# Arduino.net
KiCad netlist of a schematic drawn in EasyEDA
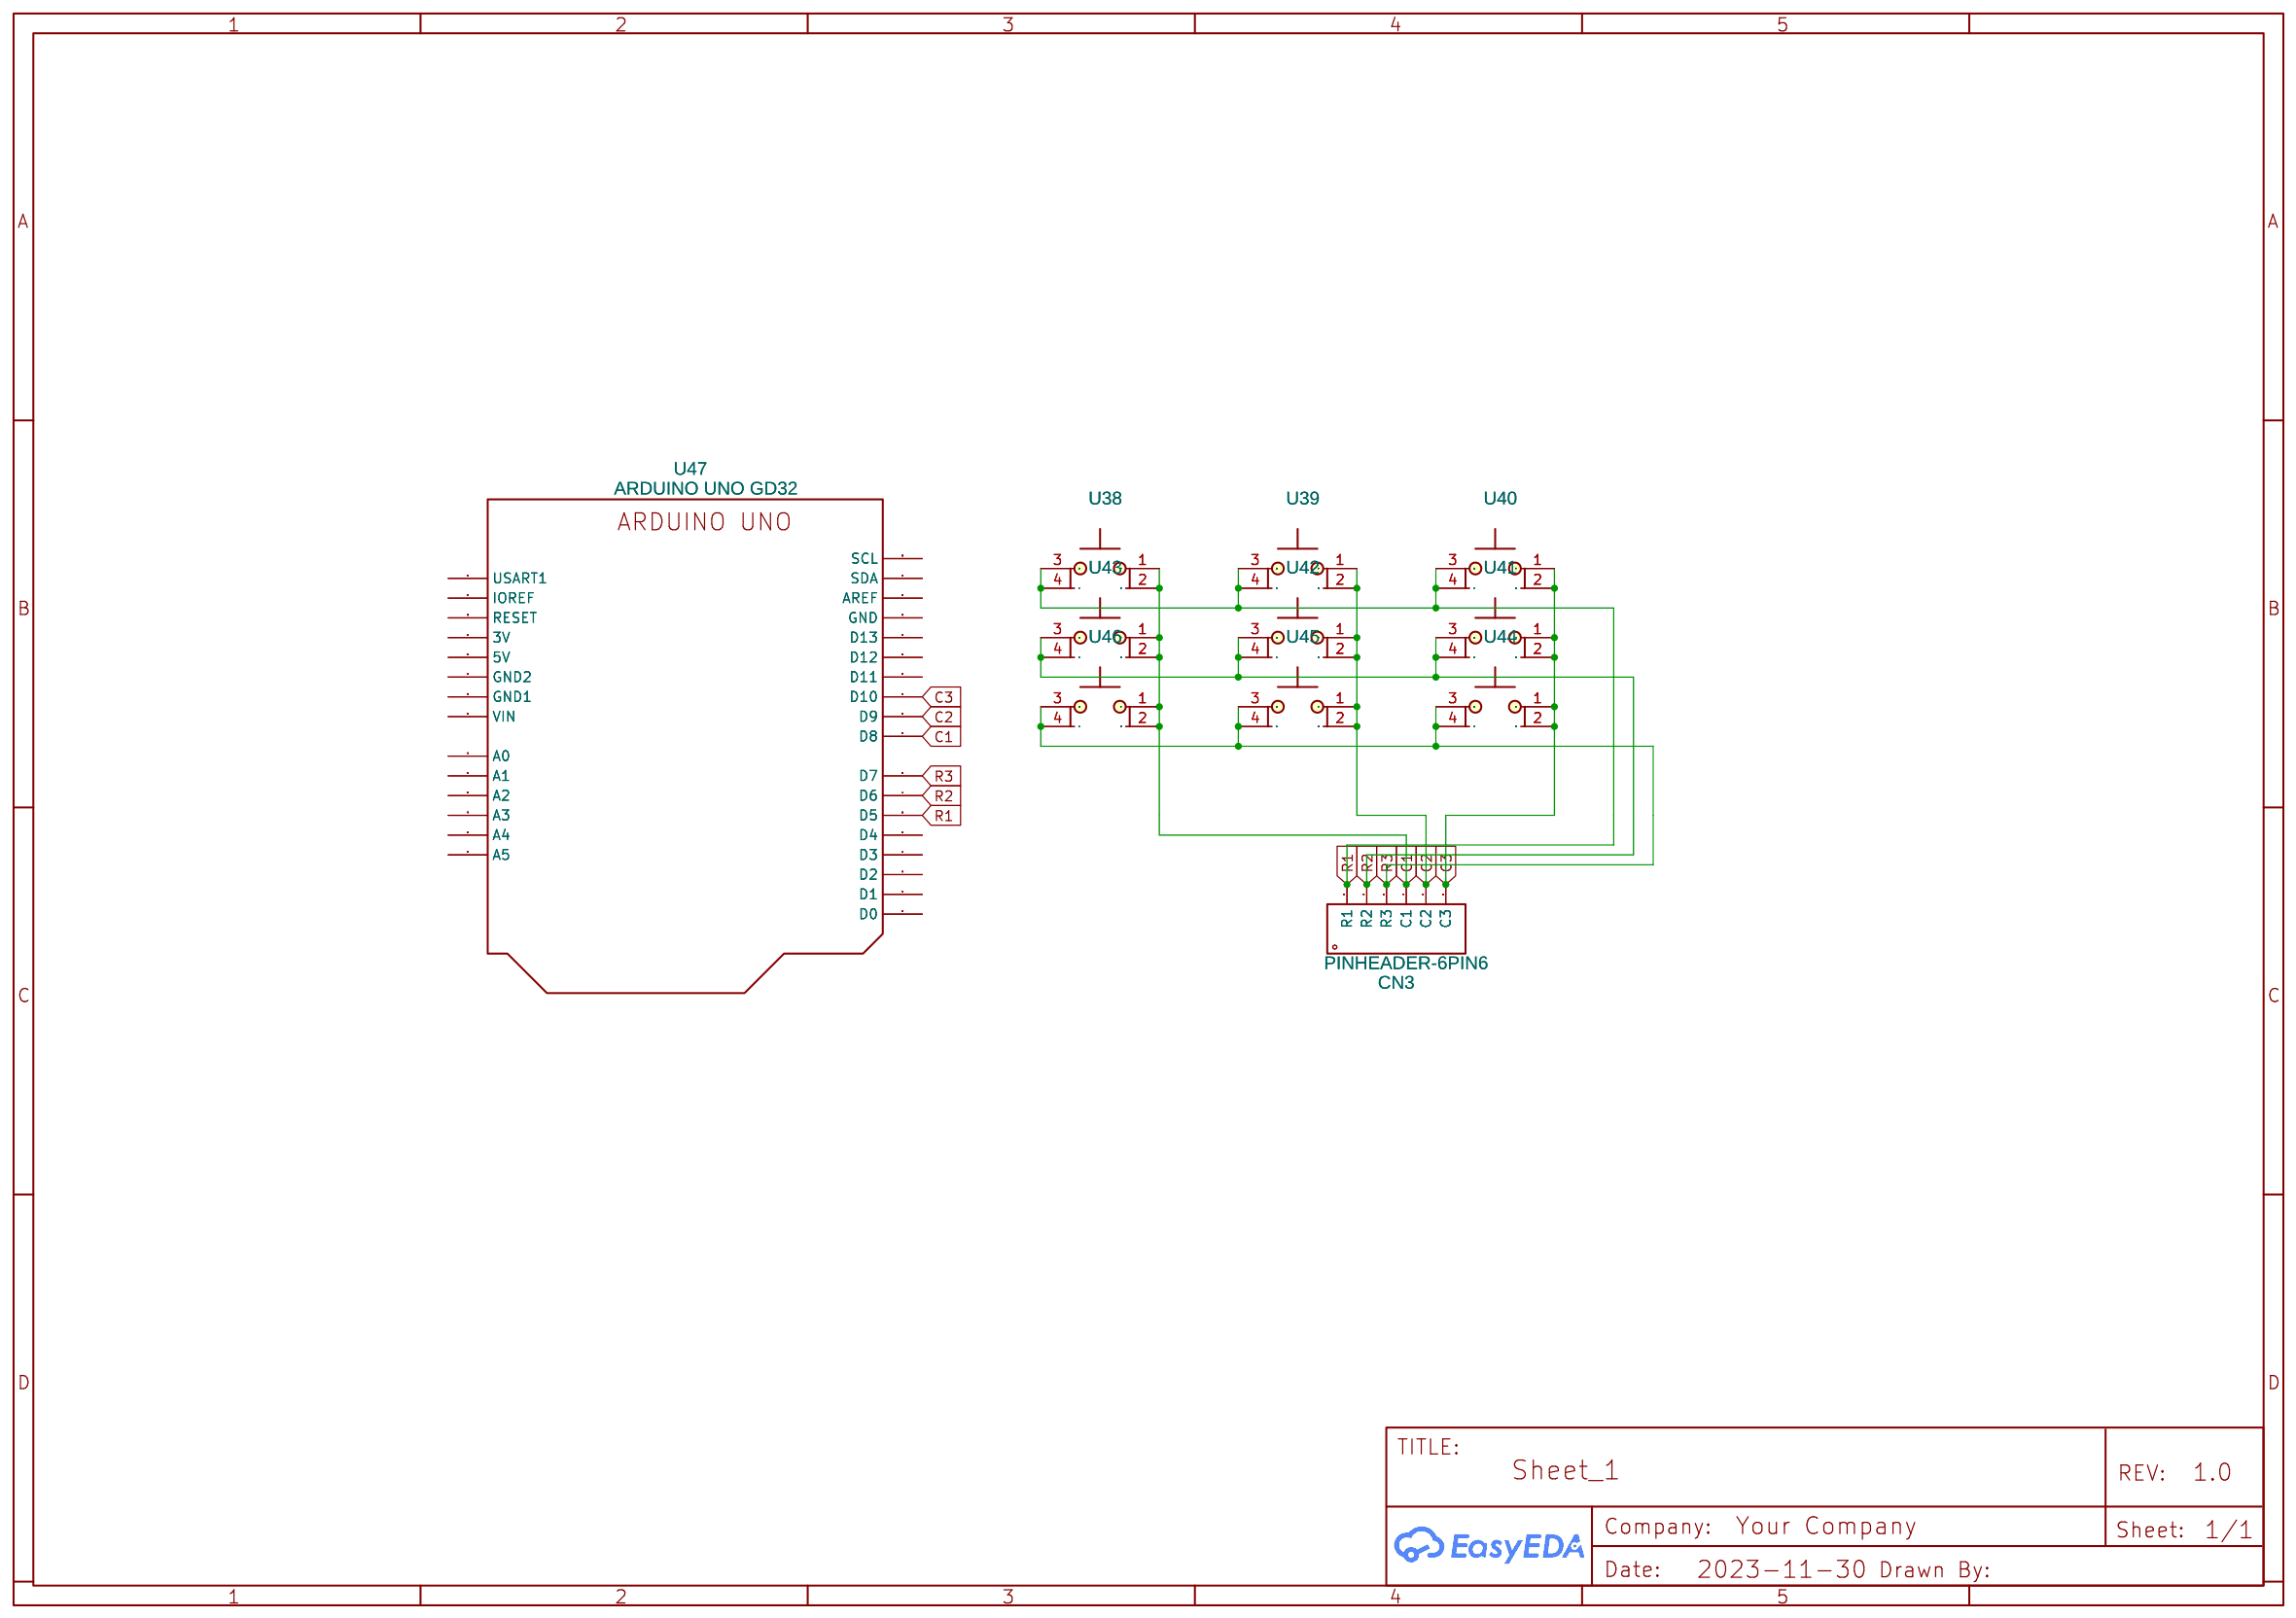
[diagram p0: Arduino_Keypad 3X3]
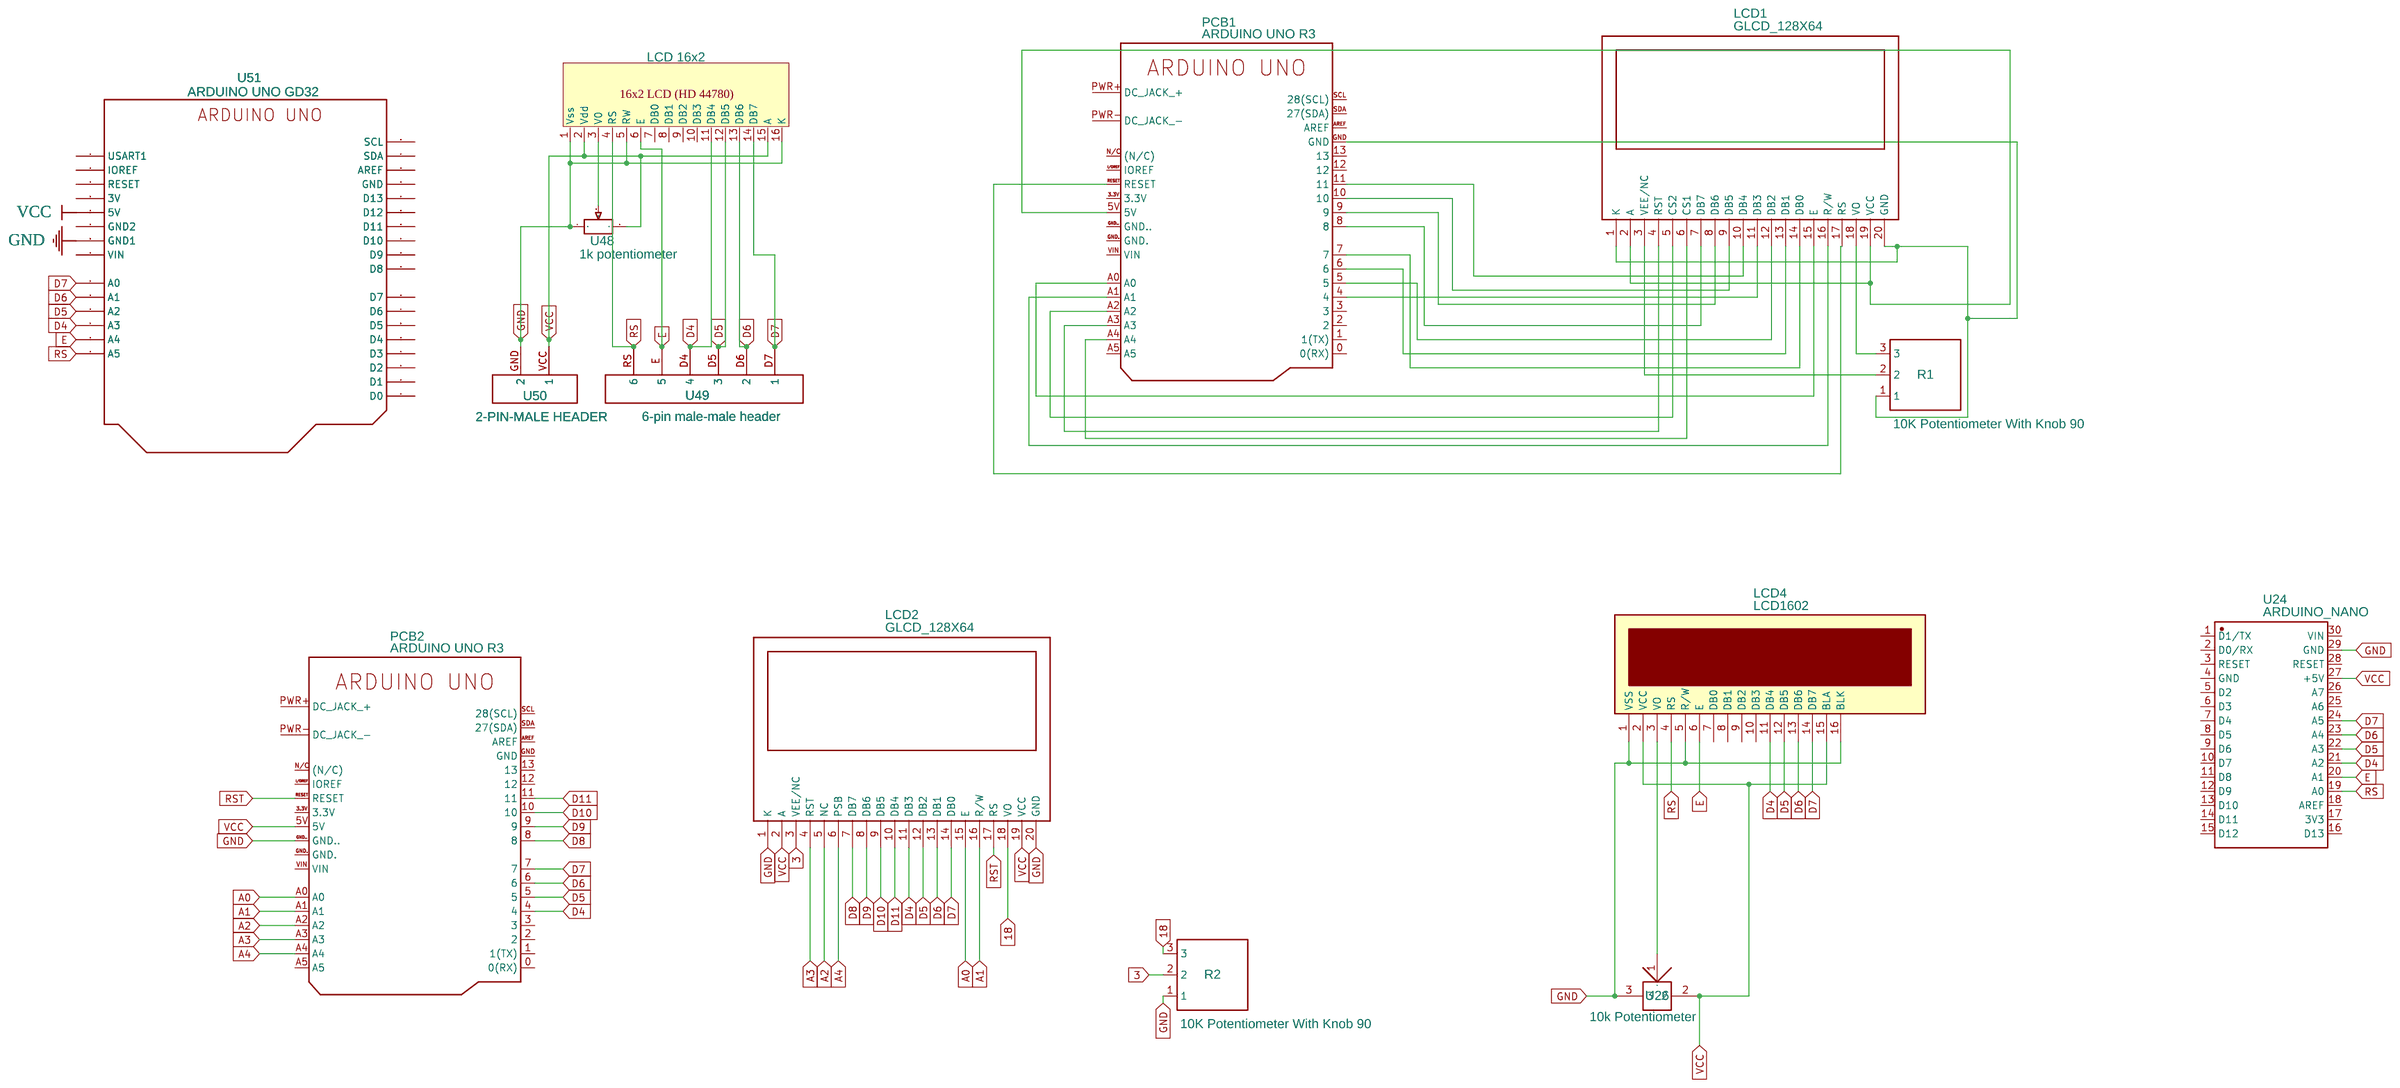
[diagram p1: Arduino_LCD 16x2]
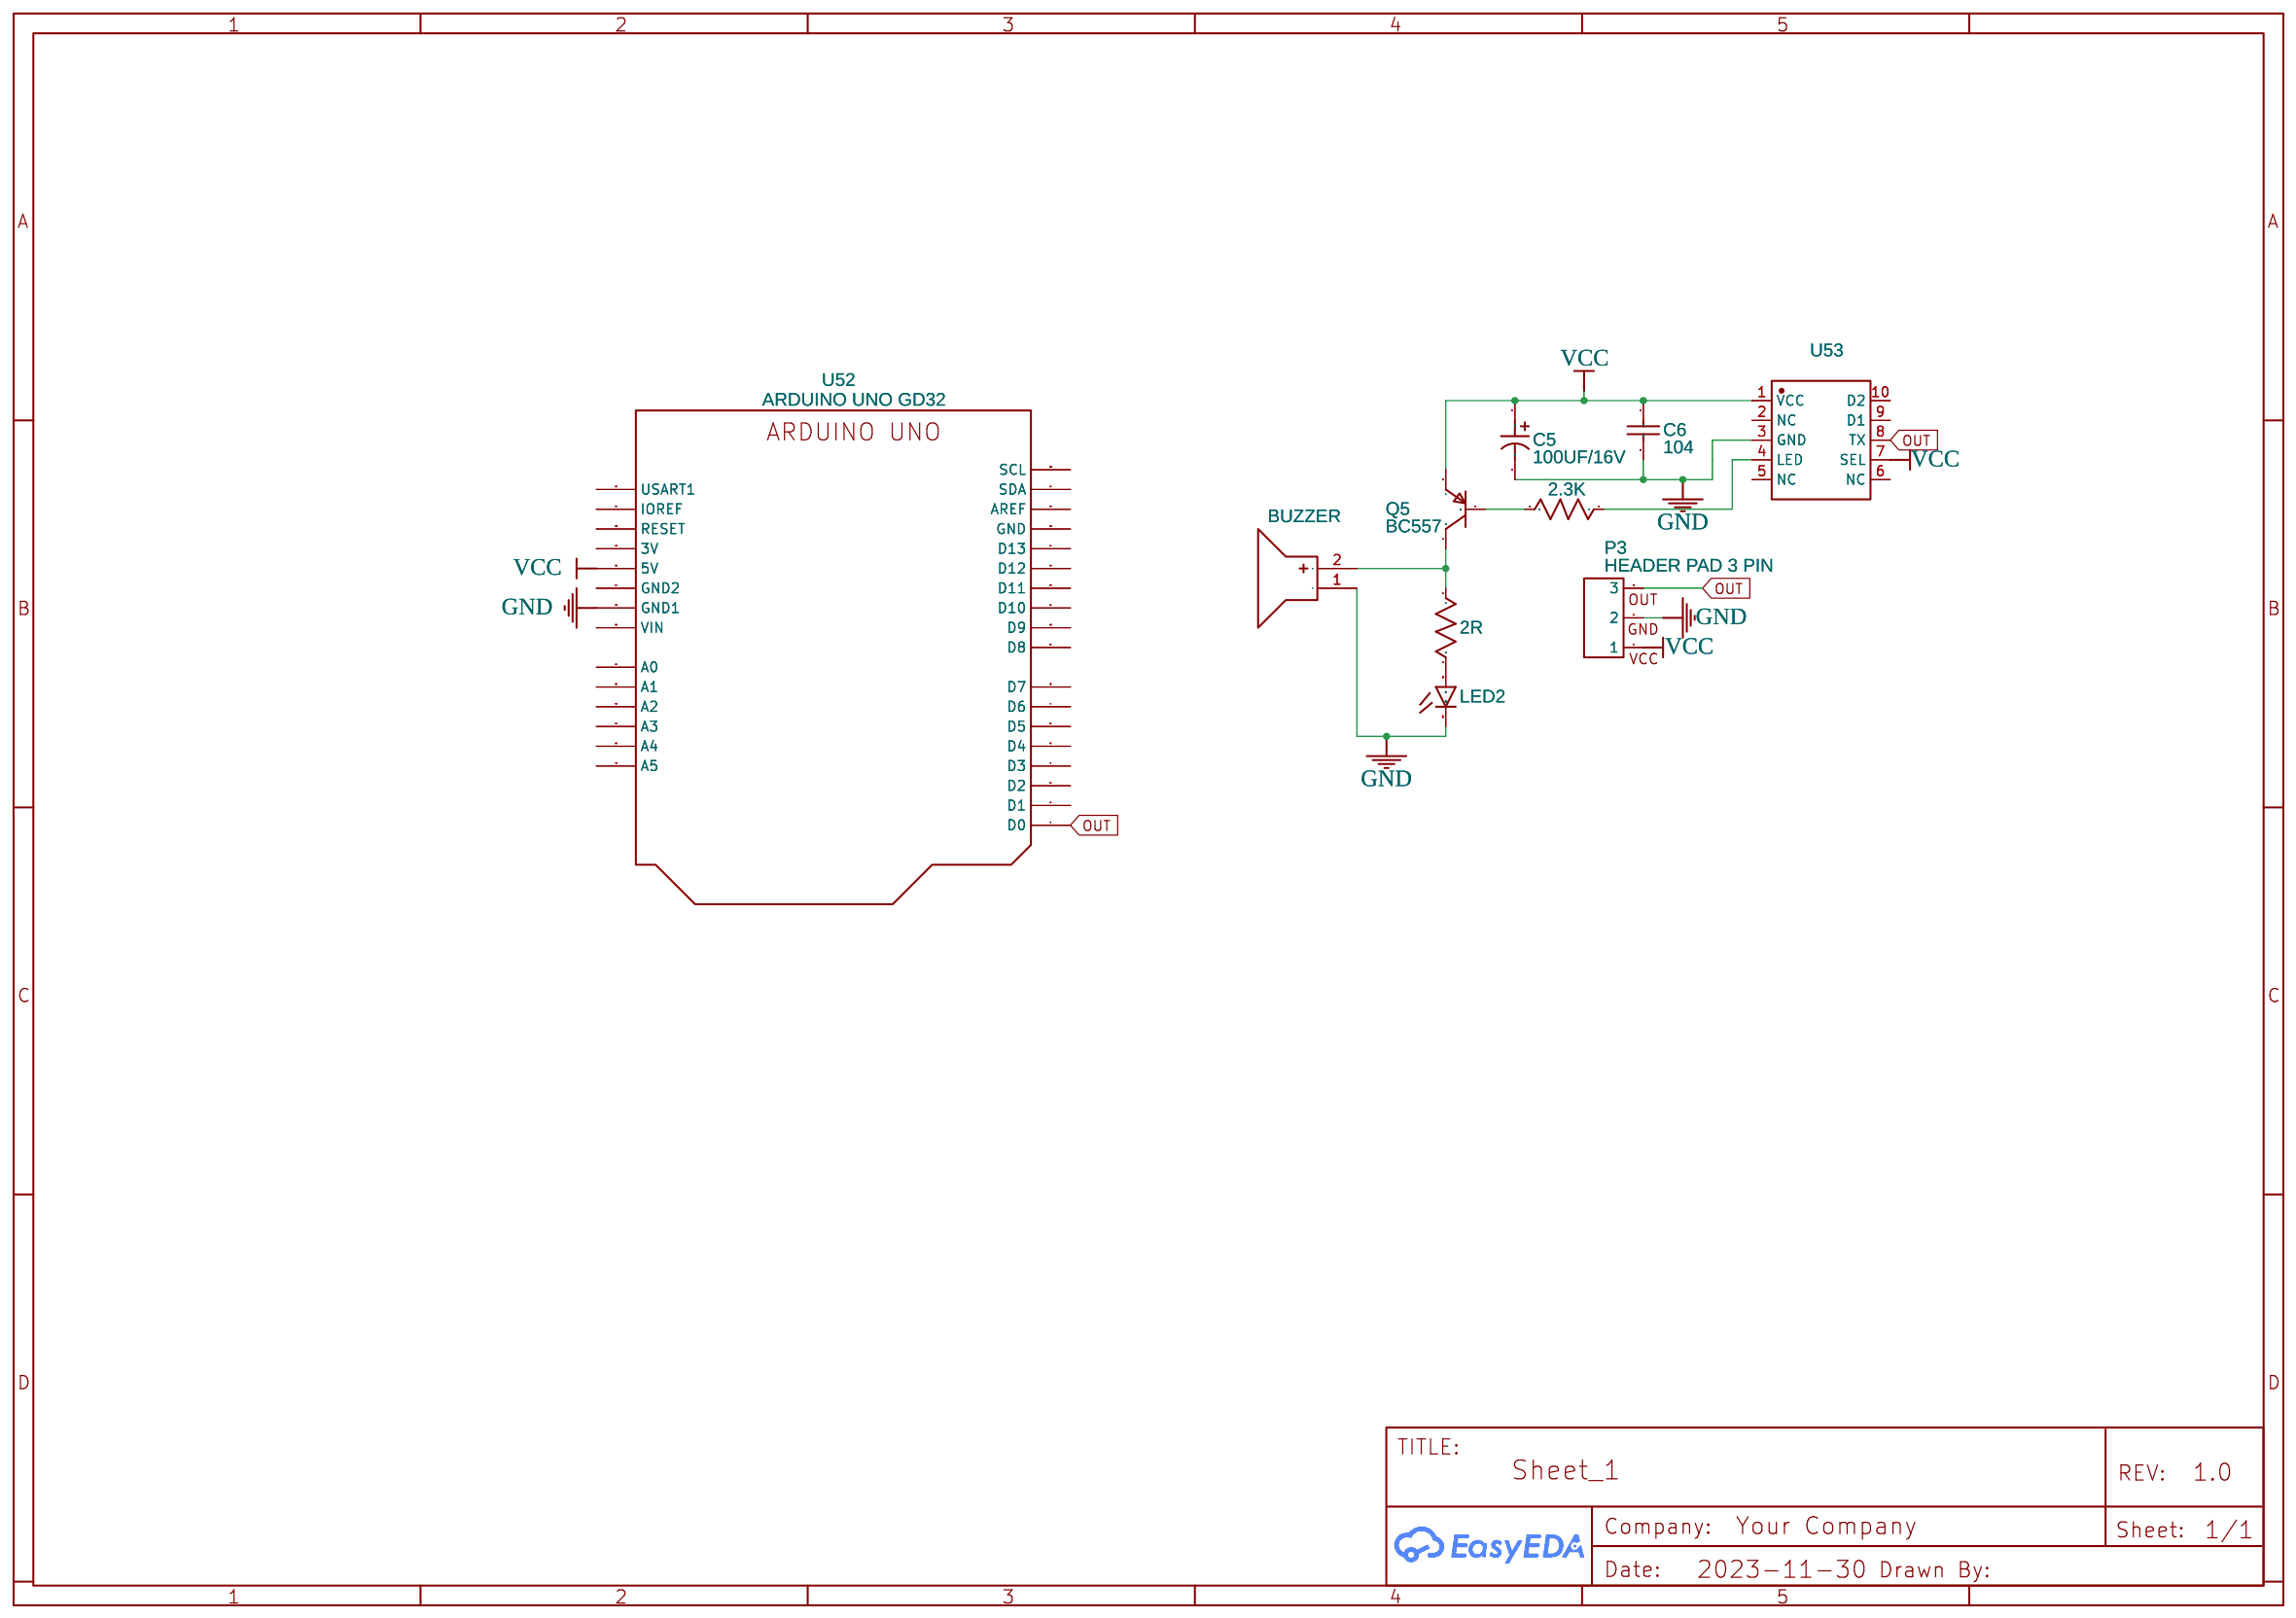
[diagram p2: Arduino_EM-18 Module]
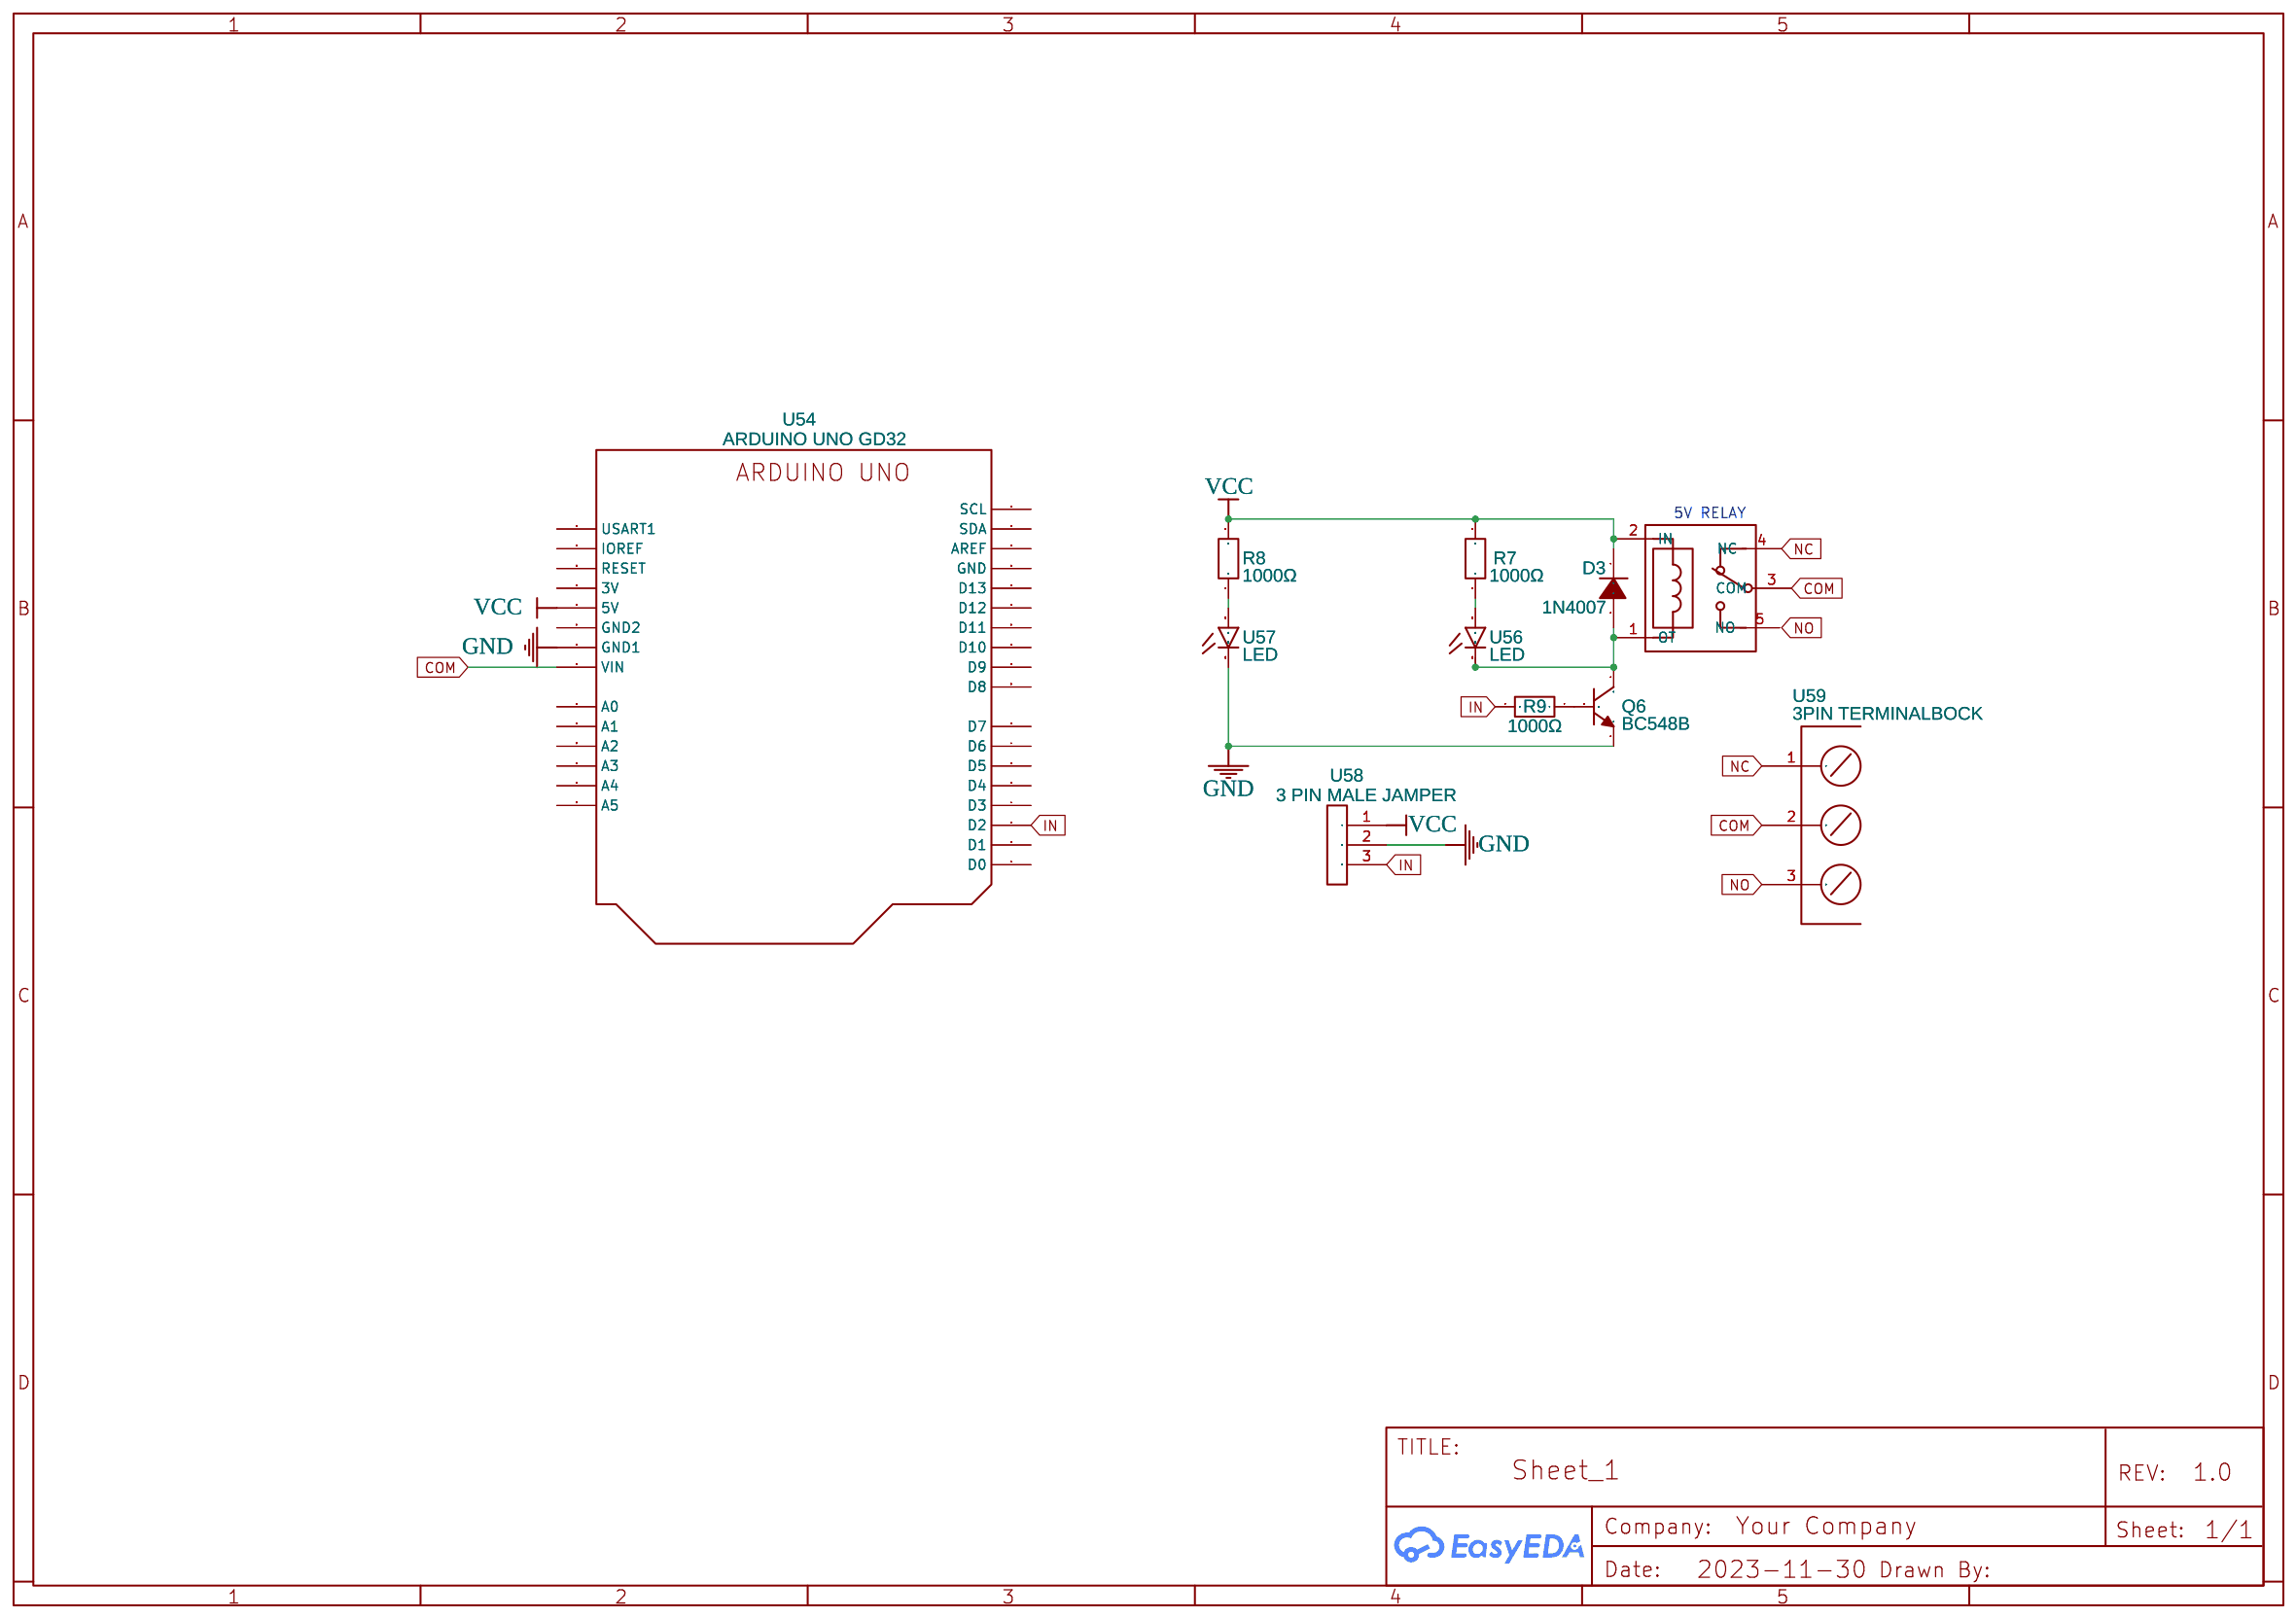
[diagram p3: Arduino_Relay Module]
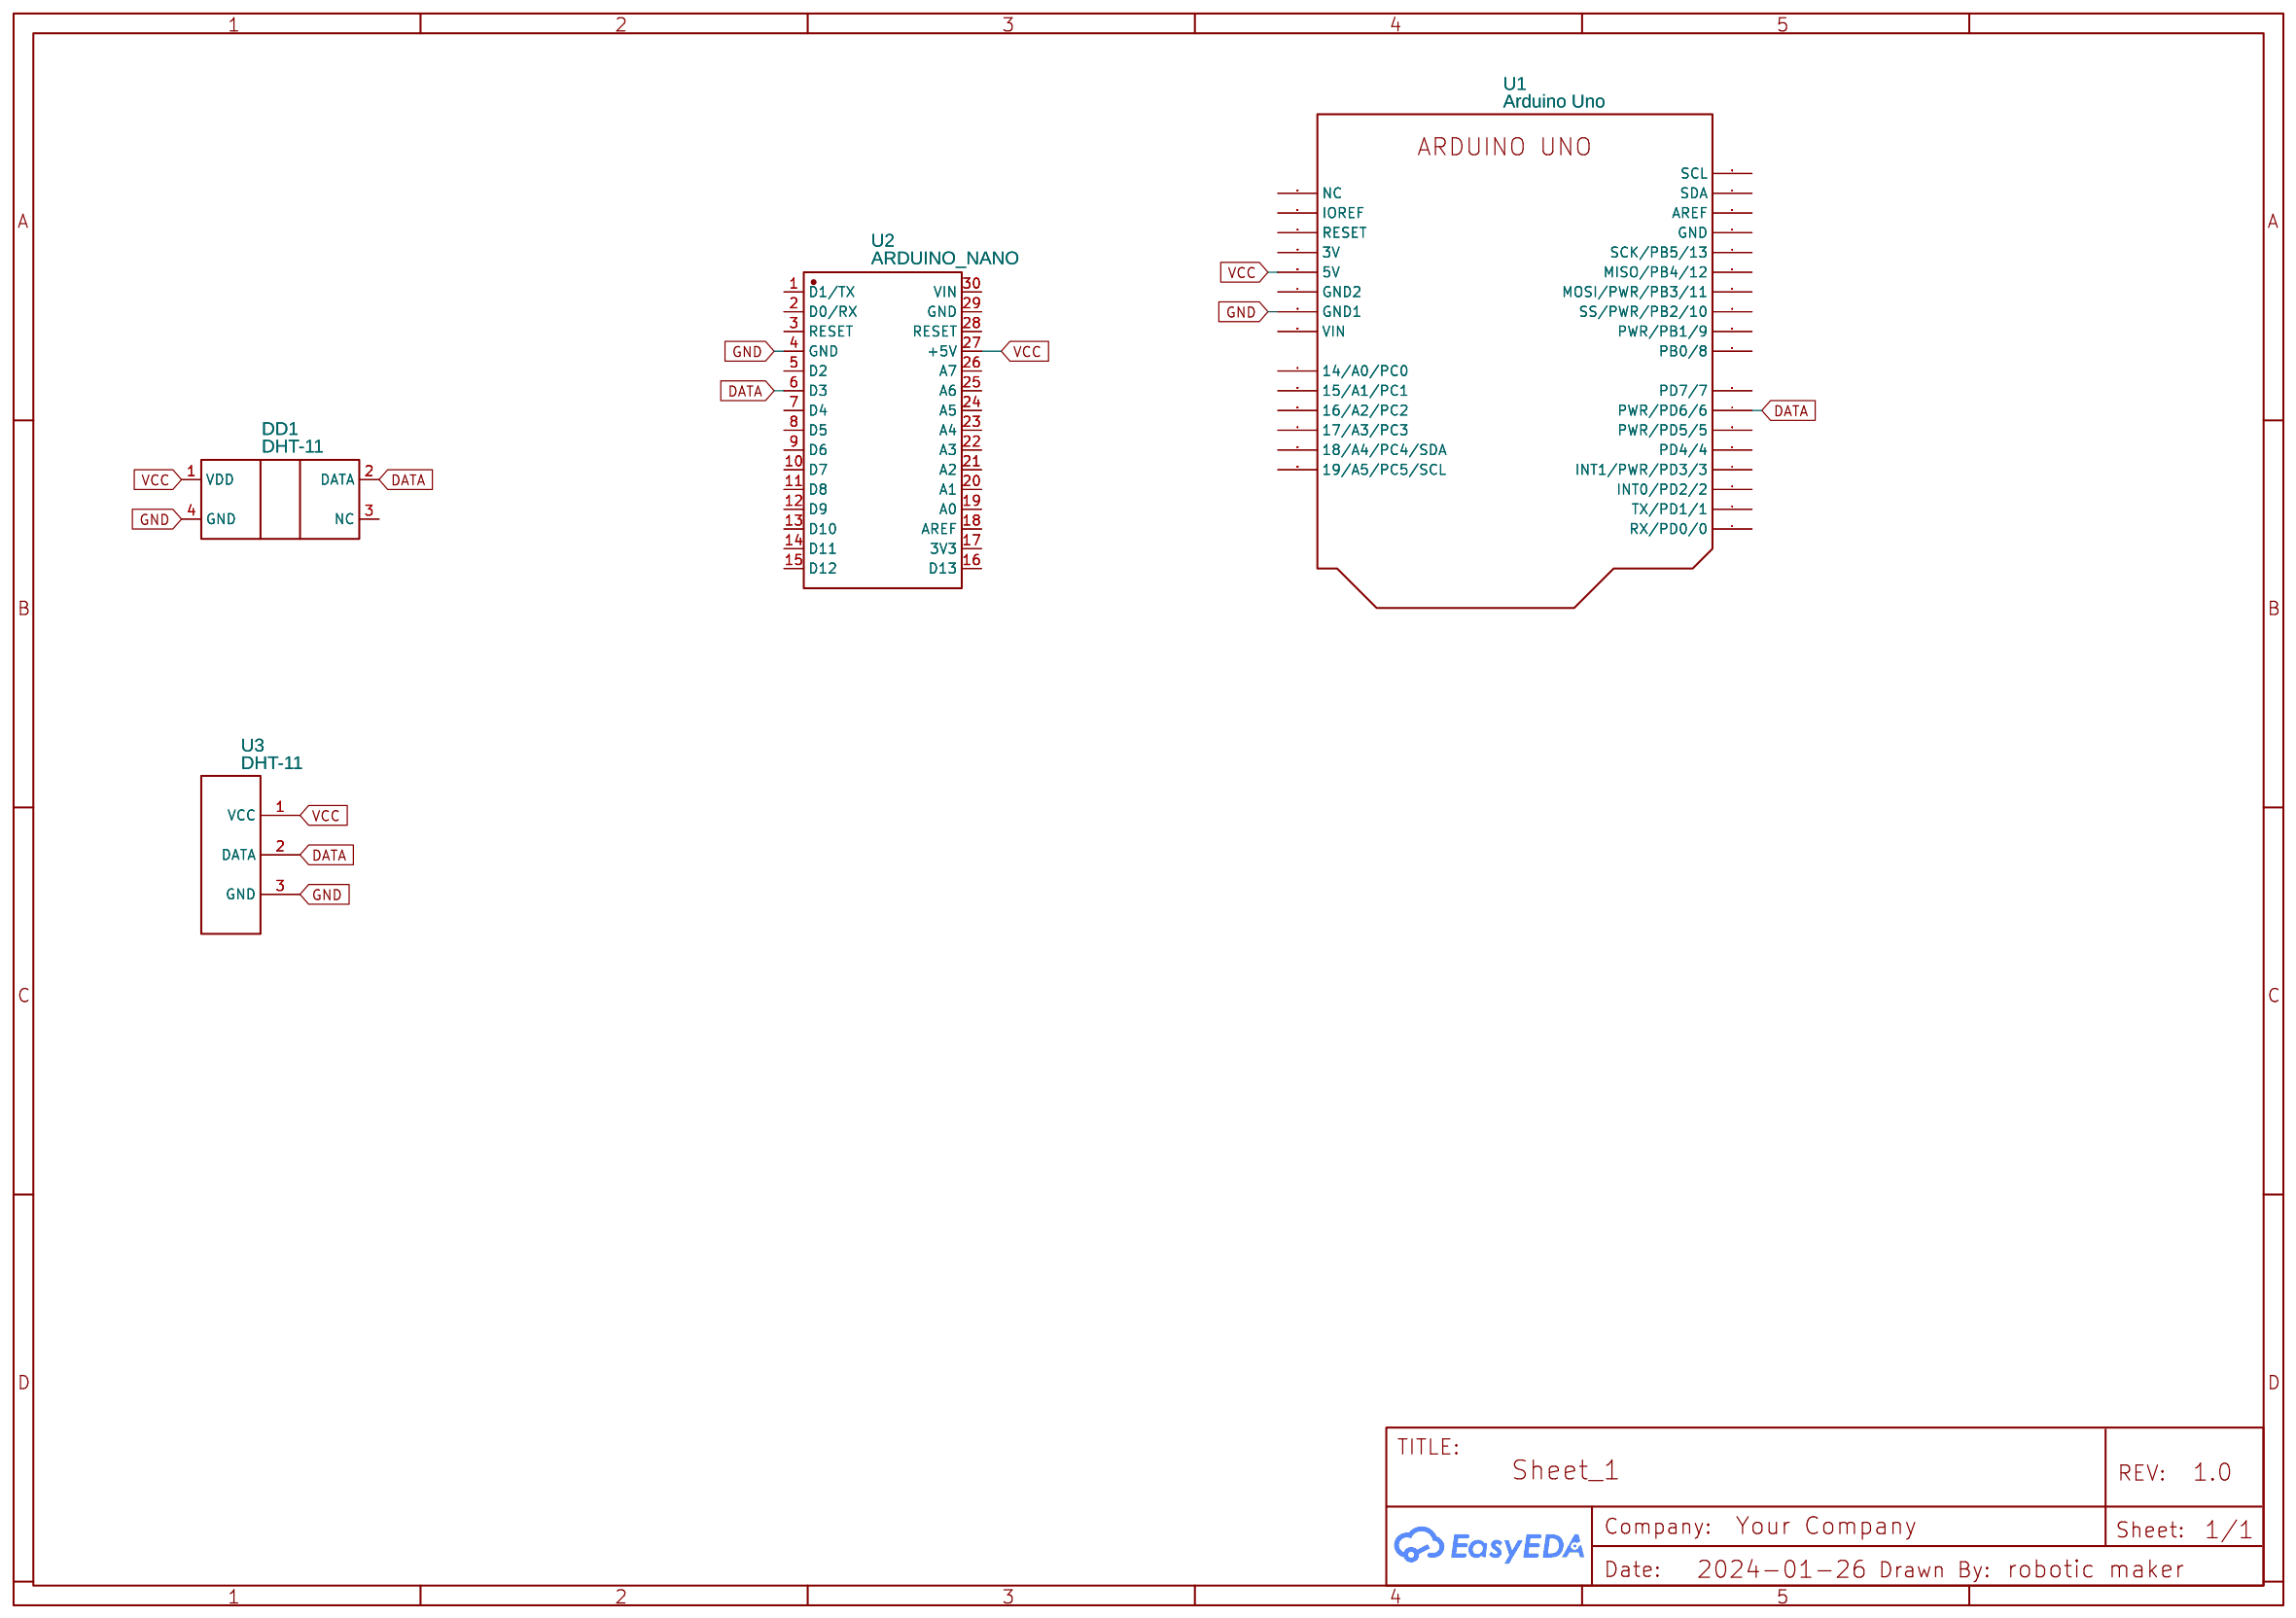
[diagram p4: DHT-11 & DHT-22]
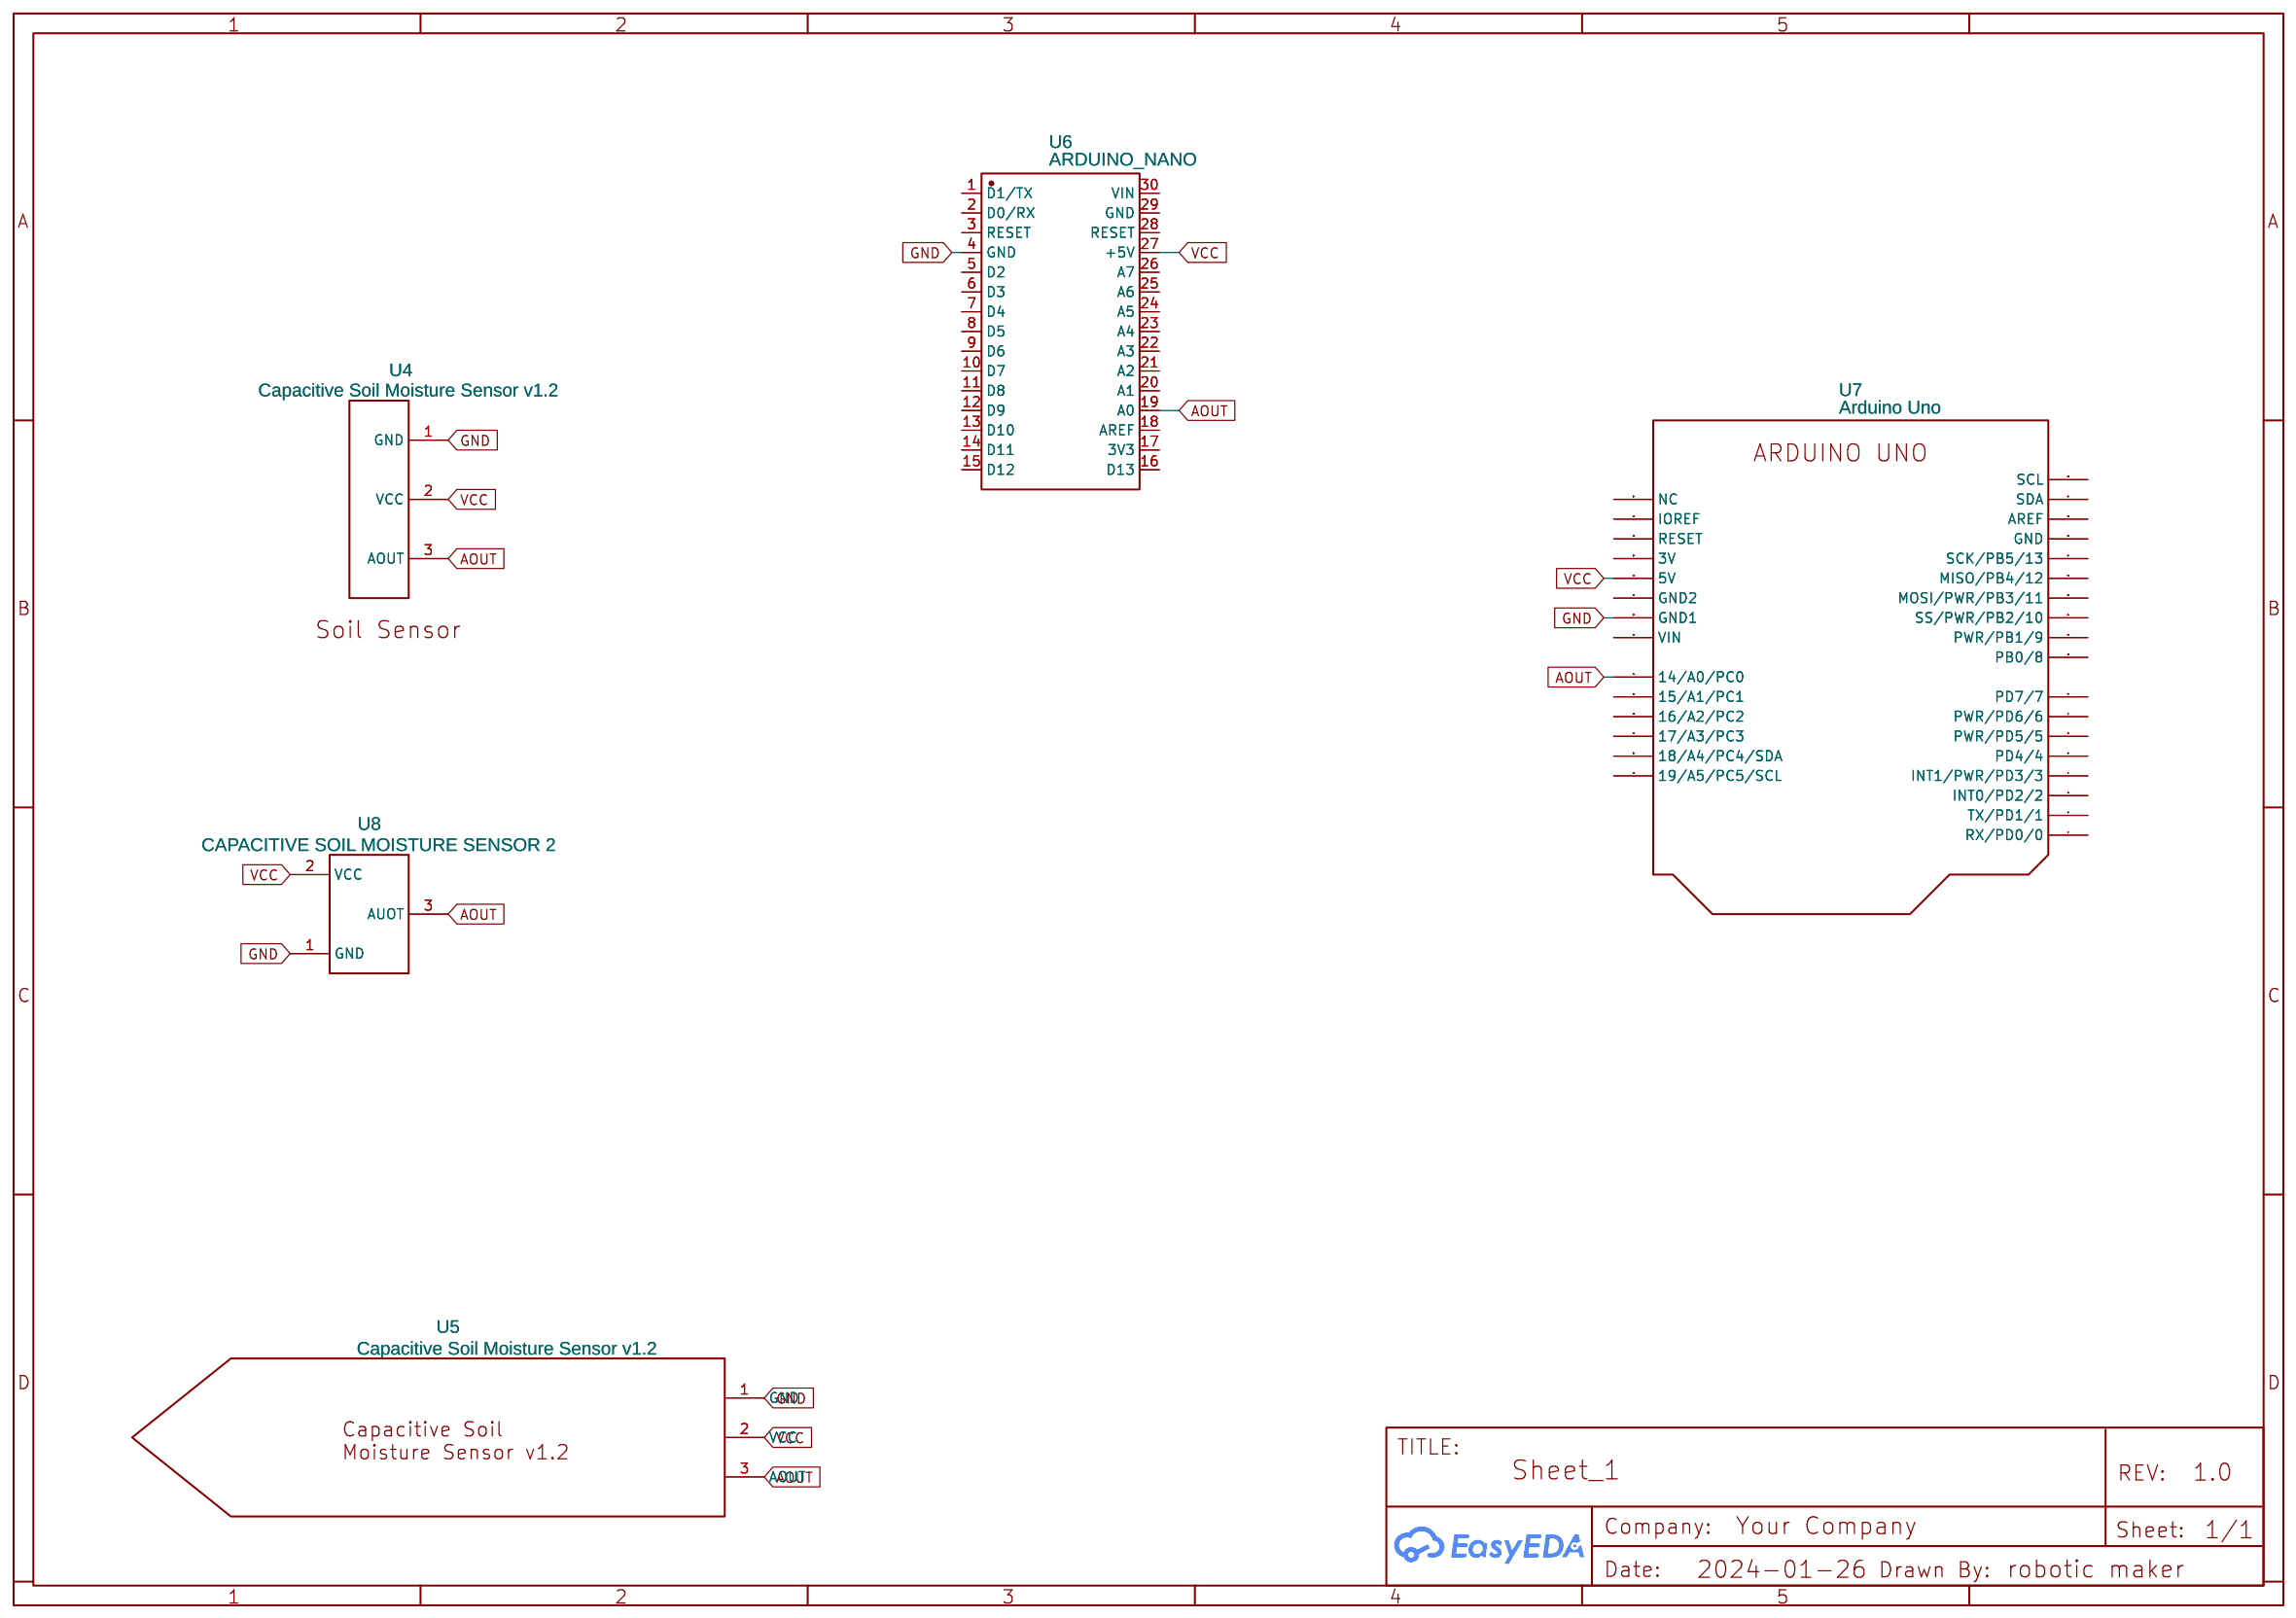
[diagram p5: Capacitive Soil Moisture Sensor]
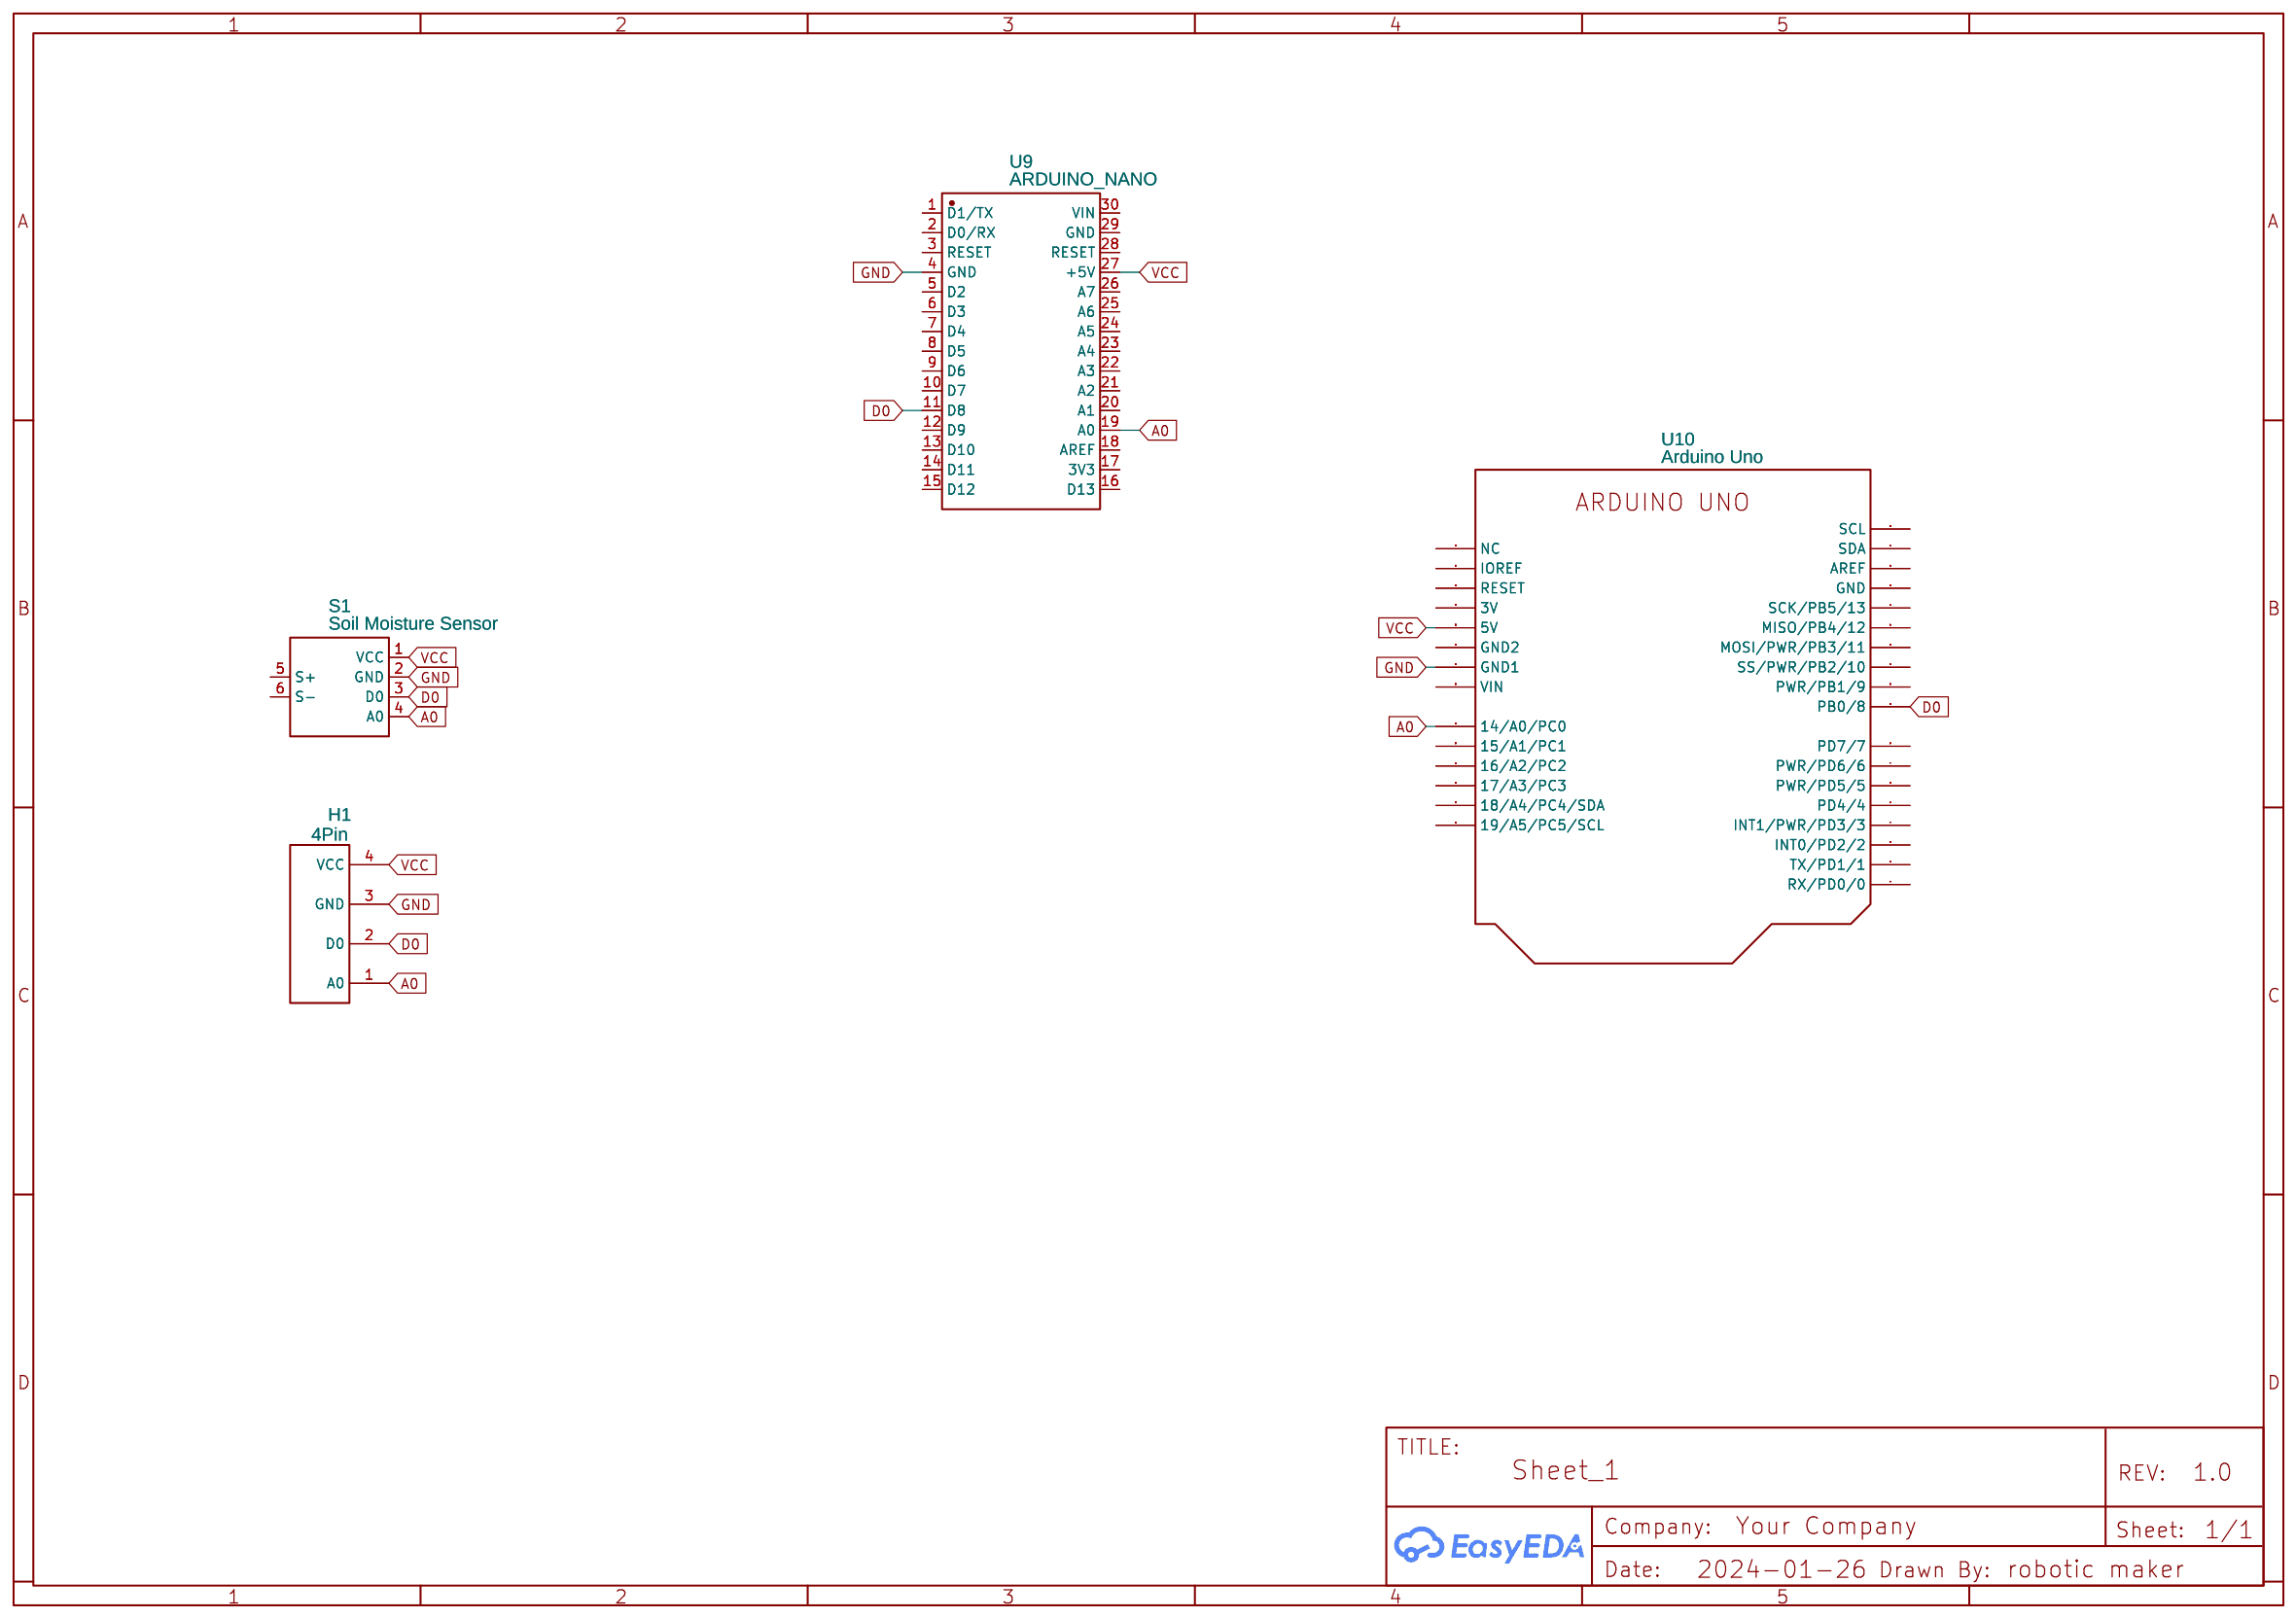
[diagram p6: Soil Moisture Sensor]
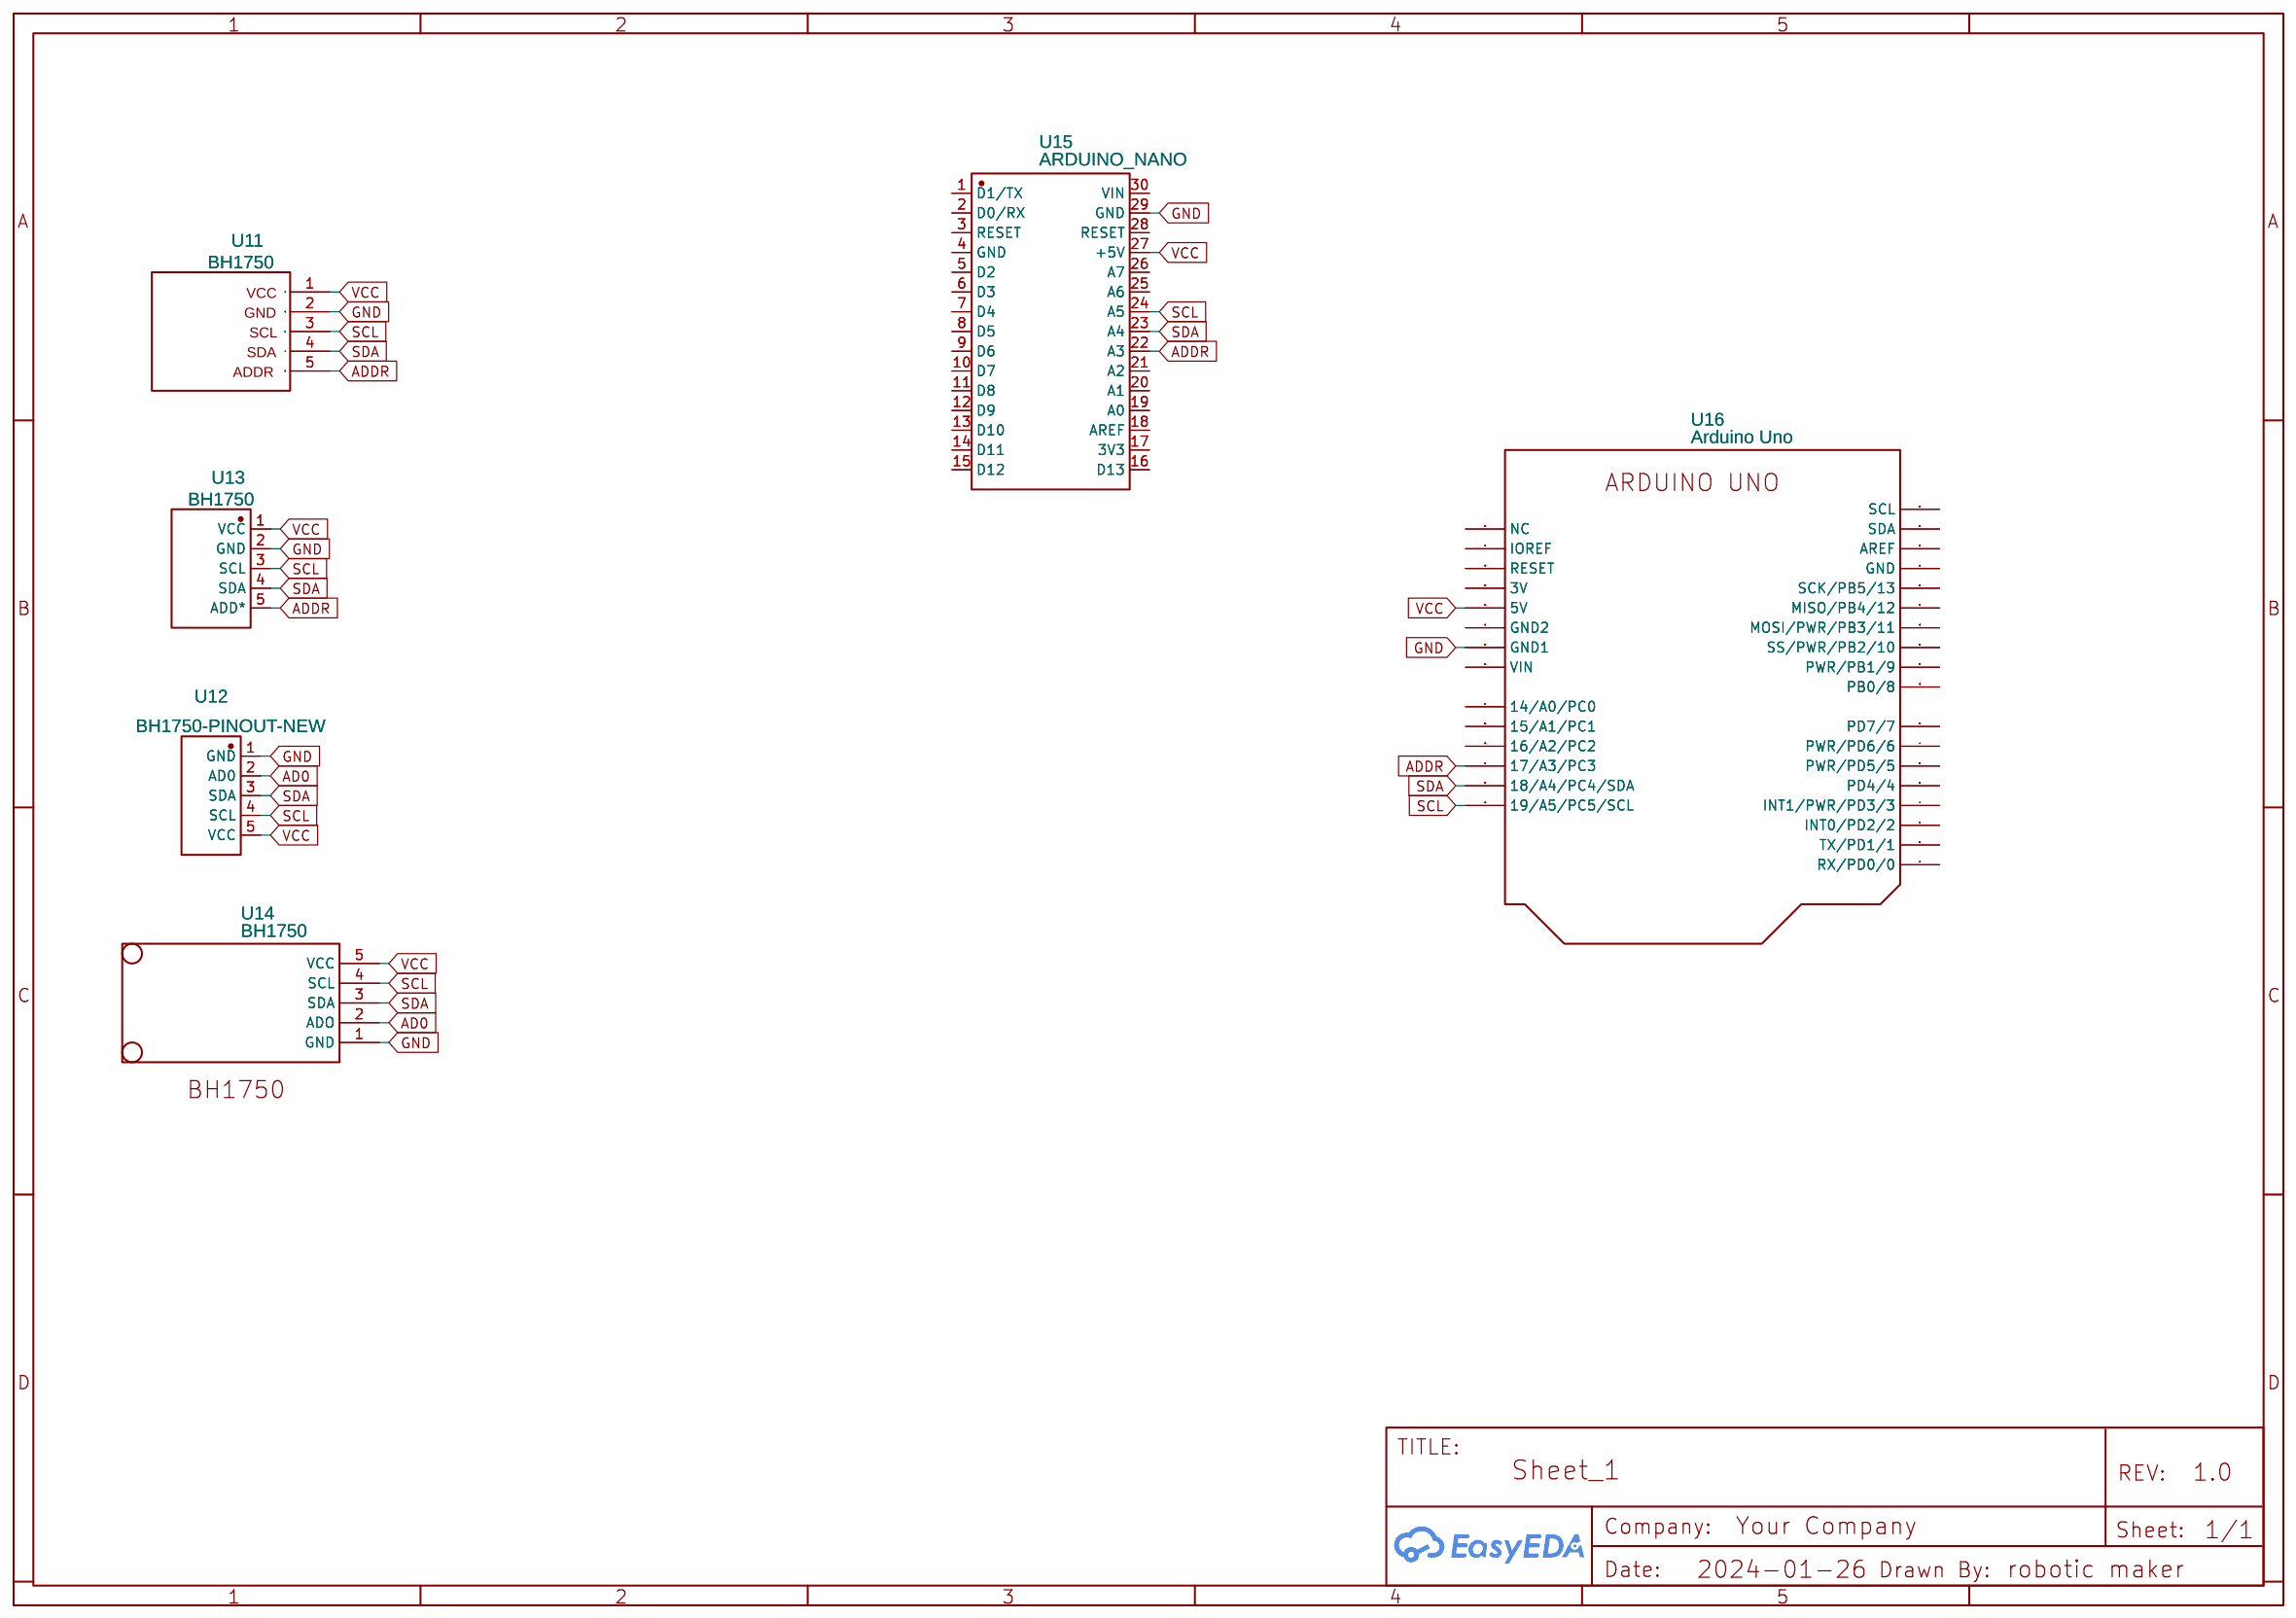
[diagram p7: BH1750]
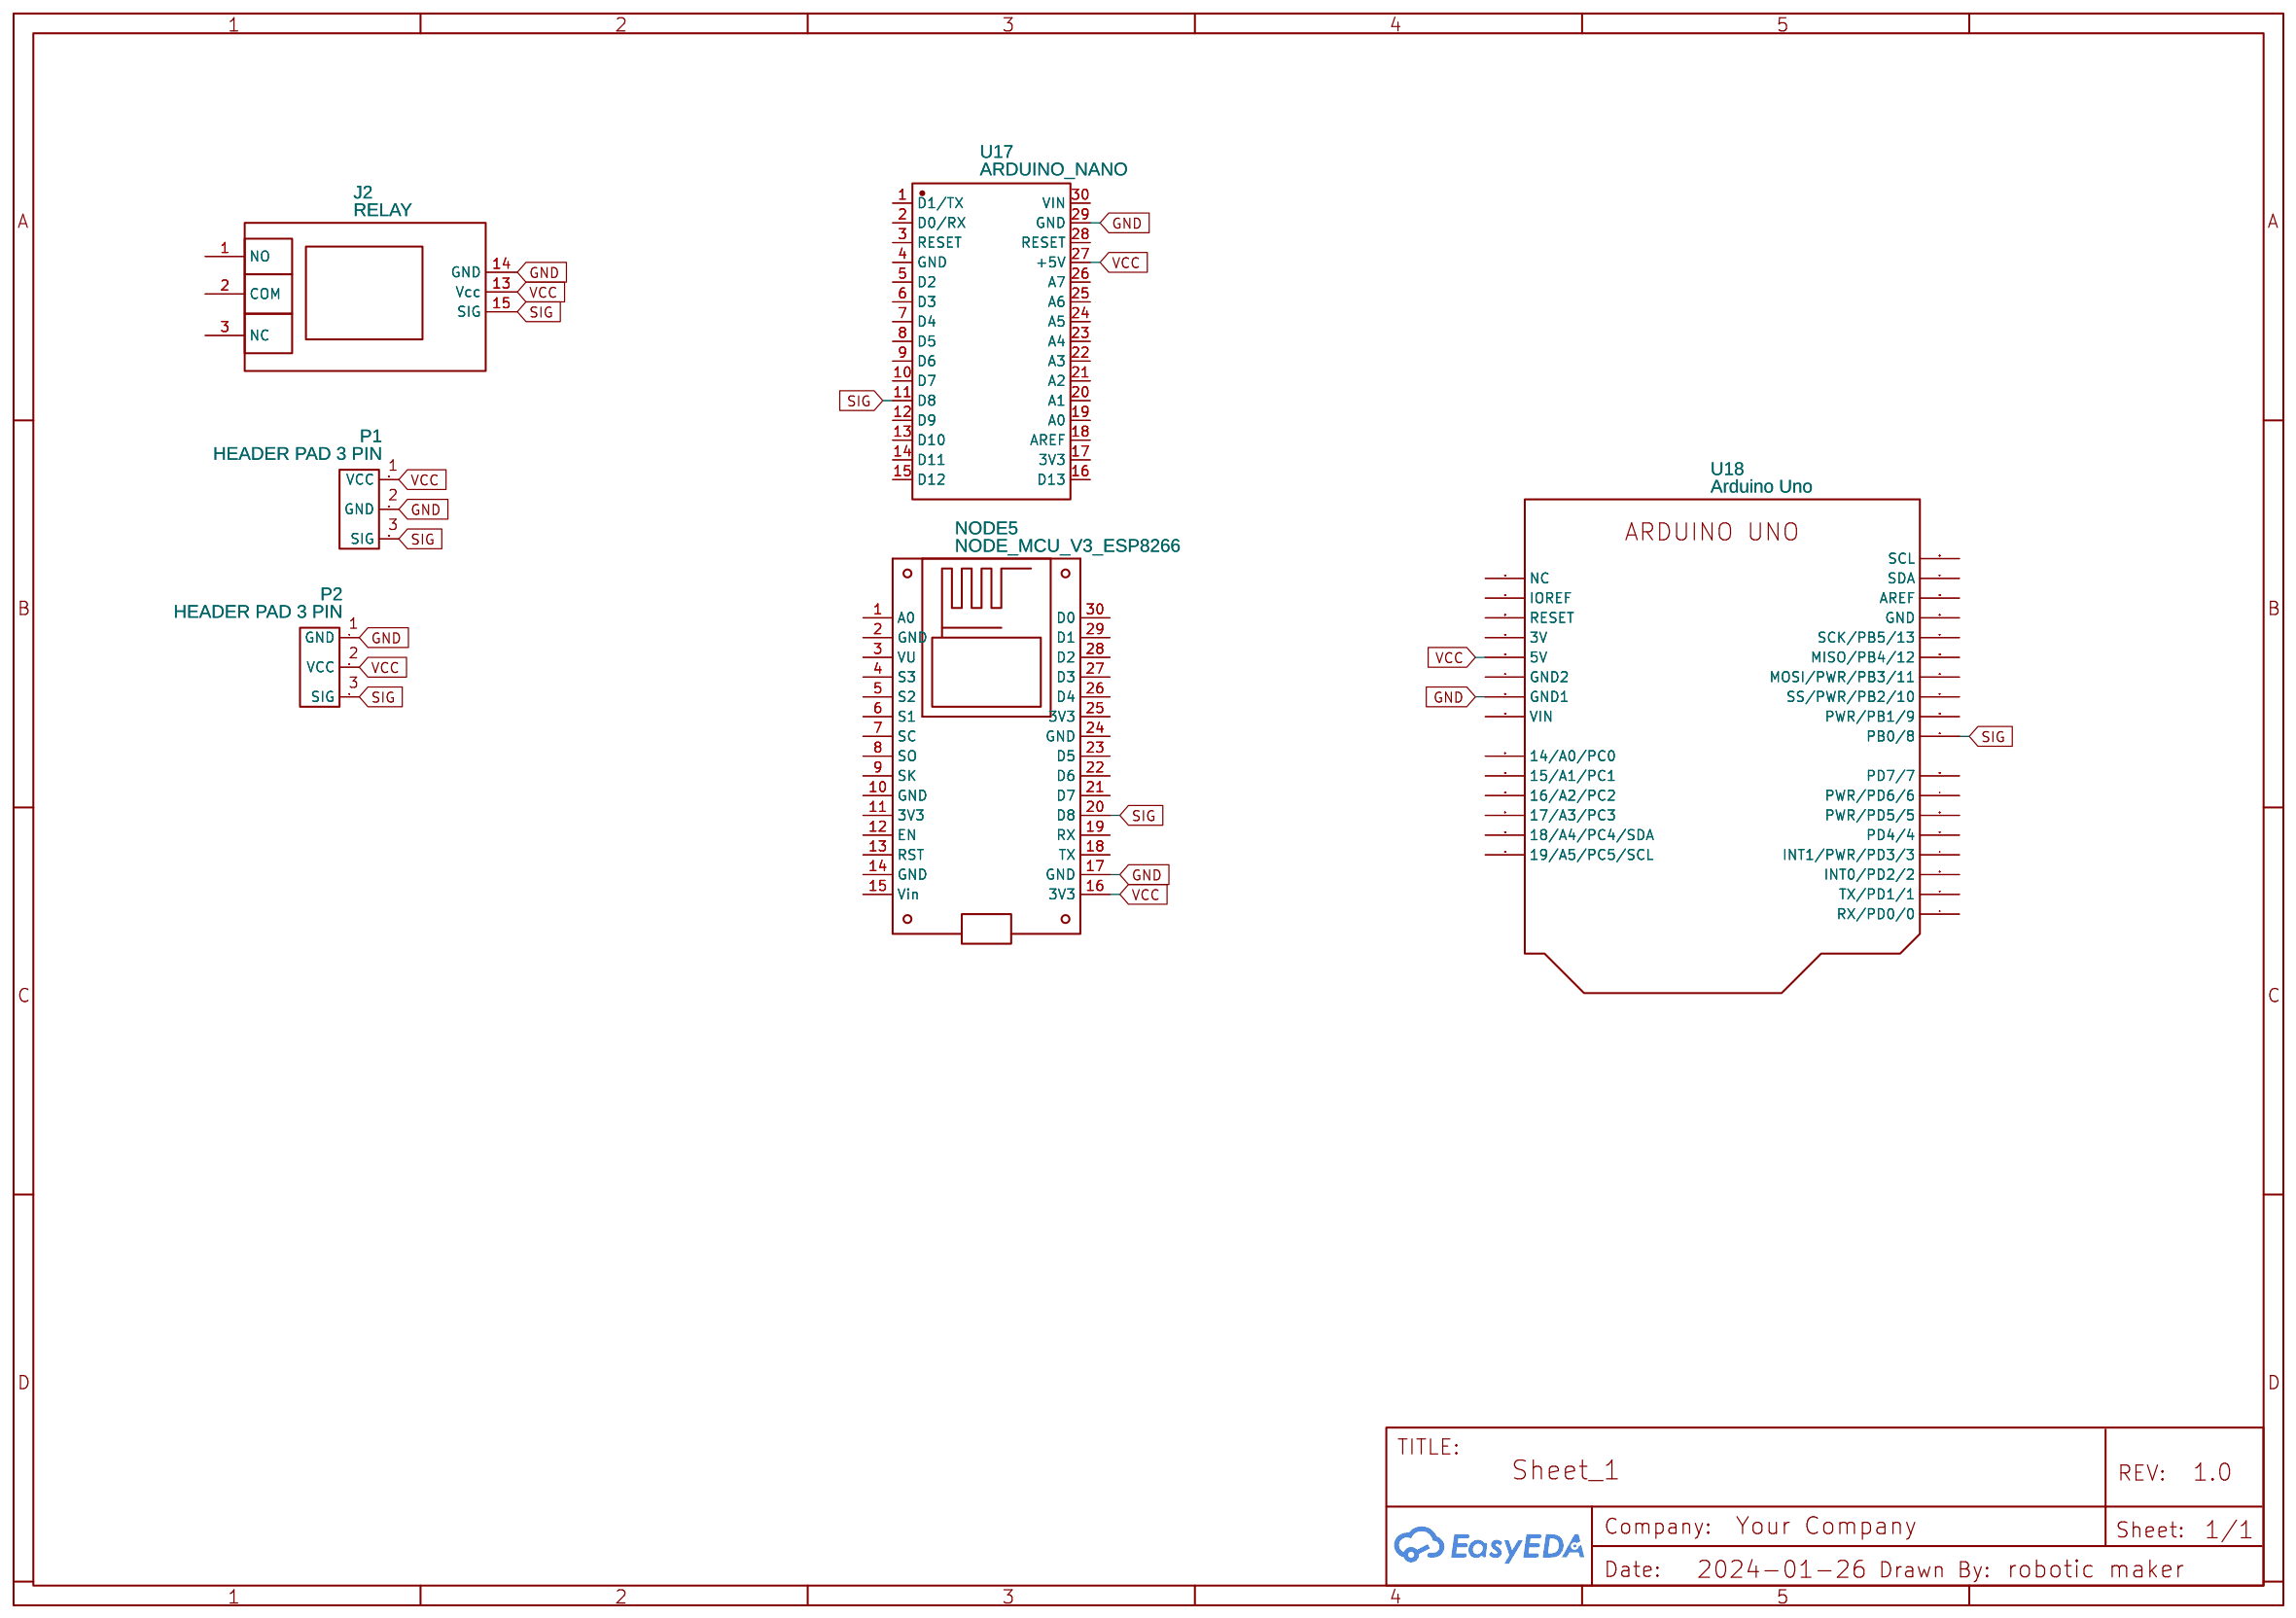
[diagram p8: Relay copy]
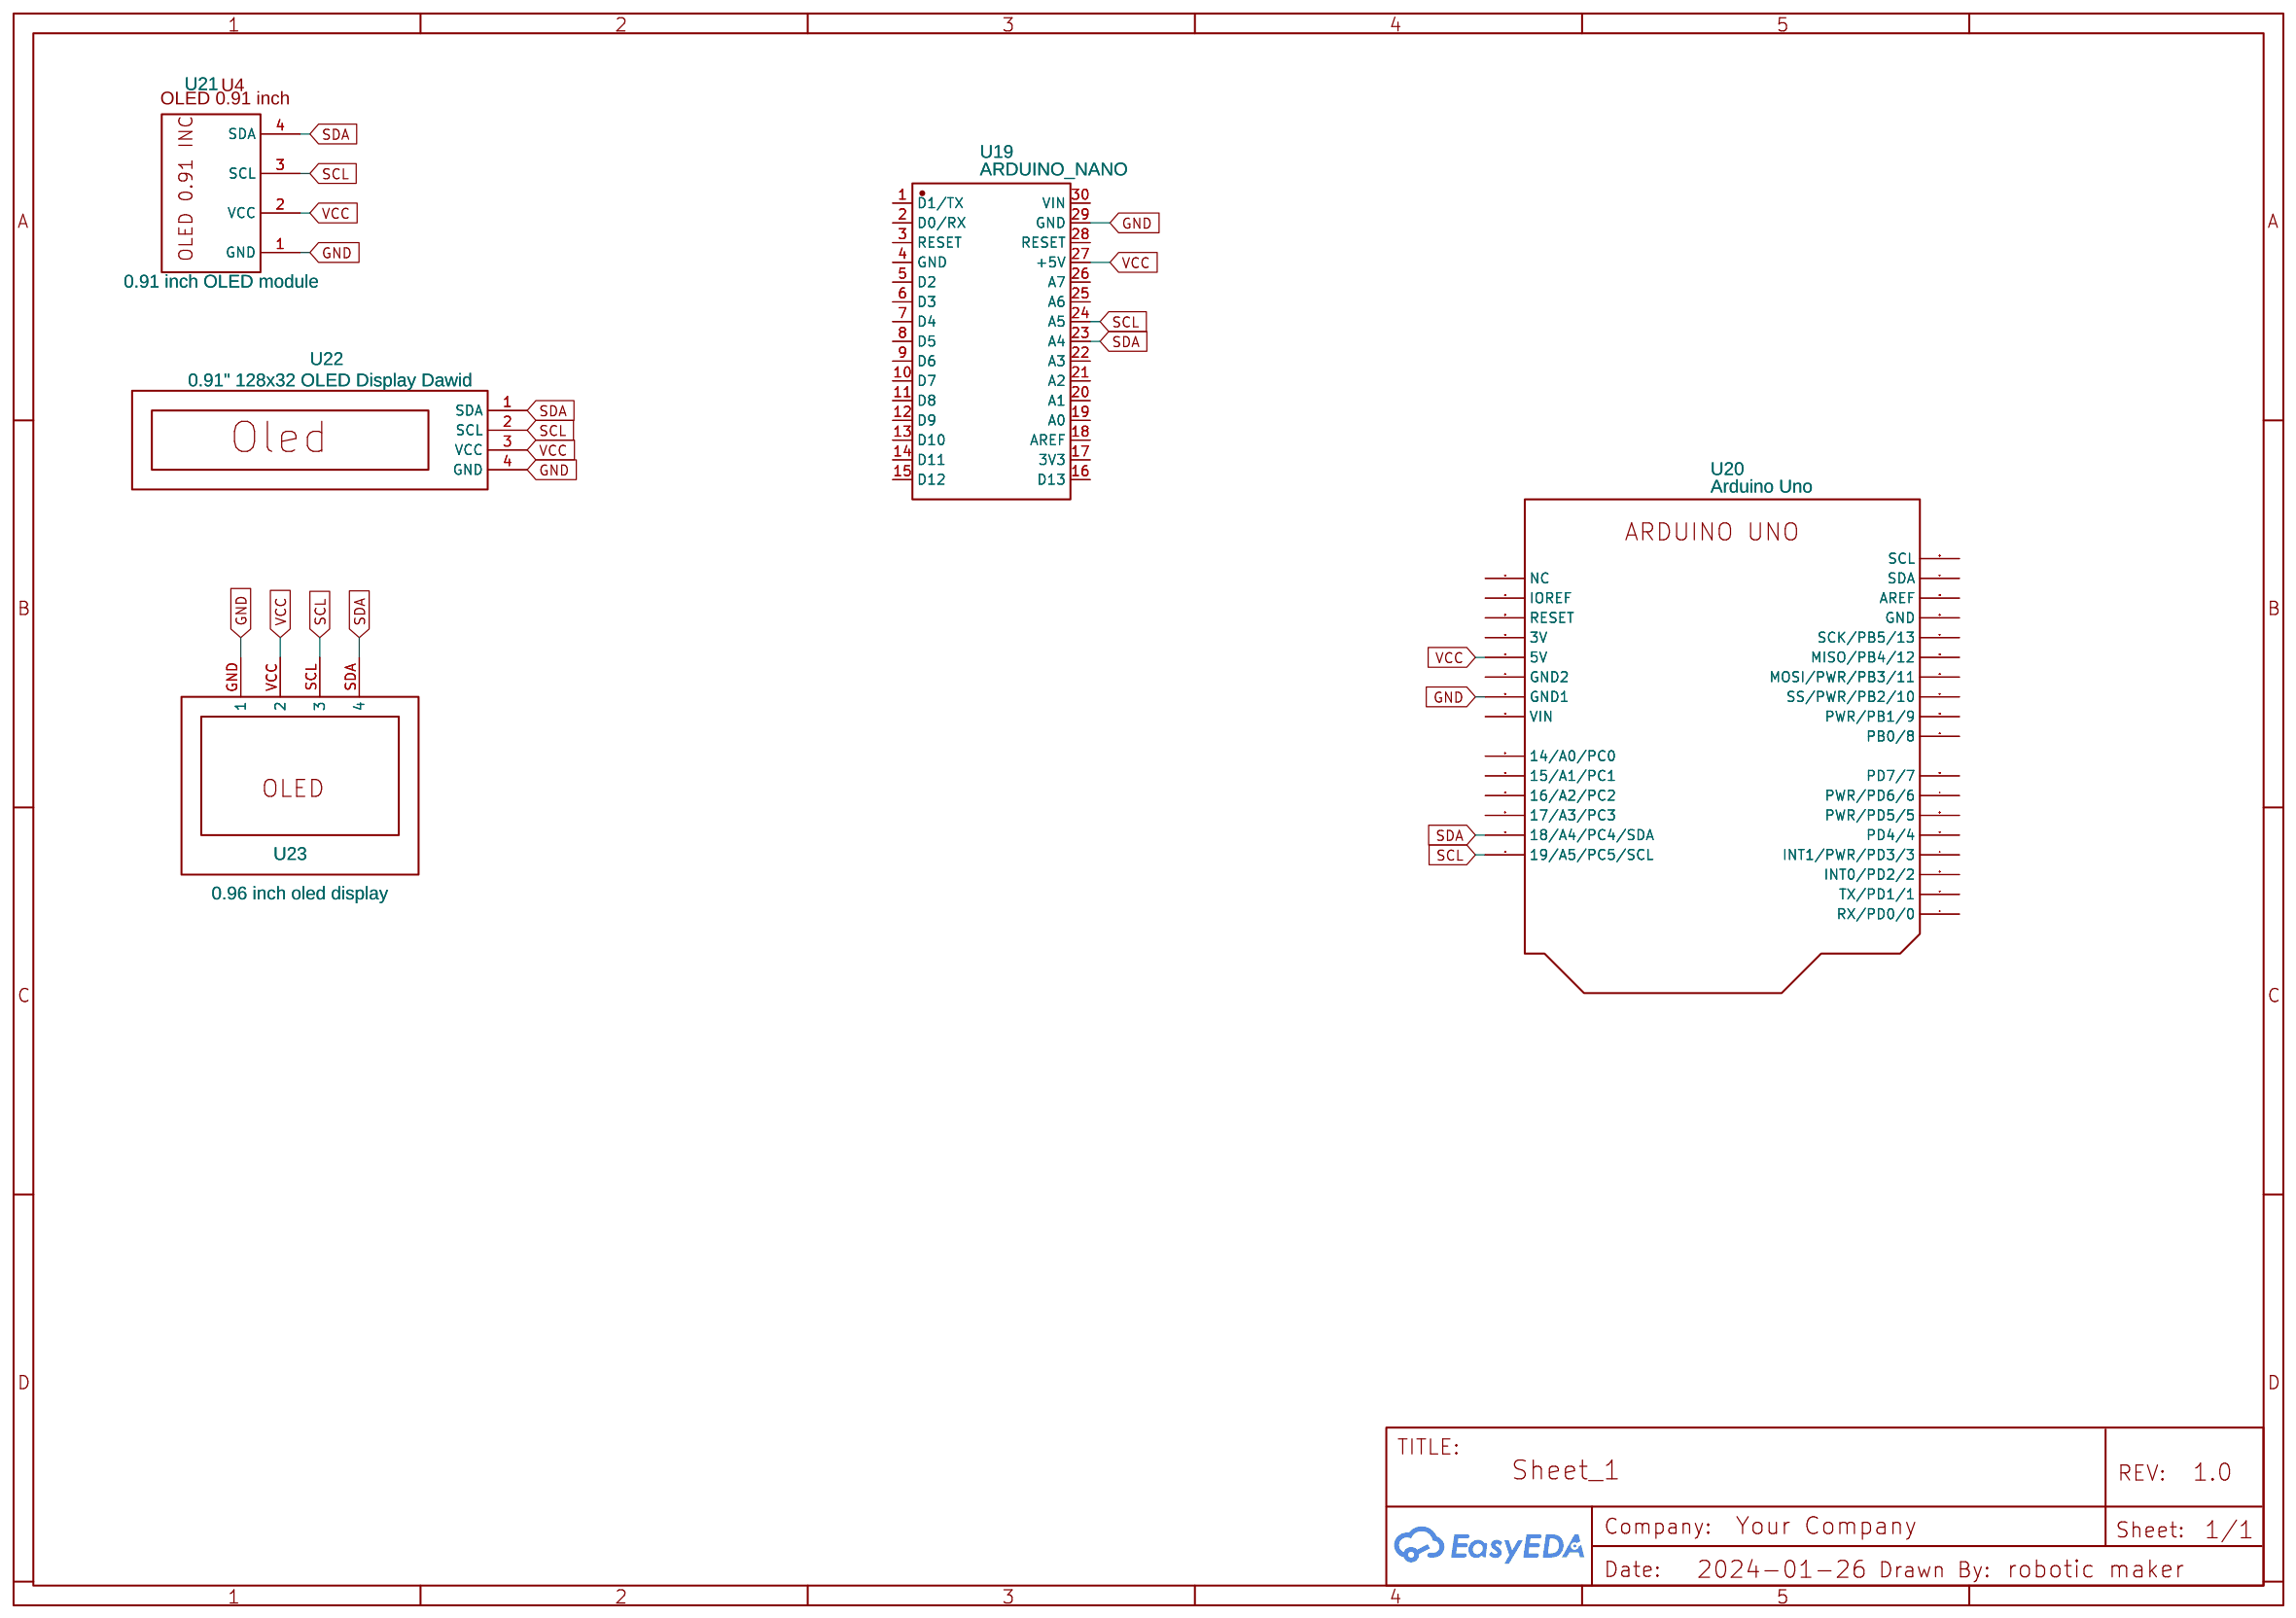
[diagram p9: 0.91 INCH OLED Display]
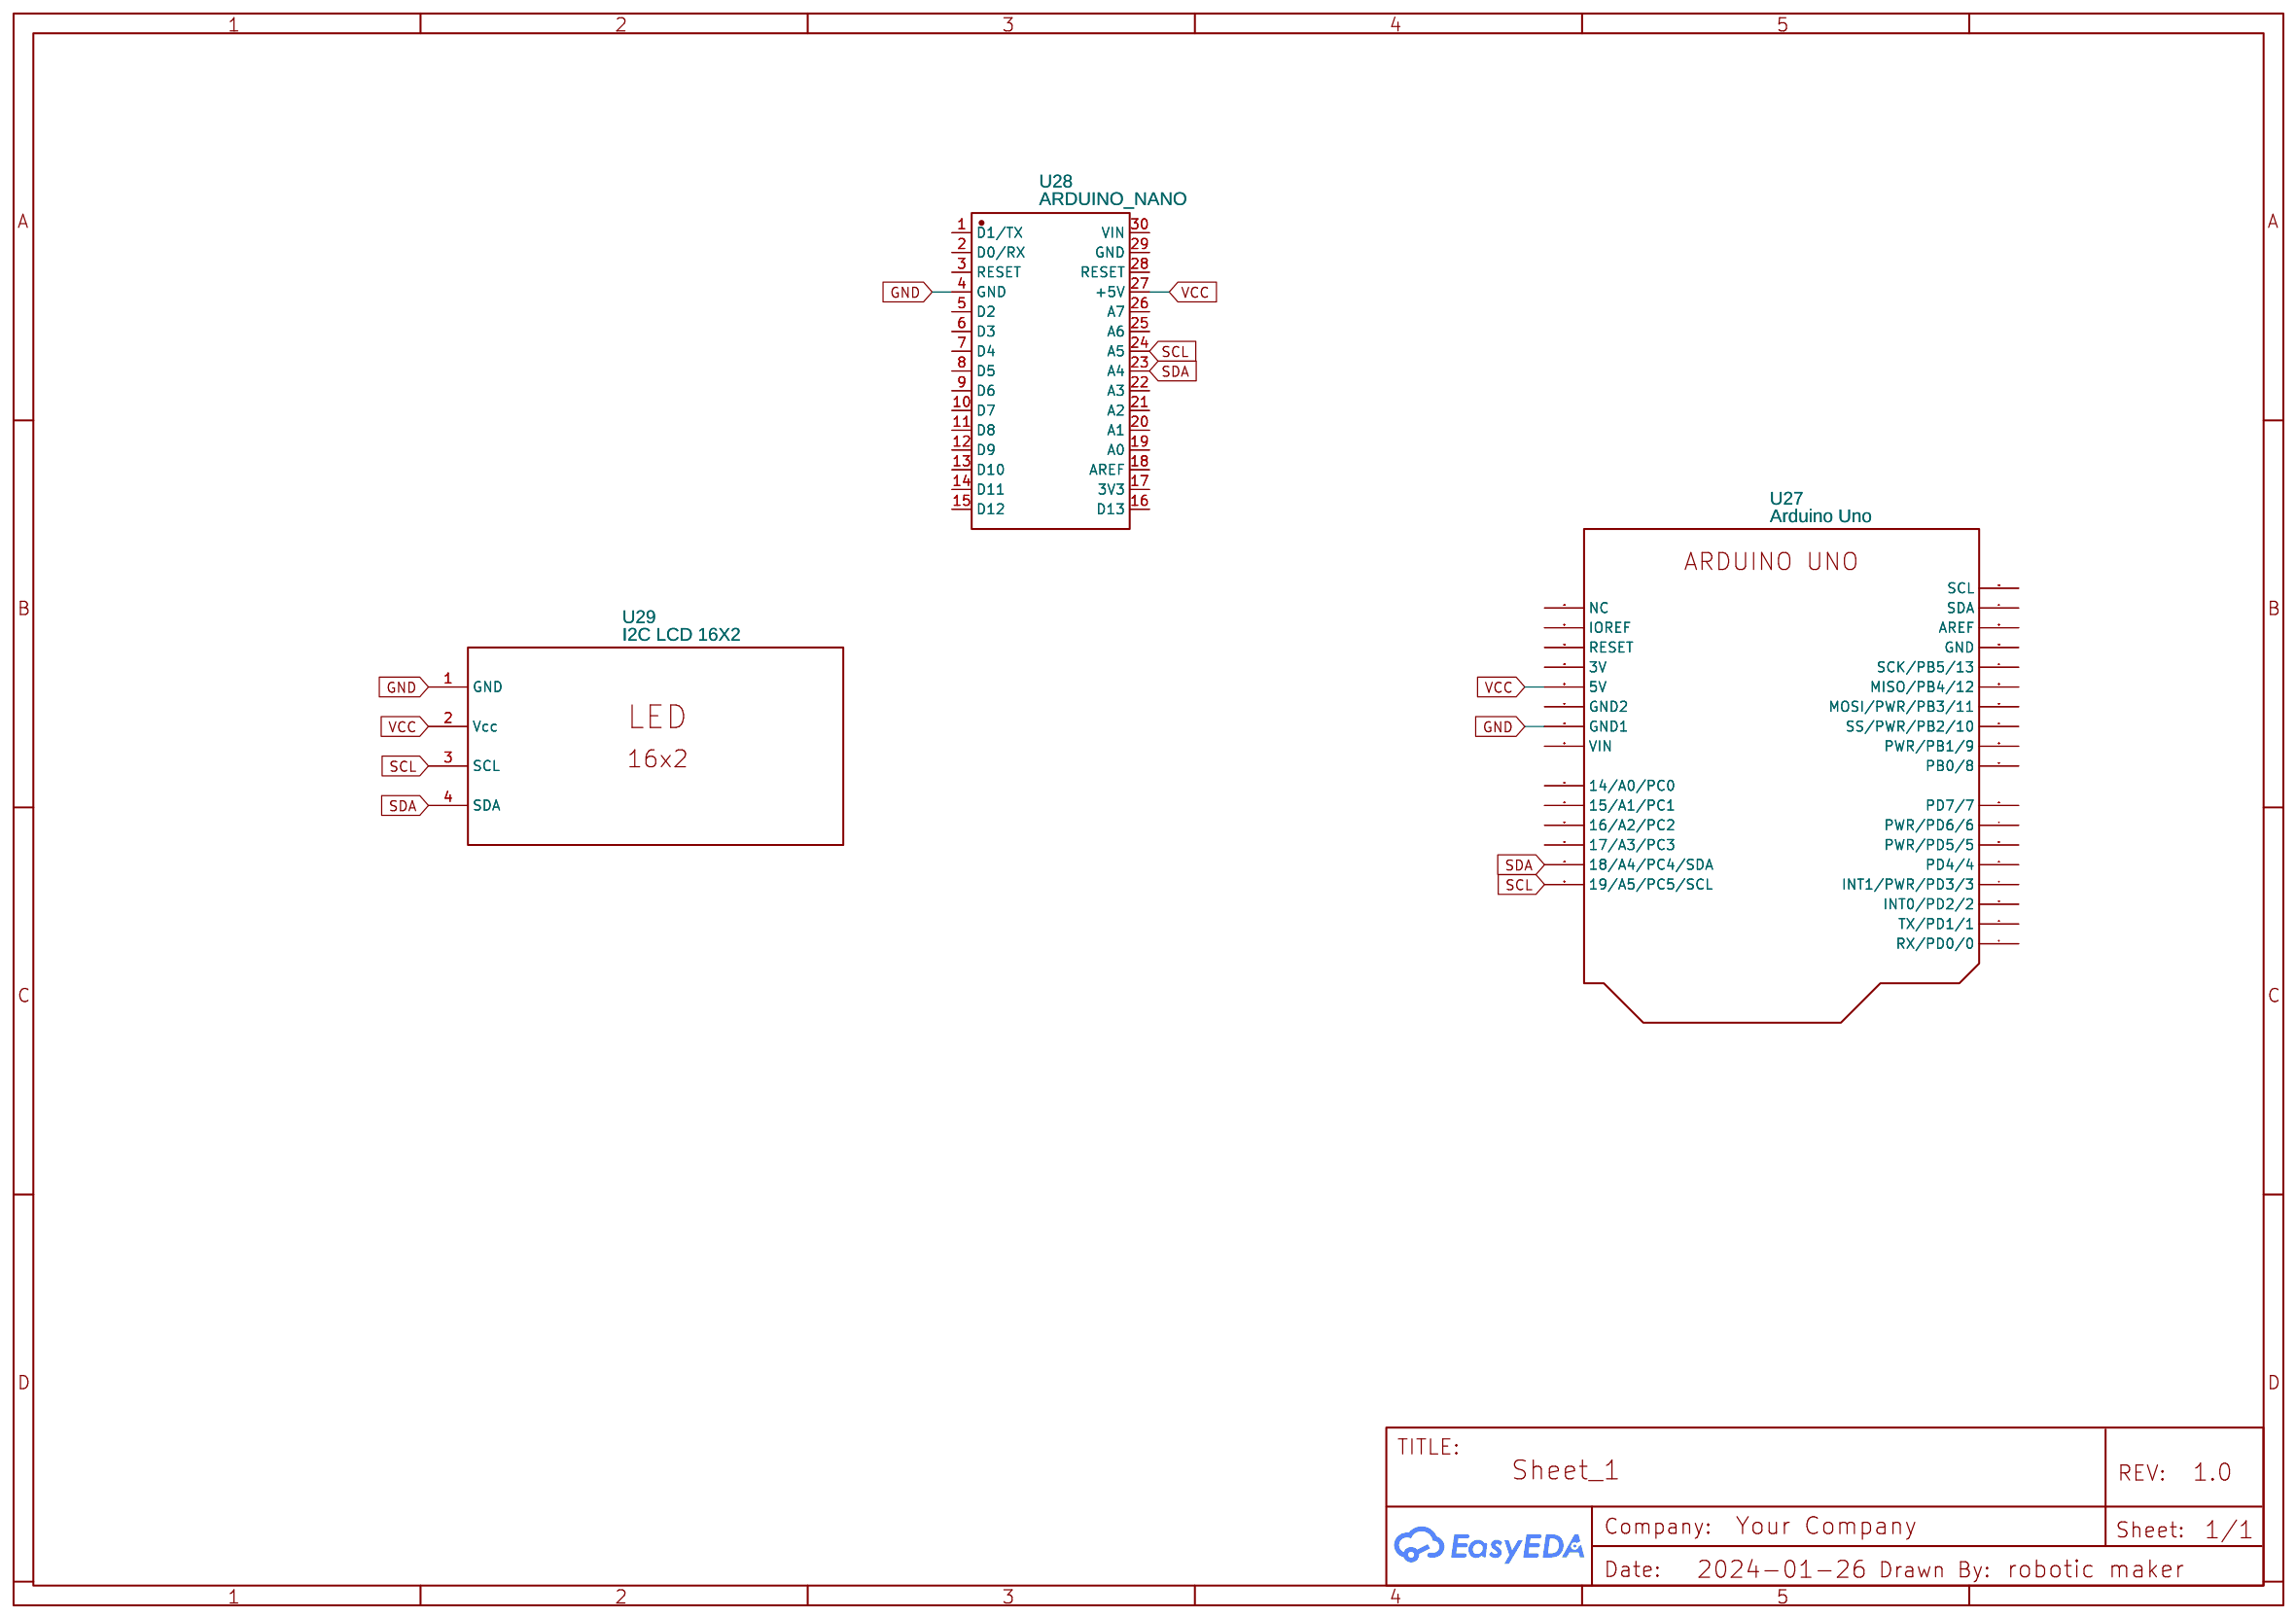
[diagram p10: 16X2 LCD Display I2C]

(export (version "E")
  (design (tool "Eeschema 10.0.6"))
  (components
    (comp (ref "CN3") (value "PINHEADER-6PIN6") (libsource (lib "") (part "PINHEADER-6PIN6")))
    (comp (ref "U38") (value "NO") (libsource (lib "") (part "ESO_SPST_Momentary")))
    (comp (ref "U39") (value "NO") (libsource (lib "") (part "ESO_SPST_Momentary")))
    (comp (ref "U40") (value "NO") (libsource (lib "") (part "ESO_SPST_Momentary")))
    (comp (ref "U41") (value "NO") (libsource (lib "") (part "ESO_SPST_Momentary")))
    (comp (ref "U42") (value "NO") (libsource (lib "") (part "ESO_SPST_Momentary")))
    (comp (ref "U43") (value "NO") (libsource (lib "") (part "ESO_SPST_Momentary")))
    (comp (ref "U44") (value "NO") (libsource (lib "") (part "ESO_SPST_Momentary")))
    (comp (ref "U45") (value "NO") (libsource (lib "") (part "ESO_SPST_Momentary")))
    (comp (ref "U46") (value "NO") (libsource (lib "") (part "ESO_SPST_Momentary")))
    (comp (ref "U47") (value "ARDUINO UNO GD32") (libsource (lib "") (part "ARDUINO UNO GD32")))
    (comp (ref "LCD1") (value "GLCD_128X64") (libsource (lib "") (part "GLCD_128X64")))
    (comp (ref "LCD2") (value "GLCD_128X64") (libsource (lib "") (part "GLCD_128X64_1")))
    (comp (ref "LCD3") (value "LCD 16x2") (libsource (lib "") (part "LCD 16x2")))
    (comp (ref "LCD4")
      (value "LCD1602")
      (fields
        (field (name "Manufacturer Part") "LCM1602K-NSW-BBW")
        (field (name "Manufacturer") "LONTECH(厦门龙特)")
      )
      (libsource (lib "") (part "LCD1602"))
    )
    (comp (ref "PCB1") (value "ARDUINO UNO R3") (libsource (lib "") (part "ARDUINO UNO R3")))
    (comp (ref "PCB2") (value "ARDUINO UNO R3") (libsource (lib "") (part "ARDUINO UNO R3")))
    (comp (ref "R1")
      (value "10K Potentiometer With Knob 90")
      (libsource (lib "") (part "10K-POTENTIOMETER COPY"))
    )
    (comp (ref "R2")
      (value "10K Potentiometer With Knob 90")
      (libsource (lib "") (part "10K-POTENTIOMETER COPY"))
    )
    (comp (ref "U24") (value "ARDUINO_NANO") (libsource (lib "") (part "ARDUINO_NANO")))
    (comp (ref "U26") (value "10k Potentiometer") (libsource (lib "") (part "10k Potentiometer")))
    (comp (ref "U48") (value "1k potentiometer") (libsource (lib "") (part "Pot_blue")))
    (comp (ref "U49")
      (value "6-pin male-male header")
      (fields (field (name "Manufacturer Part") "87224-5") (field (name "Manufacturer") "TE Connectivity"))
      (libsource (lib "") (part "6-pin male-male header"))
    )
    (comp (ref "U50")
      (value "2-PIN-MALE HEADER")
      (fields (field (name "Manufacturer Part") "87224-5") (field (name "Manufacturer") "TE Connectivity"))
      (libsource (lib "") (part "2-PIN-MALE HEADER"))
    )
    (comp (ref "U51") (value "ARDUINO UNO GD32") (libsource (lib "") (part "ARDUINO UNO GD32")))
    (comp (ref "2.3K")
      (value "NO")
      (fields (field (name "Manufacturer") "Huaxing Mechanical-Elec."))
      (libsource (lib "") (part "1/4W-2.2KΩ±1%_1"))
    )
    (comp (ref "2R")
      (value "NO")
      (fields (field (name "Manufacturer") "Huaxing Mechanical-Elec."))
      (libsource (lib "") (part "1/4W-2.2KΩ±1%"))
    )
    (comp (ref "BUZZER3")
      (value "BUZZER")
      (fields (field (name "Manufacturer Part") "buzzer"))
      (libsource (lib "") (part "BUZZER"))
    )
    (comp (ref "C5")
      (value "100UF/16V")
      (fields (field (name "Manufacturer Part") "100uF/16V"))
      (libsource (lib "") (part "100UF/16V"))
    )
    (comp (ref "C6")
      (value "104")
      (fields
        (field (name "Manufacturer Part") "Suppression Capacitor222M/250V")
        (field (name "Manufacturer") "ReliaPro")
      )
      (libsource (lib "") (part "104nf"))
    )
    (comp (ref "LED2") (value "NO") (libsource (lib "") (part "-LED")))
    (comp (ref "P3")
      (value "HEADER PAD 3 PIN")
      (fields
        (field (name "Manufacturer Part") "Female headerHDR1X8-2.54")
        (field (name "Manufacturer") "BOOMELE")
      )
      (libsource (lib "") (part "HEADER PAD 3 PIN"))
    )
    (comp (ref "Q5")
      (value "BC557")
      (fields (field (name "Manufacturer") "CJ(江苏长电/长晶)"))
      (libsource (lib "") (part "BC557"))
    )
    (comp (ref "U52") (value "ARDUINO UNO GD32") (libsource (lib "") (part "ARDUINO UNO GD32")))
    (comp (ref "U53") (value "NO") (libsource (lib "") (part "EM-18")))
    (comp (ref "D3")
      (value "1N4007")
      (fields (field (name "Manufacturer") "ST(先科)"))
      (libsource (lib "") (part "1N4007"))
    )
    (comp (ref "Q6")
      (value "BC548B")
      (fields (field (name "Manufacturer Part") "BC548") (field (name "Manufacturer") "CJ(江苏长电/长晶)"))
      (libsource (lib "") (part "BC548B"))
    )
    (comp (ref "R7") (value "1000Ω") (libsource (lib "") (part "330Ω RESISTANCE")))
    (comp (ref "R8") (value "1000Ω") (libsource (lib "") (part "330Ω RESISTANCE")))
    (comp (ref "R9") (value "1000Ω") (libsource (lib "") (part "330Ω RESISTANCE_1")))
    (comp (ref "U54") (value "ARDUINO UNO GD32") (libsource (lib "") (part "ARDUINO UNO GD32")))
    (comp (ref "U55")
      (value "NO")
      (fields (field (name "Manufacturer Part") "SRD-05VDC-SL-C") (field (name "Manufacturer") "松乐"))
      (libsource (lib "") (part "SRD-05VDC-SL-C"))
    )
    (comp (ref "U56") (value "LED") (libsource (lib "") (part "-LED")))
    (comp (ref "U57") (value "LED") (libsource (lib "") (part "-LED")))
    (comp (ref "U58")
      (value "3 PIN MALE JAMPER")
      (fields (field (name "Manufacturer Part") "1x3 pin header") (field (name "Manufacturer") "NA"))
      (libsource (lib "") (part "3 PIN MALE JAMPER"))
    )
    (comp (ref "U59") (value "3PIN TERMINALBOCK") (libsource (lib "") (part "3PIN TERMINALBOCK")))
    (comp (ref "DD1") (value "DHT-11") (libsource (lib "") (part "DHT-11_1")))
    (comp (ref "U1") (value "Arduino Uno") (libsource (lib "") (part "Arduino Uno")))
    (comp (ref "U2") (value "ARDUINO_NANO") (libsource (lib "") (part "ARDUINO_NANO")))
    (comp (ref "U3") (value "DHT-11") (libsource (lib "") (part "DHT-11")))
    (comp (ref "U4")
      (value "Capacitive Soil Moisture Sensor v1.2")
      (libsource (lib "") (part "Capacitive Soil Moisture Sensor v1.2_1"))
    )
    (comp (ref "U5")
      (value "Capacitive Soil Moisture Sensor v1.2")
      (libsource (lib "") (part "Capacitive Soil Moisture Sensor v1.2"))
    )
    (comp (ref "U6") (value "ARDUINO_NANO") (libsource (lib "") (part "ARDUINO_NANO")))
    (comp (ref "U7") (value "Arduino Uno") (libsource (lib "") (part "Arduino Uno")))
    (comp (ref "U8")
      (value "CAPACITIVE SOIL MOISTURE SENSOR 2")
      (libsource (lib "") (part "CAPACITIVE SOIL MOISTURE SENSOR 2"))
    )
    (comp (ref "H1") (value "4Pin") (libsource (lib "") (part "4Pin")))
    (comp (ref "S1") (value "Soil Moisture Sensor") (libsource (lib "") (part "Soil Moisture Sensor")))
    (comp (ref "U9") (value "ARDUINO_NANO") (libsource (lib "") (part "ARDUINO_NANO")))
    (comp (ref "U10") (value "Arduino Uno") (libsource (lib "") (part "Arduino Uno")))
    (comp (ref "U11") (value "BH1750") (libsource (lib "") (part "BH1750_2")))
    (comp (ref "U12")
      (value "BH1750-PINOUT-NEW")
      (fields (field (name "Manufacturer Part") "New SchematicLib"))
      (libsource (lib "") (part "BH1750-PINOUT-NEW"))
    )
    (comp (ref "U13") (value "BH1750") (libsource (lib "") (part "BH1750")))
    (comp (ref "U14") (value "BH1750") (libsource (lib "") (part "BH1750_1")))
    (comp (ref "U15") (value "ARDUINO_NANO") (libsource (lib "") (part "ARDUINO_NANO")))
    (comp (ref "U16") (value "Arduino Uno") (libsource (lib "") (part "Arduino Uno")))
    (comp (ref "J2")
      (value "RELAY")
      (fields (field (name "Manufacturer Part") "1-Channel 5V Relay Module w/ Opto-isolator"))
      (libsource (lib "") (part "RELAY"))
    )
    (comp (ref "NODE5") (value "NODE_MCU_V3_ESP8266") (libsource (lib "") (part "NODE_MCU_V3_ESP8266")))
    (comp (ref "P1")
      (value "HEADER PAD 3 PIN")
      (fields
        (field (name "Manufacturer Part") "Female headerHDR1X8-2.54")
        (field (name "Manufacturer") "BOOMELE")
      )
      (libsource (lib "") (part "HEADER PAD 3 PIN"))
    )
    (comp (ref "P2")
      (value "HEADER PAD 3 PIN")
      (fields
        (field (name "Manufacturer Part") "Female headerHDR1X8-2.54")
        (field (name "Manufacturer") "BOOMELE")
      )
      (libsource (lib "") (part "HEADER PAD 3 PIN_1"))
    )
    (comp (ref "U17") (value "ARDUINO_NANO") (libsource (lib "") (part "ARDUINO_NANO")))
    (comp (ref "U18") (value "Arduino Uno") (libsource (lib "") (part "Arduino Uno")))
    (comp (ref "U19") (value "ARDUINO_NANO") (libsource (lib "") (part "ARDUINO_NANO")))
    (comp (ref "U20") (value "Arduino Uno") (libsource (lib "") (part "Arduino Uno")))
    (comp (ref "U21") (value "0.91 inch OLED module") (libsource (lib "") (part "0.91 inch OLED module")))
    (comp (ref "U22")
      (value "0.91\" 128x32 OLED Display Dawid")
      (libsource (lib "") (part "0.91{dblquote} 128x32 OLED Display Dawid"))
    )
    (comp (ref "U23") (value "0.96 inch oled display") (libsource (lib "") (part "0.96 inch oled display")))
    (comp (ref "U27") (value "Arduino Uno") (libsource (lib "") (part "Arduino Uno")))
    (comp (ref "U28") (value "ARDUINO_NANO") (libsource (lib "") (part "ARDUINO_NANO")))
    (comp (ref "U29") (value "I2C LCD 16X2") (libsource (lib "") (part "I2C LCD 16X2")))
  )
  (nets
    (net (code "1") (name "3") (class "Default")
      (node (ref "LCD2") (pin "3") (pinfunction "VEE/NC_3") (pintype "bidirectional"))
      (node (ref "R2") (pin "2") (pinfunction "2_2") (pintype "unspecified"))
    )
    (net (code "2") (name "18") (class "Default")
      (node (ref "LCD2") (pin "18") (pinfunction "VO_18") (pintype "bidirectional"))
      (node (ref "R2") (pin "3") (pinfunction "3_3") (pintype "unspecified"))
    )
    (net (code "3") (name "A0") (class "Default")
      (node (ref "H1") (pin "1") (pinfunction "A0_1") (pintype "unspecified"))
      (node (ref "LCD2") (pin "15") (pinfunction "E_15") (pintype "bidirectional"))
      (node (ref "PCB2") (pin "A0") (pinfunction "A0_A0") (pintype "bidirectional"))
      (node (ref "S1") (pin "4") (pinfunction "A0_4") (pintype "unspecified"))
      (node (ref "U10") (pin "24") (pinfunction "14/A0/PC0_24") (pintype "unspecified"))
      (node (ref "U9") (pin "19") (pinfunction "A0_19") (pintype "unspecified"))
    )
    (net (code "4") (name "A1") (class "Default")
      (node (ref "LCD2") (pin "16") (pinfunction "R/W_16") (pintype "bidirectional"))
      (node (ref "PCB2") (pin "A1") (pinfunction "A1_A1") (pintype "bidirectional"))
    )
    (net (code "5") (name "A2") (class "Default")
      (node (ref "LCD2") (pin "5") (pinfunction "NC_5") (pintype "bidirectional"))
      (node (ref "PCB2") (pin "A2") (pinfunction "A2_A2") (pintype "bidirectional"))
    )
    (net (code "6") (name "A3") (class "Default")
      (node (ref "LCD2") (pin "4") (pinfunction "RST_4") (pintype "bidirectional"))
      (node (ref "PCB2") (pin "A3") (pinfunction "A3_A3") (pintype "bidirectional"))
    )
    (net (code "7") (name "A4") (class "Default")
      (node (ref "LCD2") (pin "6") (pinfunction "PSB_6") (pintype "bidirectional"))
      (node (ref "PCB2") (pin "A4") (pinfunction "A4_A4") (pintype "bidirectional"))
    )
    (net (code "8") (name "AD0") (class "Default")
      (node (ref "U12") (pin "2") (pinfunction "AD0_2") (pintype "unspecified"))
      (node (ref "U14") (pin "2") (pinfunction "ADO_2") (pintype "unspecified"))
    )
    (net (code "9") (name "ADDR") (class "Default")
      (node (ref "U11") (pin "5") (pinfunction "5_5") (pintype "unspecified"))
      (node (ref "U13") (pin "5") (pinfunction "ADD*_5") (pintype "unspecified"))
      (node (ref "U15") (pin "22") (pinfunction "A3_22") (pintype "unspecified"))
      (node (ref "U16") (pin "21") (pinfunction "17/A3/PC3_21") (pintype "unspecified"))
    )
    (net (code "10") (name "AOUT") (class "Default")
      (node (ref "U4") (pin "3") (pinfunction "AOUT_3") (pintype "unspecified"))
      (node (ref "U6") (pin "19") (pinfunction "A0_19") (pintype "unspecified"))
      (node (ref "U7") (pin "24") (pinfunction "14/A0/PC0_24") (pintype "unspecified"))
      (node (ref "U8") (pin "3") (pinfunction "AUOT_3") (pintype "unspecified"))
    )
    (net (code "11") (name "C1") (class "Default")
      (node (ref "CN3") (pin "4") (pinfunction "C1_4") (pintype "input"))
      (node (ref "U38") (pin "1") (pinfunction "1_1") (pintype "unspecified"))
      (node (ref "U38") (pin "2") (pinfunction "2_2") (pintype "unspecified"))
      (node (ref "U43") (pin "1") (pinfunction "1_1") (pintype "unspecified"))
      (node (ref "U43") (pin "2") (pinfunction "2_2") (pintype "unspecified"))
      (node (ref "U46") (pin "1") (pinfunction "1_1") (pintype "unspecified"))
      (node (ref "U46") (pin "2") (pinfunction "2_2") (pintype "unspecified"))
      (node (ref "U47") (pin "9") (pinfunction "D8_9") (pintype "unspecified"))
    )
    (net (code "12") (name "C2") (class "Default")
      (node (ref "CN3") (pin "5") (pinfunction "C2_5") (pintype "input"))
      (node (ref "U39") (pin "1") (pinfunction "1_1") (pintype "unspecified"))
      (node (ref "U39") (pin "2") (pinfunction "2_2") (pintype "unspecified"))
      (node (ref "U42") (pin "1") (pinfunction "1_1") (pintype "unspecified"))
      (node (ref "U42") (pin "2") (pinfunction "2_2") (pintype "unspecified"))
      (node (ref "U45") (pin "1") (pinfunction "1_1") (pintype "unspecified"))
      (node (ref "U45") (pin "2") (pinfunction "2_2") (pintype "unspecified"))
      (node (ref "U47") (pin "10") (pinfunction "D9_10") (pintype "unspecified"))
    )
    (net (code "13") (name "C3") (class "Default")
      (node (ref "CN3") (pin "6") (pinfunction "C3_6") (pintype "input"))
      (node (ref "U40") (pin "1") (pinfunction "1_1") (pintype "unspecified"))
      (node (ref "U40") (pin "2") (pinfunction "2_2") (pintype "unspecified"))
      (node (ref "U41") (pin "1") (pinfunction "1_1") (pintype "unspecified"))
      (node (ref "U41") (pin "2") (pinfunction "2_2") (pintype "unspecified"))
      (node (ref "U44") (pin "1") (pinfunction "1_1") (pintype "unspecified"))
      (node (ref "U44") (pin "2") (pinfunction "2_2") (pintype "unspecified"))
      (node (ref "U47") (pin "11") (pinfunction "D10_11") (pintype "unspecified"))
    )
    (net (code "14") (name "COM") (class "Default")
      (node (ref "U54") (pin "25") (pinfunction "VIN_25") (pintype "passive"))
      (node (ref "U55") (pin "3") (pinfunction "COM_3") (pintype "unspecified"))
      (node (ref "U59") (pin "2") (pinfunction "2_2") (pintype "unspecified"))
    )
    (net (code "15") (name "D0") (class "Default")
      (node (ref "H1") (pin "2") (pinfunction "D0_2") (pintype "unspecified"))
      (node (ref "S1") (pin "3") (pinfunction "D0_3") (pintype "unspecified"))
      (node (ref "U10") (pin "9") (pinfunction "PB0/8_9") (pintype "unspecified"))
      (node (ref "U9") (pin "11") (pinfunction "D8_11") (pintype "unspecified"))
    )
    (net (code "16") (name "D4") (class "Default")
      (node (ref "LCD2") (pin "11") (pinfunction "DB3_11") (pintype "bidirectional"))
      (node (ref "LCD3") (pin "11") (pinfunction "DB4_11") (pintype "unspecified"))
      (node (ref "LCD4") (pin "11") (pinfunction "DB4_11") (pintype "unspecified"))
      (node (ref "PCB2") (pin "4") (pinfunction "4_4") (pintype "bidirectional"))
      (node (ref "U24") (pin "21") (pinfunction "A2_21") (pintype "unspecified"))
      (node (ref "U49") (pin "D4") (pinfunction "4_D4") (pintype "unspecified"))
      (node (ref "U51") (pin "21") (pinfunction "A3_21") (pintype "unspecified"))
    )
    (net (code "17") (name "D5") (class "Default")
      (node (ref "LCD2") (pin "12") (pinfunction "DB2_12") (pintype "bidirectional"))
      (node (ref "LCD3") (pin "12") (pinfunction "DB5_12") (pintype "unspecified"))
      (node (ref "LCD4") (pin "12") (pinfunction "DB5_12") (pintype "unspecified"))
      (node (ref "PCB2") (pin "5") (pinfunction "5_5") (pintype "bidirectional"))
      (node (ref "U24") (pin "22") (pinfunction "A3_22") (pintype "unspecified"))
      (node (ref "U49") (pin "D5") (pinfunction "3_D5") (pintype "unspecified"))
      (node (ref "U51") (pin "22") (pinfunction "A2_22") (pintype "unspecified"))
    )
    (net (code "18") (name "D6") (class "Default")
      (node (ref "LCD2") (pin "13") (pinfunction "DB1_13") (pintype "bidirectional"))
      (node (ref "LCD3") (pin "13") (pinfunction "DB6_13") (pintype "unspecified"))
      (node (ref "LCD4") (pin "13") (pinfunction "DB6_13") (pintype "unspecified"))
      (node (ref "PCB2") (pin "6") (pinfunction "6_6") (pintype "bidirectional"))
      (node (ref "U24") (pin "23") (pinfunction "A4_23") (pintype "unspecified"))
      (node (ref "U49") (pin "D6") (pinfunction "2_D6") (pintype "unspecified"))
      (node (ref "U51") (pin "23") (pinfunction "A1_23") (pintype "unspecified"))
    )
    (net (code "19") (name "D7") (class "Default")
      (node (ref "LCD2") (pin "14") (pinfunction "DB0_14") (pintype "bidirectional"))
      (node (ref "LCD3") (pin "14") (pinfunction "DB7_14") (pintype "unspecified"))
      (node (ref "LCD4") (pin "14") (pinfunction "DB7_14") (pintype "unspecified"))
      (node (ref "PCB2") (pin "7") (pinfunction "7_7") (pintype "bidirectional"))
      (node (ref "U24") (pin "24") (pinfunction "A5_24") (pintype "unspecified"))
      (node (ref "U49") (pin "D7") (pinfunction "1_D7") (pintype "unspecified"))
      (node (ref "U51") (pin "24") (pinfunction "A0_24") (pintype "unspecified"))
    )
    (net (code "20") (name "D8") (class "Default")
      (node (ref "LCD2") (pin "7") (pinfunction "DB7_7") (pintype "bidirectional"))
      (node (ref "PCB2") (pin "8") (pinfunction "8_8") (pintype "bidirectional"))
    )
    (net (code "21") (name "D9") (class "Default")
      (node (ref "LCD2") (pin "8") (pinfunction "DB6_8") (pintype "bidirectional"))
      (node (ref "PCB2") (pin "9") (pinfunction "9_9") (pintype "bidirectional"))
    )
    (net (code "22") (name "D10") (class "Default")
      (node (ref "LCD2") (pin "9") (pinfunction "DB5_9") (pintype "bidirectional"))
      (node (ref "PCB2") (pin "10") (pinfunction "10_10") (pintype "bidirectional"))
    )
    (net (code "23") (name "D11") (class "Default")
      (node (ref "LCD2") (pin "10") (pinfunction "DB4_10") (pintype "bidirectional"))
      (node (ref "PCB2") (pin "11") (pinfunction "11_11") (pintype "bidirectional"))
    )
    (net (code "24") (name "DATA") (class "Default")
      (node (ref "DD1") (pin "2") (pinfunction "DATA_2") (pintype "unspecified"))
      (node (ref "U1") (pin "7") (pinfunction "PWR/PD6/6_7") (pintype "unspecified"))
      (node (ref "U2") (pin "6") (pinfunction "D3_6") (pintype "unspecified"))
      (node (ref "U3") (pin "2") (pinfunction "DATA_2") (pintype "unspecified"))
    )
    (net (code "25") (name "E") (class "Default")
      (node (ref "LCD3") (pin "6") (pinfunction "E_6") (pintype "unspecified"))
      (node (ref "LCD4") (pin "6") (pinfunction "E_6") (pintype "unspecified"))
      (node (ref "U24") (pin "20") (pinfunction "A1_20") (pintype "unspecified"))
      (node (ref "U49") (pin "E") (pinfunction "5_E") (pintype "unspecified"))
      (node (ref "U51") (pin "20") (pinfunction "A4_20") (pintype "unspecified"))
    )
    (net (code "26") (name "GND") (class "Default")
      (node (ref "BUZZER3") (pin "1") (pinfunction "-_1") (pintype "unspecified"))
      (node (ref "C5") (pin "2") (pinfunction "2_2") (pintype "input"))
      (node (ref "C6") (pin "1") (pinfunction "1_1") (pintype "input"))
      (node (ref "DD1") (pin "4") (pinfunction "GND_4") (pintype "unspecified"))
      (node (ref "H1") (pin "3") (pinfunction "GND_3") (pintype "unspecified"))
      (node (ref "J2") (pin "14") (pinfunction "GND_14") (pintype "unspecified"))
      (node (ref "LCD2") (pin "1") (pinfunction "K_1") (pintype "bidirectional"))
      (node (ref "LCD2") (pin "20") (pinfunction "GND_20") (pintype "bidirectional"))
      (node (ref "LCD3") (pin "1") (pinfunction "Vss_1") (pintype "unspecified"))
      (node (ref "LCD3") (pin "16") (pinfunction "K_16") (pintype "unspecified"))
      (node (ref "LCD3") (pin "5") (pinfunction "RW_5") (pintype "unspecified"))
      (node (ref "LCD4") (pin "1") (pinfunction "VSS_1") (pintype "unspecified"))
      (node (ref "LCD4") (pin "16") (pinfunction "BLK_16") (pintype "unspecified"))
      (node (ref "LCD4") (pin "5") (pinfunction "R/W_5") (pintype "unspecified"))
      (node (ref "LED2") (pin "CATHODE") (pinfunction "CATHODE_CATHODE") (pintype "unspecified"))
      (node (ref "NODE5") (pin "17") (pinfunction "GND_17") (pintype "unspecified"))
      (node (ref "P1") (pin "2") (pinfunction "GND_2") (pintype "input"))
      (node (ref "P2") (pin "1") (pinfunction "GND_1") (pintype "input"))
      (node (ref "P3") (pin "2") (pinfunction "2_2") (pintype "input"))
      (node (ref "PCB2") (pin "GND..") (pinfunction "GND.._GND..") (pintype "bidirectional"))
      (node (ref "Q6") (pin "3") (pinfunction "E_3") (pintype "unspecified"))
      (node (ref "R2") (pin "1") (pinfunction "1_1") (pintype "unspecified"))
      (node (ref "S1") (pin "2") (pinfunction "GND_2") (pintype "unspecified"))
      (node (ref "U1") (pin "26") (pinfunction "GND1_26") (pintype "passive"))
      (node (ref "U10") (pin "26") (pinfunction "GND1_26") (pintype "passive"))
      (node (ref "U11") (pin "2") (pinfunction "2_2") (pintype "unspecified"))
      (node (ref "U12") (pin "1") (pinfunction "GND_1") (pintype "unspecified"))
      (node (ref "U13") (pin "2") (pinfunction "GND_2") (pintype "unspecified"))
      (node (ref "U14") (pin "1") (pinfunction "GND_1") (pintype "unspecified"))
      (node (ref "U15") (pin "29") (pinfunction "GND_29") (pintype "unspecified"))
      (node (ref "U16") (pin "26") (pinfunction "GND1_26") (pintype "passive"))
      (node (ref "U17") (pin "29") (pinfunction "GND_29") (pintype "unspecified"))
      (node (ref "U18") (pin "26") (pinfunction "GND1_26") (pintype "passive"))
      (node (ref "U19") (pin "29") (pinfunction "GND_29") (pintype "unspecified"))
      (node (ref "U2") (pin "4") (pinfunction "GND_4") (pintype "unspecified"))
      (node (ref "U20") (pin "26") (pinfunction "GND1_26") (pintype "passive"))
      (node (ref "U21") (pin "1") (pinfunction "GND_1") (pintype "unspecified"))
      (node (ref "U22") (pin "4") (pinfunction "GND_4") (pintype "unspecified"))
      (node (ref "U23") (pin "GND") (pinfunction "1_GND") (pintype "unspecified"))
      (node (ref "U24") (pin "29") (pinfunction "GND_29") (pintype "unspecified"))
      (node (ref "U26") (pin "3") (pinfunction "3_3") (pintype "unspecified"))
      (node (ref "U27") (pin "26") (pinfunction "GND1_26") (pintype "passive"))
      (node (ref "U28") (pin "4") (pinfunction "GND_4") (pintype "unspecified"))
      (node (ref "U29") (pin "1") (pinfunction "GND_1") (pintype "unspecified"))
      (node (ref "U3") (pin "3") (pinfunction "GND_3") (pintype "unspecified"))
      (node (ref "U4") (pin "1") (pinfunction "GND_1") (pintype "unspecified"))
      (node (ref "U48") (pin "1") (pinfunction "1_1") (pintype "input"))
      (node (ref "U50") (pin "GND") (pinfunction "2_GND") (pintype "unspecified"))
      (node (ref "U51") (pin "26") (pinfunction "GND1_26") (pintype "passive"))
      (node (ref "U52") (pin "26") (pinfunction "GND1_26") (pintype "passive"))
      (node (ref "U53") (pin "3") (pinfunction "GND_3") (pintype "unspecified"))
      (node (ref "U54") (pin "26") (pinfunction "GND1_26") (pintype "passive"))
      (node (ref "U57") (pin "CATHODE") (pinfunction "CATHODE_CATHODE") (pintype "unspecified"))
      (node (ref "U58") (pin "2") (pinfunction "2_2") (pintype "unspecified"))
      (node (ref "U6") (pin "4") (pinfunction "GND_4") (pintype "unspecified"))
      (node (ref "U7") (pin "26") (pinfunction "GND1_26") (pintype "passive"))
      (node (ref "U8") (pin "1") (pinfunction "GND_1") (pintype "unspecified"))
      (node (ref "U9") (pin "4") (pinfunction "GND_4") (pintype "unspecified"))
    )
    (net (code "27") (name "IN") (class "Default")
      (node (ref "R9") (pin "2") (pinfunction "2_2") (pintype "unspecified"))
      (node (ref "U54") (pin "3") (pinfunction "D2_3") (pintype "unspecified"))
      (node (ref "U58") (pin "3") (pinfunction "3_3") (pintype "unspecified"))
    )
    (net (code "28") (name "NC") (class "Default")
      (node (ref "U55") (pin "4") (pinfunction "NC_4") (pintype "unspecified"))
      (node (ref "U59") (pin "1") (pinfunction "1_1") (pintype "unspecified"))
    )
    (net (code "29") (name "NO") (class "Default")
      (node (ref "U59") (pin "3") (pinfunction "3_3") (pintype "unspecified"))
    )
    (net (code "30") (name "Net-(2R-Pad2)") (class "Default")
      (node (ref "2R") (pin "2") (pinfunction "2_2") (pintype "unspecified"))
      (node (ref "LED2") (pin "ANODE") (pinfunction "ANODE_ANODE") (pintype "unspecified"))
    )
    (net (code "31") (name "Net-(BUZZER3-+)") (class "Default")
      (node (ref "2R") (pin "1") (pinfunction "1_1") (pintype "unspecified"))
      (node (ref "BUZZER3") (pin "2") (pinfunction "+_2") (pintype "unspecified"))
      (node (ref "Q5") (pin "1") (pinfunction "C_1") (pintype "unspecified"))
    )
    (net (code "32") (name "Net-(D3-A)") (class "Default")
      (node (ref "D3") (pin "2") (pinfunction "A_2") (pintype "unspecified"))
      (node (ref "Q6") (pin "1") (pinfunction "C_1") (pintype "unspecified"))
      (node (ref "U55") (pin "1") (pinfunction "OT_1") (pintype "unspecified"))
      (node (ref "U56") (pin "CATHODE") (pinfunction "CATHODE_CATHODE") (pintype "unspecified"))
    )
    (net (code "33") (name "Net-(LCD1-A)") (class "Default")
      (node (ref "LCD1") (pin "19") (pinfunction "VCC_19") (pintype "bidirectional"))
      (node (ref "LCD1") (pin "2") (pinfunction "A_2") (pintype "bidirectional"))
      (node (ref "PCB1") (pin "5V") (pinfunction "5V_5V") (pintype "bidirectional"))
    )
    (net (code "34") (name "Net-(LCD1-CS1)") (class "Default")
      (node (ref "LCD1") (pin "6") (pinfunction "CS1_6") (pintype "bidirectional"))
      (node (ref "PCB1") (pin "A4") (pinfunction "A4_A4") (pintype "bidirectional"))
    )
    (net (code "35") (name "Net-(LCD1-CS2)") (class "Default")
      (node (ref "LCD1") (pin "5") (pinfunction "CS2_5") (pintype "bidirectional"))
      (node (ref "PCB1") (pin "A2") (pinfunction "A2_A2") (pintype "bidirectional"))
    )
    (net (code "36") (name "Net-(LCD1-DB0)") (class "Default")
      (node (ref "LCD1") (pin "14") (pinfunction "DB0_14") (pintype "bidirectional"))
      (node (ref "PCB1") (pin "7") (pinfunction "7_7") (pintype "bidirectional"))
    )
    (net (code "37") (name "Net-(LCD1-DB1)") (class "Default")
      (node (ref "LCD1") (pin "13") (pinfunction "DB1_13") (pintype "bidirectional"))
      (node (ref "PCB1") (pin "6") (pinfunction "6_6") (pintype "bidirectional"))
    )
    (net (code "38") (name "Net-(LCD1-DB2)") (class "Default")
      (node (ref "LCD1") (pin "12") (pinfunction "DB2_12") (pintype "bidirectional"))
      (node (ref "PCB1") (pin "5") (pinfunction "5_5") (pintype "bidirectional"))
    )
    (net (code "39") (name "Net-(LCD1-DB3)") (class "Default")
      (node (ref "LCD1") (pin "11") (pinfunction "DB3_11") (pintype "bidirectional"))
      (node (ref "PCB1") (pin "4") (pinfunction "4_4") (pintype "bidirectional"))
    )
    (net (code "40") (name "Net-(LCD1-DB4)") (class "Default")
      (node (ref "LCD1") (pin "10") (pinfunction "DB4_10") (pintype "bidirectional"))
      (node (ref "PCB1") (pin "11") (pinfunction "11_11") (pintype "bidirectional"))
    )
    (net (code "41") (name "Net-(LCD1-DB5)") (class "Default")
      (node (ref "LCD1") (pin "9") (pinfunction "DB5_9") (pintype "bidirectional"))
      (node (ref "PCB1") (pin "10") (pinfunction "10_10") (pintype "bidirectional"))
    )
    (net (code "42") (name "Net-(LCD1-DB6)") (class "Default")
      (node (ref "LCD1") (pin "8") (pinfunction "DB6_8") (pintype "bidirectional"))
      (node (ref "PCB1") (pin "9") (pinfunction "9_9") (pintype "bidirectional"))
    )
    (net (code "43") (name "Net-(LCD1-DB7)") (class "Default")
      (node (ref "LCD1") (pin "7") (pinfunction "DB7_7") (pintype "bidirectional"))
      (node (ref "PCB1") (pin "8") (pinfunction "8_8") (pintype "bidirectional"))
    )
    (net (code "44") (name "Net-(LCD1-E)") (class "Default")
      (node (ref "LCD1") (pin "15") (pinfunction "E_15") (pintype "bidirectional"))
      (node (ref "PCB1") (pin "A0") (pinfunction "A0_A0") (pintype "bidirectional"))
    )
    (net (code "45") (name "Net-(LCD1-GND)") (class "Default")
      (node (ref "LCD1") (pin "1") (pinfunction "K_1") (pintype "bidirectional"))
      (node (ref "LCD1") (pin "20") (pinfunction "GND_20") (pintype "bidirectional"))
      (node (ref "PCB1") (pin "GND") (pinfunction "GND_GND") (pintype "bidirectional"))
      (node (ref "R1") (pin "1") (pinfunction "1_1") (pintype "unspecified"))
    )
    (net (code "46") (name "Net-(LCD1-RS)") (class "Default")
      (node (ref "LCD1") (pin "17") (pinfunction "RS_17") (pintype "bidirectional"))
      (node (ref "PCB1") (pin "RESET") (pinfunction "RESET_RESET") (pintype "bidirectional"))
    )
    (net (code "47") (name "Net-(LCD1-RST)") (class "Default")
      (node (ref "LCD1") (pin "4") (pinfunction "RST_4") (pintype "bidirectional"))
      (node (ref "PCB1") (pin "A3") (pinfunction "A3_A3") (pintype "bidirectional"))
    )
    (net (code "48") (name "Net-(LCD1-R{slash}W)") (class "Default")
      (node (ref "LCD1") (pin "16") (pinfunction "R/W_16") (pintype "bidirectional"))
      (node (ref "PCB1") (pin "A1") (pinfunction "A1_A1") (pintype "bidirectional"))
    )
    (net (code "49") (name "Net-(LCD1-VEE{slash}NC)") (class "Default")
      (node (ref "LCD1") (pin "3") (pinfunction "VEE/NC_3") (pintype "bidirectional"))
      (node (ref "R1") (pin "2") (pinfunction "2_2") (pintype "unspecified"))
    )
    (net (code "50") (name "Net-(LCD1-VO)") (class "Default")
      (node (ref "LCD1") (pin "18") (pinfunction "VO_18") (pintype "bidirectional"))
      (node (ref "R1") (pin "3") (pinfunction "3_3") (pintype "unspecified"))
    )
    (net (code "51") (name "Net-(LCD3-V0)") (class "Default")
      (node (ref "LCD3") (pin "3") (pinfunction "V0_3") (pintype "unspecified"))
      (node (ref "U48") (pin "2") (pinfunction "3_2") (pintype "input"))
    )
    (net (code "52") (name "Net-(LCD4-VO)") (class "Default")
      (node (ref "LCD4") (pin "3") (pinfunction "VO_3") (pintype "unspecified"))
      (node (ref "U26") (pin "1") (pinfunction "1_1") (pintype "unspecified"))
    )
    (net (code "53") (name "Net-(Q5-B)") (class "Default")
      (node (ref "2.3K") (pin "2") (pinfunction "2_2") (pintype "unspecified"))
      (node (ref "Q5") (pin "2") (pinfunction "B_2") (pintype "unspecified"))
    )
    (net (code "54") (name "Net-(Q6-B)") (class "Default")
      (node (ref "Q6") (pin "2") (pinfunction "B_2") (pintype "unspecified"))
      (node (ref "R9") (pin "1") (pinfunction "1_1") (pintype "unspecified"))
    )
    (net (code "55") (name "Net-(R7-Pad1)") (class "Default")
      (node (ref "R7") (pin "1") (pinfunction "1_1") (pintype "unspecified"))
      (node (ref "U56") (pin "ANODE") (pinfunction "ANODE_ANODE") (pintype "unspecified"))
    )
    (net (code "56") (name "Net-(R8-Pad1)") (class "Default")
      (node (ref "R8") (pin "1") (pinfunction "1_1") (pintype "unspecified"))
      (node (ref "U57") (pin "ANODE") (pinfunction "ANODE_ANODE") (pintype "unspecified"))
    )
    (net (code "57") (name "Net-(U53-LED)") (class "Default")
      (node (ref "2.3K") (pin "1") (pinfunction "1_1") (pintype "unspecified"))
      (node (ref "U53") (pin "4") (pinfunction "LED_4") (pintype "unspecified"))
    )
    (net (code "58") (name "OUT") (class "Default")
      (node (ref "P3") (pin "3") (pinfunction "3_3") (pintype "input"))
      (node (ref "U52") (pin "1") (pinfunction "D0_1") (pintype "unspecified"))
      (node (ref "U53") (pin "8") (pinfunction "TX_8") (pintype "unspecified"))
    )
    (net (code "59") (name "R1") (class "Default")
      (node (ref "CN3") (pin "1") (pinfunction "R1_1") (pintype "input"))
      (node (ref "U38") (pin "3") (pinfunction "3_3") (pintype "unspecified"))
      (node (ref "U38") (pin "4") (pinfunction "4_4") (pintype "unspecified"))
      (node (ref "U39") (pin "3") (pinfunction "3_3") (pintype "unspecified"))
      (node (ref "U39") (pin "4") (pinfunction "4_4") (pintype "unspecified"))
      (node (ref "U40") (pin "3") (pinfunction "3_3") (pintype "unspecified"))
      (node (ref "U40") (pin "4") (pinfunction "4_4") (pintype "unspecified"))
      (node (ref "U47") (pin "6") (pinfunction "D5_6") (pintype "unspecified"))
    )
    (net (code "60") (name "R2") (class "Default")
      (node (ref "CN3") (pin "2") (pinfunction "R2_2") (pintype "input"))
      (node (ref "U41") (pin "3") (pinfunction "3_3") (pintype "unspecified"))
      (node (ref "U41") (pin "4") (pinfunction "4_4") (pintype "unspecified"))
      (node (ref "U42") (pin "3") (pinfunction "3_3") (pintype "unspecified"))
      (node (ref "U42") (pin "4") (pinfunction "4_4") (pintype "unspecified"))
      (node (ref "U43") (pin "3") (pinfunction "3_3") (pintype "unspecified"))
      (node (ref "U43") (pin "4") (pinfunction "4_4") (pintype "unspecified"))
      (node (ref "U47") (pin "7") (pinfunction "D6_7") (pintype "unspecified"))
    )
    (net (code "61") (name "R3") (class "Default")
      (node (ref "CN3") (pin "3") (pinfunction "R3_3") (pintype "input"))
      (node (ref "U44") (pin "3") (pinfunction "3_3") (pintype "unspecified"))
      (node (ref "U44") (pin "4") (pinfunction "4_4") (pintype "unspecified"))
      (node (ref "U45") (pin "3") (pinfunction "3_3") (pintype "unspecified"))
      (node (ref "U45") (pin "4") (pinfunction "4_4") (pintype "unspecified"))
      (node (ref "U46") (pin "3") (pinfunction "3_3") (pintype "unspecified"))
      (node (ref "U46") (pin "4") (pinfunction "4_4") (pintype "unspecified"))
      (node (ref "U47") (pin "8") (pinfunction "D7_8") (pintype "unspecified"))
    )
    (net (code "62") (name "RS") (class "Default")
      (node (ref "LCD3") (pin "4") (pinfunction "RS_4") (pintype "unspecified"))
      (node (ref "LCD4") (pin "4") (pinfunction "RS_4") (pintype "unspecified"))
      (node (ref "U24") (pin "19") (pinfunction "A0_19") (pintype "unspecified"))
      (node (ref "U49") (pin "RS") (pinfunction "6_RS") (pintype "unspecified"))
      (node (ref "U51") (pin "19") (pinfunction "A5_19") (pintype "unspecified"))
    )
    (net (code "63") (name "RST") (class "Default")
      (node (ref "LCD2") (pin "17") (pinfunction "RS_17") (pintype "bidirectional"))
      (node (ref "PCB2") (pin "RESET") (pinfunction "RESET_RESET") (pintype "bidirectional"))
    )
    (net (code "64") (name "SCL") (class "Default")
      (node (ref "U11") (pin "3") (pinfunction "3_3") (pintype "unspecified"))
      (node (ref "U12") (pin "4") (pinfunction "SCL_4") (pintype "unspecified"))
      (node (ref "U13") (pin "3") (pinfunction "SCL_3") (pintype "unspecified"))
      (node (ref "U14") (pin "4") (pinfunction "SCL_4") (pintype "unspecified"))
      (node (ref "U15") (pin "24") (pinfunction "A5_24") (pintype "unspecified"))
      (node (ref "U16") (pin "19") (pinfunction "19/A5/PC5/SCL_19") (pintype "unspecified"))
      (node (ref "U19") (pin "24") (pinfunction "A5_24") (pintype "unspecified"))
      (node (ref "U20") (pin "19") (pinfunction "19/A5/PC5/SCL_19") (pintype "unspecified"))
      (node (ref "U21") (pin "3") (pinfunction "SCL_3") (pintype "unspecified"))
      (node (ref "U22") (pin "2") (pinfunction "SCL_2") (pintype "unspecified"))
      (node (ref "U23") (pin "SCL") (pinfunction "3_SCL") (pintype "unspecified"))
      (node (ref "U27") (pin "19") (pinfunction "19/A5/PC5/SCL_19") (pintype "unspecified"))
      (node (ref "U28") (pin "24") (pinfunction "A5_24") (pintype "unspecified"))
      (node (ref "U29") (pin "3") (pinfunction "SCL_3") (pintype "unspecified"))
    )
    (net (code "65") (name "SDA") (class "Default")
      (node (ref "U11") (pin "4") (pinfunction "4_4") (pintype "unspecified"))
      (node (ref "U12") (pin "3") (pinfunction "SDA_3") (pintype "unspecified"))
      (node (ref "U13") (pin "4") (pinfunction "SDA_4") (pintype "unspecified"))
      (node (ref "U14") (pin "3") (pinfunction "SDA_3") (pintype "unspecified"))
      (node (ref "U15") (pin "23") (pinfunction "A4_23") (pintype "unspecified"))
      (node (ref "U16") (pin "20") (pinfunction "18/A4/PC4/SDA_20") (pintype "unspecified"))
      (node (ref "U19") (pin "23") (pinfunction "A4_23") (pintype "unspecified"))
      (node (ref "U20") (pin "20") (pinfunction "18/A4/PC4/SDA_20") (pintype "unspecified"))
      (node (ref "U21") (pin "4") (pinfunction "SDA_4") (pintype "unspecified"))
      (node (ref "U22") (pin "1") (pinfunction "SDA_1") (pintype "unspecified"))
      (node (ref "U23") (pin "SDA") (pinfunction "4_SDA") (pintype "unspecified"))
      (node (ref "U27") (pin "20") (pinfunction "18/A4/PC4/SDA_20") (pintype "unspecified"))
      (node (ref "U28") (pin "23") (pinfunction "A4_23") (pintype "unspecified"))
      (node (ref "U29") (pin "4") (pinfunction "SDA_4") (pintype "unspecified"))
    )
    (net (code "66") (name "SIG") (class "Default")
      (node (ref "J2") (pin "15") (pinfunction "SIG_15") (pintype "unspecified"))
      (node (ref "NODE5") (pin "20") (pinfunction "D8_20") (pintype "unspecified"))
      (node (ref "P1") (pin "3") (pinfunction "SIG_3") (pintype "input"))
      (node (ref "P2") (pin "3") (pinfunction "SIG_3") (pintype "input"))
      (node (ref "U17") (pin "11") (pinfunction "D8_11") (pintype "unspecified"))
      (node (ref "U18") (pin "9") (pinfunction "PB0/8_9") (pintype "unspecified"))
    )
    (net (code "67") (name "VCC") (class "Default")
      (node (ref "C5") (pin "1") (pinfunction "1_1") (pintype "input"))
      (node (ref "C6") (pin "2") (pinfunction "2_2") (pintype "input"))
      (node (ref "D3") (pin "1") (pinfunction "K_1") (pintype "unspecified"))
      (node (ref "DD1") (pin "1") (pinfunction "VDD_1") (pintype "unspecified"))
      (node (ref "H1") (pin "4") (pinfunction "VCC_4") (pintype "unspecified"))
      (node (ref "J2") (pin "13") (pinfunction "Vcc_13") (pintype "unspecified"))
      (node (ref "LCD2") (pin "19") (pinfunction "VCC_19") (pintype "bidirectional"))
      (node (ref "LCD2") (pin "2") (pinfunction "A_2") (pintype "bidirectional"))
      (node (ref "LCD3") (pin "15") (pinfunction "A_15") (pintype "unspecified"))
      (node (ref "LCD3") (pin "2") (pinfunction "Vdd_2") (pintype "unspecified"))
      (node (ref "LCD4") (pin "15") (pinfunction "BLA_15") (pintype "unspecified"))
      (node (ref "LCD4") (pin "2") (pinfunction "VCC_2") (pintype "unspecified"))
      (node (ref "NODE5") (pin "16") (pinfunction "3V3_16") (pintype "unspecified"))
      (node (ref "P1") (pin "1") (pinfunction "VCC_1") (pintype "input"))
      (node (ref "P2") (pin "2") (pinfunction "VCC_2") (pintype "input"))
      (node (ref "P3") (pin "1") (pinfunction "1_1") (pintype "input"))
      (node (ref "PCB2") (pin "5V") (pinfunction "5V_5V") (pintype "bidirectional"))
      (node (ref "Q5") (pin "3") (pinfunction "E_3") (pintype "unspecified"))
      (node (ref "R7") (pin "2") (pinfunction "2_2") (pintype "unspecified"))
      (node (ref "R8") (pin "2") (pinfunction "2_2") (pintype "unspecified"))
      (node (ref "S1") (pin "1") (pinfunction "VCC_1") (pintype "unspecified"))
      (node (ref "U1") (pin "28") (pinfunction "5V_28") (pintype "passive"))
      (node (ref "U10") (pin "28") (pinfunction "5V_28") (pintype "passive"))
      (node (ref "U11") (pin "1") (pinfunction "1_1") (pintype "unspecified"))
      (node (ref "U12") (pin "5") (pinfunction "VCC_5") (pintype "unspecified"))
      (node (ref "U13") (pin "1") (pinfunction "VCC_1") (pintype "unspecified"))
      (node (ref "U14") (pin "5") (pinfunction "VCC_5") (pintype "unspecified"))
      (node (ref "U15") (pin "27") (pinfunction "+5V_27") (pintype "unspecified"))
      (node (ref "U16") (pin "28") (pinfunction "5V_28") (pintype "passive"))
      (node (ref "U17") (pin "27") (pinfunction "+5V_27") (pintype "unspecified"))
      (node (ref "U18") (pin "28") (pinfunction "5V_28") (pintype "passive"))
      (node (ref "U19") (pin "27") (pinfunction "+5V_27") (pintype "unspecified"))
      (node (ref "U2") (pin "27") (pinfunction "+5V_27") (pintype "unspecified"))
      (node (ref "U20") (pin "28") (pinfunction "5V_28") (pintype "passive"))
      (node (ref "U21") (pin "2") (pinfunction "VCC_2") (pintype "unspecified"))
      (node (ref "U22") (pin "3") (pinfunction "VCC_3") (pintype "unspecified"))
      (node (ref "U23") (pin "VCC") (pinfunction "2_VCC") (pintype "unspecified"))
      (node (ref "U24") (pin "27") (pinfunction "+5V_27") (pintype "unspecified"))
      (node (ref "U26") (pin "2") (pinfunction "2_2") (pintype "unspecified"))
      (node (ref "U27") (pin "28") (pinfunction "5V_28") (pintype "passive"))
      (node (ref "U28") (pin "27") (pinfunction "+5V_27") (pintype "unspecified"))
      (node (ref "U29") (pin "2") (pinfunction "Vcc_2") (pintype "unspecified"))
      (node (ref "U3") (pin "1") (pinfunction "VCC_1") (pintype "unspecified"))
      (node (ref "U4") (pin "2") (pinfunction "VCC_2") (pintype "unspecified"))
      (node (ref "U48") (pin "3") (pinfunction "2_3") (pintype "input"))
      (node (ref "U50") (pin "VCC") (pinfunction "1_VCC") (pintype "unspecified"))
      (node (ref "U51") (pin "28") (pinfunction "5V_28") (pintype "passive"))
      (node (ref "U52") (pin "28") (pinfunction "5V_28") (pintype "passive"))
      (node (ref "U53") (pin "1") (pinfunction "VCC_1") (pintype "unspecified"))
      (node (ref "U53") (pin "7") (pinfunction "SEL_7") (pintype "unspecified"))
      (node (ref "U54") (pin "28") (pinfunction "5V_28") (pintype "passive"))
      (node (ref "U55") (pin "2") (pinfunction "IN_2") (pintype "unspecified"))
      (node (ref "U58") (pin "1") (pinfunction "1_1") (pintype "unspecified"))
      (node (ref "U6") (pin "27") (pinfunction "+5V_27") (pintype "unspecified"))
      (node (ref "U7") (pin "28") (pinfunction "5V_28") (pintype "passive"))
      (node (ref "U8") (pin "2") (pinfunction "VCC_2") (pintype "unspecified"))
      (node (ref "U9") (pin "27") (pinfunction "+5V_27") (pintype "unspecified"))
    )
    (net (code "68") (name "unconnected-(DD1-NC-Pad3)") (class "Default")
      (node (ref "DD1") (pin "3") (pinfunction "NC_3") (pintype "unspecified"))
    )
    (net (code "69") (name "unconnected-(J2-COM-Pad2)") (class "Default")
      (node (ref "J2") (pin "2") (pinfunction "COM_2") (pintype "unspecified"))
    )
    (net (code "70") (name "unconnected-(J2-NC-Pad3)") (class "Default")
      (node (ref "J2") (pin "3") (pinfunction "NC_3") (pintype "unspecified"))
    )
    (net (code "71") (name "unconnected-(J2-NO-Pad1)") (class "Default")
      (node (ref "J2") (pin "1") (pinfunction "NO_1") (pintype "unspecified"))
    )
    (net (code "72") (name "unconnected-(LCD3-DB0-Pad7)") (class "Default")
      (node (ref "LCD3") (pin "7") (pinfunction "DB0_7") (pintype "unspecified"))
    )
    (net (code "73") (name "unconnected-(LCD3-DB1-Pad8)") (class "Default")
      (node (ref "LCD3") (pin "8") (pinfunction "DB1_8") (pintype "unspecified"))
    )
    (net (code "74") (name "unconnected-(LCD3-DB2-Pad9)") (class "Default")
      (node (ref "LCD3") (pin "9") (pinfunction "DB2_9") (pintype "unspecified"))
    )
    (net (code "75") (name "unconnected-(LCD3-DB3-Pad10)") (class "Default")
      (node (ref "LCD3") (pin "10") (pinfunction "DB3_10") (pintype "unspecified"))
    )
    (net (code "76") (name "unconnected-(LCD4-DB0-Pad7)") (class "Default")
      (node (ref "LCD4") (pin "7") (pinfunction "DB0_7") (pintype "unspecified"))
    )
    (net (code "77") (name "unconnected-(LCD4-DB1-Pad8)") (class "Default")
      (node (ref "LCD4") (pin "8") (pinfunction "DB1_8") (pintype "unspecified"))
    )
    (net (code "78") (name "unconnected-(LCD4-DB2-Pad9)") (class "Default")
      (node (ref "LCD4") (pin "9") (pinfunction "DB2_9") (pintype "unspecified"))
    )
    (net (code "79") (name "unconnected-(LCD4-DB3-Pad10)") (class "Default")
      (node (ref "LCD4") (pin "10") (pinfunction "DB3_10") (pintype "unspecified"))
    )
    (net (code "80") (name "unconnected-(NODE5-3V3-Pad11)") (class "Default")
      (node (ref "NODE5") (pin "11") (pinfunction "3V3_11") (pintype "unspecified"))
    )
    (net (code "81") (name "unconnected-(NODE5-3V3-Pad25)") (class "Default")
      (node (ref "NODE5") (pin "25") (pinfunction "3V3_25") (pintype "unspecified"))
    )
    (net (code "82") (name "unconnected-(NODE5-A0-Pad1)") (class "Default")
      (node (ref "NODE5") (pin "1") (pinfunction "A0_1") (pintype "unspecified"))
    )
    (net (code "83") (name "unconnected-(NODE5-D0-Pad30)") (class "Default")
      (node (ref "NODE5") (pin "30") (pinfunction "D0_30") (pintype "unspecified"))
    )
    (net (code "84") (name "unconnected-(NODE5-D1-Pad29)") (class "Default")
      (node (ref "NODE5") (pin "29") (pinfunction "D1_29") (pintype "unspecified"))
    )
    (net (code "85") (name "unconnected-(NODE5-D2-Pad28)") (class "Default")
      (node (ref "NODE5") (pin "28") (pinfunction "D2_28") (pintype "unspecified"))
    )
    (net (code "86") (name "unconnected-(NODE5-D3-Pad27)") (class "Default")
      (node (ref "NODE5") (pin "27") (pinfunction "D3_27") (pintype "unspecified"))
    )
    (net (code "87") (name "unconnected-(NODE5-D4-Pad26)") (class "Default")
      (node (ref "NODE5") (pin "26") (pinfunction "D4_26") (pintype "unspecified"))
    )
    (net (code "88") (name "unconnected-(NODE5-D5-Pad23)") (class "Default")
      (node (ref "NODE5") (pin "23") (pinfunction "D5_23") (pintype "unspecified"))
    )
    (net (code "89") (name "unconnected-(NODE5-D6-Pad22)") (class "Default")
      (node (ref "NODE5") (pin "22") (pinfunction "D6_22") (pintype "unspecified"))
    )
    (net (code "90") (name "unconnected-(NODE5-D7-Pad21)") (class "Default")
      (node (ref "NODE5") (pin "21") (pinfunction "D7_21") (pintype "unspecified"))
    )
    (net (code "91") (name "unconnected-(NODE5-EN-Pad12)") (class "Default")
      (node (ref "NODE5") (pin "12") (pinfunction "EN_12") (pintype "unspecified"))
    )
    (net (code "92") (name "unconnected-(NODE5-GND-Pad2)") (class "Default")
      (node (ref "NODE5") (pin "2") (pinfunction "GND_2") (pintype "unspecified"))
    )
    (net (code "93") (name "unconnected-(NODE5-GND-Pad10)") (class "Default")
      (node (ref "NODE5") (pin "10") (pinfunction "GND_10") (pintype "unspecified"))
    )
    (net (code "94") (name "unconnected-(NODE5-GND-Pad14)") (class "Default")
      (node (ref "NODE5") (pin "14") (pinfunction "GND_14") (pintype "unspecified"))
    )
    (net (code "95") (name "unconnected-(NODE5-GND-Pad24)") (class "Default")
      (node (ref "NODE5") (pin "24") (pinfunction "GND_24") (pintype "unspecified"))
    )
    (net (code "96") (name "unconnected-(NODE5-RST-Pad13)") (class "Default")
      (node (ref "NODE5") (pin "13") (pinfunction "RST_13") (pintype "unspecified"))
    )
    (net (code "97") (name "unconnected-(NODE5-RX-Pad19)") (class "Default")
      (node (ref "NODE5") (pin "19") (pinfunction "RX_19") (pintype "unspecified"))
    )
    (net (code "98") (name "unconnected-(NODE5-S1-Pad6)") (class "Default")
      (node (ref "NODE5") (pin "6") (pinfunction "S1_6") (pintype "unspecified"))
    )
    (net (code "99") (name "unconnected-(NODE5-S2-Pad5)") (class "Default")
      (node (ref "NODE5") (pin "5") (pinfunction "S2_5") (pintype "unspecified"))
    )
    (net (code "100") (name "unconnected-(NODE5-S3-Pad4)") (class "Default")
      (node (ref "NODE5") (pin "4") (pinfunction "S3_4") (pintype "unspecified"))
    )
    (net (code "101") (name "unconnected-(NODE5-SC-Pad7)") (class "Default")
      (node (ref "NODE5") (pin "7") (pinfunction "SC_7") (pintype "unspecified"))
    )
    (net (code "102") (name "unconnected-(NODE5-SK-Pad9)") (class "Default")
      (node (ref "NODE5") (pin "9") (pinfunction "SK_9") (pintype "unspecified"))
    )
    (net (code "103") (name "unconnected-(NODE5-SO-Pad8)") (class "Default")
      (node (ref "NODE5") (pin "8") (pinfunction "SO_8") (pintype "unspecified"))
    )
    (net (code "104") (name "unconnected-(NODE5-TX-Pad18)") (class "Default")
      (node (ref "NODE5") (pin "18") (pinfunction "TX_18") (pintype "unspecified"))
    )
    (net (code "105") (name "unconnected-(NODE5-VU-Pad3)") (class "Default")
      (node (ref "NODE5") (pin "3") (pinfunction "VU_3") (pintype "unspecified"))
    )
    (net (code "106") (name "unconnected-(NODE5-Vin-Pad15)") (class "Default")
      (node (ref "NODE5") (pin "15") (pinfunction "Vin_15") (pintype "unspecified"))
    )
    (net (code "107") (name "unconnected-(PCB1-(N{slash}C)-PadN{slash}C)") (class "Default")
      (node (ref "PCB1") (pin "N/C") (pinfunction "(N/C)_N/C") (pintype "bidirectional"))
    )
    (net (code "108") (name "unconnected-(PCB1-0(RX)-Pad0)") (class "Default")
      (node (ref "PCB1") (pin "0") (pinfunction "0(RX)_0") (pintype "bidirectional"))
    )
    (net (code "109") (name "unconnected-(PCB1-1(TX)-Pad1)") (class "Default")
      (node (ref "PCB1") (pin "1") (pinfunction "1(TX)_1") (pintype "bidirectional"))
    )
    (net (code "110") (name "unconnected-(PCB1-27(SDA)-PadSDA)") (class "Default")
      (node (ref "PCB1") (pin "SDA") (pinfunction "27(SDA)_SDA") (pintype "bidirectional"))
    )
    (net (code "111") (name "unconnected-(PCB1-28(SCL)-PadSCL)") (class "Default")
      (node (ref "PCB1") (pin "SCL") (pinfunction "28(SCL)_SCL") (pintype "bidirectional"))
    )
    (net (code "112") (name "unconnected-(PCB1-DC_JACK_+-PadPWR+)") (class "Default")
      (node (ref "PCB1") (pin "PWR+") (pinfunction "DC_JACK_+_PWR+") (pintype "passive"))
    )
    (net (code "113") (name "unconnected-(PCB1-DC_JACK_--PadPWR-)") (class "Default")
      (node (ref "PCB1") (pin "PWR-") (pinfunction "DC_JACK_-_PWR-") (pintype "passive"))
    )
    (net (code "114") (name "unconnected-(PCB1-IOREF-PadI{slash}OREF)") (class "Default")
      (node (ref "PCB1") (pin "I/OREF") (pinfunction "IOREF_I/OREF") (pintype "bidirectional"))
    )
    (net (code "115") (name "unconnected-(PCB1-Pad2)") (class "Default")
      (node (ref "PCB1") (pin "2") (pinfunction "2_2") (pintype "bidirectional"))
    )
    (net (code "116") (name "unconnected-(PCB1-Pad3)") (class "Default")
      (node (ref "PCB1") (pin "3") (pinfunction "3_3") (pintype "bidirectional"))
    )
    (net (code "117") (name "unconnected-(PCB1-Pad3.3V)") (class "Default")
      (node (ref "PCB1") (pin "3.3V") (pinfunction "3.3V_3.3V") (pintype "bidirectional"))
    )
    (net (code "118") (name "unconnected-(PCB1-Pad12)") (class "Default")
      (node (ref "PCB1") (pin "12") (pinfunction "12_12") (pintype "bidirectional"))
    )
    (net (code "119") (name "unconnected-(PCB1-Pad13)") (class "Default")
      (node (ref "PCB1") (pin "13") (pinfunction "13_13") (pintype "bidirectional"))
    )
    (net (code "120") (name "unconnected-(PCB1-PadA5)") (class "Default")
      (node (ref "PCB1") (pin "A5") (pinfunction "A5_A5") (pintype "bidirectional"))
    )
    (net (code "121") (name "unconnected-(PCB1-PadAREF)") (class "Default")
      (node (ref "PCB1") (pin "AREF") (pinfunction "AREF_AREF") (pintype "bidirectional"))
    )
    (net (code "122") (name "unconnected-(PCB1-PadGND.)") (class "Default")
      (node (ref "PCB1") (pin "GND.") (pinfunction "GND._GND.") (pintype "bidirectional"))
    )
    (net (code "123") (name "unconnected-(PCB1-PadGND..)") (class "Default")
      (node (ref "PCB1") (pin "GND..") (pinfunction "GND.._GND..") (pintype "bidirectional"))
    )
    (net (code "124") (name "unconnected-(PCB1-PadVIN)") (class "Default")
      (node (ref "PCB1") (pin "VIN") (pinfunction "VIN_VIN") (pintype "bidirectional"))
    )
    (net (code "125") (name "unconnected-(PCB2-(N{slash}C)-PadN{slash}C)") (class "Default")
      (node (ref "PCB2") (pin "N/C") (pinfunction "(N/C)_N/C") (pintype "bidirectional"))
    )
    (net (code "126") (name "unconnected-(PCB2-0(RX)-Pad0)") (class "Default")
      (node (ref "PCB2") (pin "0") (pinfunction "0(RX)_0") (pintype "bidirectional"))
    )
    (net (code "127") (name "unconnected-(PCB2-1(TX)-Pad1)") (class "Default")
      (node (ref "PCB2") (pin "1") (pinfunction "1(TX)_1") (pintype "bidirectional"))
    )
    (net (code "128") (name "unconnected-(PCB2-27(SDA)-PadSDA)") (class "Default")
      (node (ref "PCB2") (pin "SDA") (pinfunction "27(SDA)_SDA") (pintype "bidirectional"))
    )
    (net (code "129") (name "unconnected-(PCB2-28(SCL)-PadSCL)") (class "Default")
      (node (ref "PCB2") (pin "SCL") (pinfunction "28(SCL)_SCL") (pintype "bidirectional"))
    )
    (net (code "130") (name "unconnected-(PCB2-DC_JACK_+-PadPWR+)") (class "Default")
      (node (ref "PCB2") (pin "PWR+") (pinfunction "DC_JACK_+_PWR+") (pintype "passive"))
    )
    (net (code "131") (name "unconnected-(PCB2-DC_JACK_--PadPWR-)") (class "Default")
      (node (ref "PCB2") (pin "PWR-") (pinfunction "DC_JACK_-_PWR-") (pintype "passive"))
    )
    (net (code "132") (name "unconnected-(PCB2-IOREF-PadI{slash}OREF)") (class "Default")
      (node (ref "PCB2") (pin "I/OREF") (pinfunction "IOREF_I/OREF") (pintype "bidirectional"))
    )
    (net (code "133") (name "unconnected-(PCB2-Pad2)") (class "Default")
      (node (ref "PCB2") (pin "2") (pinfunction "2_2") (pintype "bidirectional"))
    )
    (net (code "134") (name "unconnected-(PCB2-Pad3)") (class "Default")
      (node (ref "PCB2") (pin "3") (pinfunction "3_3") (pintype "bidirectional"))
    )
    (net (code "135") (name "unconnected-(PCB2-Pad3.3V)") (class "Default")
      (node (ref "PCB2") (pin "3.3V") (pinfunction "3.3V_3.3V") (pintype "bidirectional"))
    )
    (net (code "136") (name "unconnected-(PCB2-Pad12)") (class "Default")
      (node (ref "PCB2") (pin "12") (pinfunction "12_12") (pintype "bidirectional"))
    )
    (net (code "137") (name "unconnected-(PCB2-Pad13)") (class "Default")
      (node (ref "PCB2") (pin "13") (pinfunction "13_13") (pintype "bidirectional"))
    )
    (net (code "138") (name "unconnected-(PCB2-PadA5)") (class "Default")
      (node (ref "PCB2") (pin "A5") (pinfunction "A5_A5") (pintype "bidirectional"))
    )
    (net (code "139") (name "unconnected-(PCB2-PadAREF)") (class "Default")
      (node (ref "PCB2") (pin "AREF") (pinfunction "AREF_AREF") (pintype "bidirectional"))
    )
    (net (code "140") (name "unconnected-(PCB2-PadGND)") (class "Default")
      (node (ref "PCB2") (pin "GND") (pinfunction "GND_GND") (pintype "bidirectional"))
    )
    (net (code "141") (name "unconnected-(PCB2-PadGND.)") (class "Default")
      (node (ref "PCB2") (pin "GND.") (pinfunction "GND._GND.") (pintype "bidirectional"))
    )
    (net (code "142") (name "unconnected-(PCB2-PadVIN)") (class "Default")
      (node (ref "PCB2") (pin "VIN") (pinfunction "VIN_VIN") (pintype "bidirectional"))
    )
    (net (code "143") (name "unconnected-(S1-S+-Pad5)") (class "Default")
      (node (ref "S1") (pin "5") (pinfunction "S+_5") (pintype "unspecified"))
    )
    (net (code "144") (name "unconnected-(S1-S--Pad6)") (class "Default")
      (node (ref "S1") (pin "6") (pinfunction "S-_6") (pintype "unspecified"))
    )
    (net (code "145") (name "unconnected-(U1-3V-Pad29)") (class "Default")
      (node (ref "U1") (pin "29") (pinfunction "3V_29") (pintype "passive"))
    )
    (net (code "146") (name "unconnected-(U1-14{slash}A0{slash}PC0-Pad24)") (class "Default")
      (node (ref "U1") (pin "24") (pinfunction "14/A0/PC0_24") (pintype "unspecified"))
    )
    (net (code "147") (name "unconnected-(U1-15{slash}A1{slash}PC1-Pad23)") (class "Default")
      (node (ref "U1") (pin "23") (pinfunction "15/A1/PC1_23") (pintype "unspecified"))
    )
    (net (code "148") (name "unconnected-(U1-16{slash}A2{slash}PC2-Pad22)") (class "Default")
      (node (ref "U1") (pin "22") (pinfunction "16/A2/PC2_22") (pintype "unspecified"))
    )
    (net (code "149") (name "unconnected-(U1-17{slash}A3{slash}PC3-Pad21)") (class "Default")
      (node (ref "U1") (pin "21") (pinfunction "17/A3/PC3_21") (pintype "unspecified"))
    )
    (net (code "150") (name "unconnected-(U1-18{slash}A4{slash}PC4{slash}SDA-Pad20)") (class "Default")
      (node (ref "U1") (pin "20") (pinfunction "18/A4/PC4/SDA_20") (pintype "unspecified"))
    )
    (net (code "151") (name "unconnected-(U1-19{slash}A5{slash}PC5{slash}SCL-Pad19)") (class "Default")
      (node (ref "U1") (pin "19") (pinfunction "19/A5/PC5/SCL_19") (pintype "unspecified"))
    )
    (net (code "152") (name "unconnected-(U1-AREF-Pad16)") (class "Default")
      (node (ref "U1") (pin "16") (pinfunction "AREF_16") (pintype "unspecified"))
    )
    (net (code "153") (name "unconnected-(U1-GND-Pad15)") (class "Default")
      (node (ref "U1") (pin "15") (pinfunction "GND_15") (pintype "passive"))
    )
    (net (code "154") (name "unconnected-(U1-GND2-Pad27)") (class "Default")
      (node (ref "U1") (pin "27") (pinfunction "GND2_27") (pintype "passive"))
    )
    (net (code "155") (name "unconnected-(U1-INT0{slash}PD2{slash}2-Pad3)") (class "Default")
      (node (ref "U1") (pin "3") (pinfunction "INT0/PD2/2_3") (pintype "unspecified"))
    )
    (net (code "156") (name "unconnected-(U1-INT1{slash}PWR{slash}PD3{slash}3-Pad4)") (class "Default")
      (node (ref "U1") (pin "4") (pinfunction "INT1/PWR/PD3/3_4") (pintype "unspecified"))
    )
    (net (code "157") (name "unconnected-(U1-IOREF-Pad31)") (class "Default")
      (node (ref "U1") (pin "31") (pinfunction "IOREF_31") (pintype "unspecified"))
    )
    (net (code "158") (name "unconnected-(U1-MISO{slash}PB4{slash}12-Pad13)") (class "Default")
      (node (ref "U1") (pin "13") (pinfunction "MISO/PB4/12_13") (pintype "unspecified"))
    )
    (net (code "159") (name "unconnected-(U1-MOSI{slash}PWR{slash}PB3{slash}11-Pad12)") (class "Default")
      (node (ref "U1") (pin "12") (pinfunction "MOSI/PWR/PB3/11_12") (pintype "unspecified"))
    )
    (net (code "160") (name "unconnected-(U1-NC-Pad32)") (class "Default")
      (node (ref "U1") (pin "32") (pinfunction "NC_32") (pintype "unspecified"))
    )
    (net (code "161") (name "unconnected-(U1-PB0{slash}8-Pad9)") (class "Default")
      (node (ref "U1") (pin "9") (pinfunction "PB0/8_9") (pintype "unspecified"))
    )
    (net (code "162") (name "unconnected-(U1-PD4{slash}4-Pad5)") (class "Default")
      (node (ref "U1") (pin "5") (pinfunction "PD4/4_5") (pintype "unspecified"))
    )
    (net (code "163") (name "unconnected-(U1-PD7{slash}7-Pad8)") (class "Default")
      (node (ref "U1") (pin "8") (pinfunction "PD7/7_8") (pintype "unspecified"))
    )
    (net (code "164") (name "unconnected-(U1-PWR{slash}PB1{slash}9-Pad10)") (class "Default")
      (node (ref "U1") (pin "10") (pinfunction "PWR/PB1/9_10") (pintype "unspecified"))
    )
    (net (code "165") (name "unconnected-(U1-PWR{slash}PD5{slash}5-Pad6)") (class "Default")
      (node (ref "U1") (pin "6") (pinfunction "PWR/PD5/5_6") (pintype "unspecified"))
    )
    (net (code "166") (name "unconnected-(U1-RESET-Pad30)") (class "Default")
      (node (ref "U1") (pin "30") (pinfunction "RESET_30") (pintype "unspecified"))
    )
    (net (code "167") (name "unconnected-(U1-RX{slash}PD0{slash}0-Pad1)") (class "Default")
      (node (ref "U1") (pin "1") (pinfunction "RX/PD0/0_1") (pintype "unspecified"))
    )
    (net (code "168") (name "unconnected-(U1-SCK{slash}PB5{slash}13-Pad14)") (class "Default")
      (node (ref "U1") (pin "14") (pinfunction "SCK/PB5/13_14") (pintype "unspecified"))
    )
    (net (code "169") (name "unconnected-(U1-SCL-Pad18)") (class "Default")
      (node (ref "U1") (pin "18") (pinfunction "SCL_18") (pintype "unspecified"))
    )
    (net (code "170") (name "unconnected-(U1-SDA-Pad17)") (class "Default")
      (node (ref "U1") (pin "17") (pinfunction "SDA_17") (pintype "unspecified"))
    )
    (net (code "171") (name "unconnected-(U1-SS{slash}PWR{slash}PB2{slash}10-Pad11)") (class "Default")
      (node (ref "U1") (pin "11") (pinfunction "SS/PWR/PB2/10_11") (pintype "unspecified"))
    )
    (net (code "172") (name "unconnected-(U1-TX{slash}PD1{slash}1-Pad2)") (class "Default")
      (node (ref "U1") (pin "2") (pinfunction "TX/PD1/1_2") (pintype "unspecified"))
    )
    (net (code "173") (name "unconnected-(U1-VIN-Pad25)") (class "Default")
      (node (ref "U1") (pin "25") (pinfunction "VIN_25") (pintype "passive"))
    )
    (net (code "174") (name "unconnected-(U2-3V3-Pad17)") (class "Default")
      (node (ref "U2") (pin "17") (pinfunction "3V3_17") (pintype "unspecified"))
    )
    (net (code "175") (name "unconnected-(U2-A0-Pad19)") (class "Default")
      (node (ref "U2") (pin "19") (pinfunction "A0_19") (pintype "unspecified"))
    )
    (net (code "176") (name "unconnected-(U2-A1-Pad20)") (class "Default")
      (node (ref "U2") (pin "20") (pinfunction "A1_20") (pintype "unspecified"))
    )
    (net (code "177") (name "unconnected-(U2-A2-Pad21)") (class "Default")
      (node (ref "U2") (pin "21") (pinfunction "A2_21") (pintype "unspecified"))
    )
    (net (code "178") (name "unconnected-(U2-A3-Pad22)") (class "Default")
      (node (ref "U2") (pin "22") (pinfunction "A3_22") (pintype "unspecified"))
    )
    (net (code "179") (name "unconnected-(U2-A4-Pad23)") (class "Default")
      (node (ref "U2") (pin "23") (pinfunction "A4_23") (pintype "unspecified"))
    )
    (net (code "180") (name "unconnected-(U2-A5-Pad24)") (class "Default")
      (node (ref "U2") (pin "24") (pinfunction "A5_24") (pintype "unspecified"))
    )
    (net (code "181") (name "unconnected-(U2-A6-Pad25)") (class "Default")
      (node (ref "U2") (pin "25") (pinfunction "A6_25") (pintype "unspecified"))
    )
    (net (code "182") (name "unconnected-(U2-A7-Pad26)") (class "Default")
      (node (ref "U2") (pin "26") (pinfunction "A7_26") (pintype "unspecified"))
    )
    (net (code "183") (name "unconnected-(U2-AREF-Pad18)") (class "Default")
      (node (ref "U2") (pin "18") (pinfunction "AREF_18") (pintype "unspecified"))
    )
    (net (code "184") (name "unconnected-(U2-D0{slash}RX-Pad2)") (class "Default")
      (node (ref "U2") (pin "2") (pinfunction "D0/RX_2") (pintype "unspecified"))
    )
    (net (code "185") (name "unconnected-(U2-D1{slash}TX-Pad1)") (class "Default")
      (node (ref "U2") (pin "1") (pinfunction "D1/TX_1") (pintype "unspecified"))
    )
    (net (code "186") (name "unconnected-(U2-D2-Pad5)") (class "Default")
      (node (ref "U2") (pin "5") (pinfunction "D2_5") (pintype "unspecified"))
    )
    (net (code "187") (name "unconnected-(U2-D4-Pad7)") (class "Default")
      (node (ref "U2") (pin "7") (pinfunction "D4_7") (pintype "unspecified"))
    )
    (net (code "188") (name "unconnected-(U2-D5-Pad8)") (class "Default")
      (node (ref "U2") (pin "8") (pinfunction "D5_8") (pintype "unspecified"))
    )
    (net (code "189") (name "unconnected-(U2-D6-Pad9)") (class "Default")
      (node (ref "U2") (pin "9") (pinfunction "D6_9") (pintype "unspecified"))
    )
    (net (code "190") (name "unconnected-(U2-D7-Pad10)") (class "Default")
      (node (ref "U2") (pin "10") (pinfunction "D7_10") (pintype "unspecified"))
    )
    (net (code "191") (name "unconnected-(U2-D8-Pad11)") (class "Default")
      (node (ref "U2") (pin "11") (pinfunction "D8_11") (pintype "unspecified"))
    )
    (net (code "192") (name "unconnected-(U2-D9-Pad12)") (class "Default")
      (node (ref "U2") (pin "12") (pinfunction "D9_12") (pintype "unspecified"))
    )
    (net (code "193") (name "unconnected-(U2-D10-Pad13)") (class "Default")
      (node (ref "U2") (pin "13") (pinfunction "D10_13") (pintype "unspecified"))
    )
    (net (code "194") (name "unconnected-(U2-D11-Pad14)") (class "Default")
      (node (ref "U2") (pin "14") (pinfunction "D11_14") (pintype "unspecified"))
    )
    (net (code "195") (name "unconnected-(U2-D12-Pad15)") (class "Default")
      (node (ref "U2") (pin "15") (pinfunction "D12_15") (pintype "unspecified"))
    )
    (net (code "196") (name "unconnected-(U2-D13-Pad16)") (class "Default")
      (node (ref "U2") (pin "16") (pinfunction "D13_16") (pintype "unspecified"))
    )
    (net (code "197") (name "unconnected-(U2-GND-Pad29)") (class "Default")
      (node (ref "U2") (pin "29") (pinfunction "GND_29") (pintype "unspecified"))
    )
    (net (code "198") (name "unconnected-(U2-RESET-Pad3)") (class "Default")
      (node (ref "U2") (pin "3") (pinfunction "RESET_3") (pintype "unspecified"))
    )
    (net (code "199") (name "unconnected-(U2-RESET-Pad28)") (class "Default")
      (node (ref "U2") (pin "28") (pinfunction "RESET_28") (pintype "unspecified"))
    )
    (net (code "200") (name "unconnected-(U2-VIN-Pad30)") (class "Default")
      (node (ref "U2") (pin "30") (pinfunction "VIN_30") (pintype "unspecified"))
    )
    (net (code "201") (name "unconnected-(U5-AOUT-Pad3)") (class "Default")
      (node (ref "U5") (pin "3") (pinfunction "AOUT_3") (pintype "unspecified"))
    )
    (net (code "202") (name "unconnected-(U5-GND-Pad1)") (class "Default")
      (node (ref "U5") (pin "1") (pinfunction "GND_1") (pintype "unspecified"))
    )
    (net (code "203") (name "unconnected-(U5-VCC-Pad2)") (class "Default")
      (node (ref "U5") (pin "2") (pinfunction "VCC_2") (pintype "unspecified"))
    )
    (net (code "204") (name "unconnected-(U6-3V3-Pad17)") (class "Default")
      (node (ref "U6") (pin "17") (pinfunction "3V3_17") (pintype "unspecified"))
    )
    (net (code "205") (name "unconnected-(U6-A1-Pad20)") (class "Default")
      (node (ref "U6") (pin "20") (pinfunction "A1_20") (pintype "unspecified"))
    )
    (net (code "206") (name "unconnected-(U6-A2-Pad21)") (class "Default")
      (node (ref "U6") (pin "21") (pinfunction "A2_21") (pintype "unspecified"))
    )
    (net (code "207") (name "unconnected-(U6-A3-Pad22)") (class "Default")
      (node (ref "U6") (pin "22") (pinfunction "A3_22") (pintype "unspecified"))
    )
    (net (code "208") (name "unconnected-(U6-A4-Pad23)") (class "Default")
      (node (ref "U6") (pin "23") (pinfunction "A4_23") (pintype "unspecified"))
    )
    (net (code "209") (name "unconnected-(U6-A5-Pad24)") (class "Default")
      (node (ref "U6") (pin "24") (pinfunction "A5_24") (pintype "unspecified"))
    )
    (net (code "210") (name "unconnected-(U6-A6-Pad25)") (class "Default")
      (node (ref "U6") (pin "25") (pinfunction "A6_25") (pintype "unspecified"))
    )
    (net (code "211") (name "unconnected-(U6-A7-Pad26)") (class "Default")
      (node (ref "U6") (pin "26") (pinfunction "A7_26") (pintype "unspecified"))
    )
    (net (code "212") (name "unconnected-(U6-AREF-Pad18)") (class "Default")
      (node (ref "U6") (pin "18") (pinfunction "AREF_18") (pintype "unspecified"))
    )
    (net (code "213") (name "unconnected-(U6-D0{slash}RX-Pad2)") (class "Default")
      (node (ref "U6") (pin "2") (pinfunction "D0/RX_2") (pintype "unspecified"))
    )
    (net (code "214") (name "unconnected-(U6-D1{slash}TX-Pad1)") (class "Default")
      (node (ref "U6") (pin "1") (pinfunction "D1/TX_1") (pintype "unspecified"))
    )
    (net (code "215") (name "unconnected-(U6-D2-Pad5)") (class "Default")
      (node (ref "U6") (pin "5") (pinfunction "D2_5") (pintype "unspecified"))
    )
    (net (code "216") (name "unconnected-(U6-D3-Pad6)") (class "Default")
      (node (ref "U6") (pin "6") (pinfunction "D3_6") (pintype "unspecified"))
    )
    (net (code "217") (name "unconnected-(U6-D4-Pad7)") (class "Default")
      (node (ref "U6") (pin "7") (pinfunction "D4_7") (pintype "unspecified"))
    )
    (net (code "218") (name "unconnected-(U6-D5-Pad8)") (class "Default")
      (node (ref "U6") (pin "8") (pinfunction "D5_8") (pintype "unspecified"))
    )
    (net (code "219") (name "unconnected-(U6-D6-Pad9)") (class "Default")
      (node (ref "U6") (pin "9") (pinfunction "D6_9") (pintype "unspecified"))
    )
    (net (code "220") (name "unconnected-(U6-D7-Pad10)") (class "Default")
      (node (ref "U6") (pin "10") (pinfunction "D7_10") (pintype "unspecified"))
    )
    (net (code "221") (name "unconnected-(U6-D8-Pad11)") (class "Default")
      (node (ref "U6") (pin "11") (pinfunction "D8_11") (pintype "unspecified"))
    )
    (net (code "222") (name "unconnected-(U6-D9-Pad12)") (class "Default")
      (node (ref "U6") (pin "12") (pinfunction "D9_12") (pintype "unspecified"))
    )
    (net (code "223") (name "unconnected-(U6-D10-Pad13)") (class "Default")
      (node (ref "U6") (pin "13") (pinfunction "D10_13") (pintype "unspecified"))
    )
    (net (code "224") (name "unconnected-(U6-D11-Pad14)") (class "Default")
      (node (ref "U6") (pin "14") (pinfunction "D11_14") (pintype "unspecified"))
    )
    (net (code "225") (name "unconnected-(U6-D12-Pad15)") (class "Default")
      (node (ref "U6") (pin "15") (pinfunction "D12_15") (pintype "unspecified"))
    )
    (net (code "226") (name "unconnected-(U6-D13-Pad16)") (class "Default")
      (node (ref "U6") (pin "16") (pinfunction "D13_16") (pintype "unspecified"))
    )
    (net (code "227") (name "unconnected-(U6-GND-Pad29)") (class "Default")
      (node (ref "U6") (pin "29") (pinfunction "GND_29") (pintype "unspecified"))
    )
    (net (code "228") (name "unconnected-(U6-RESET-Pad3)") (class "Default")
      (node (ref "U6") (pin "3") (pinfunction "RESET_3") (pintype "unspecified"))
    )
    (net (code "229") (name "unconnected-(U6-RESET-Pad28)") (class "Default")
      (node (ref "U6") (pin "28") (pinfunction "RESET_28") (pintype "unspecified"))
    )
    (net (code "230") (name "unconnected-(U6-VIN-Pad30)") (class "Default")
      (node (ref "U6") (pin "30") (pinfunction "VIN_30") (pintype "unspecified"))
    )
    (net (code "231") (name "unconnected-(U7-3V-Pad29)") (class "Default")
      (node (ref "U7") (pin "29") (pinfunction "3V_29") (pintype "passive"))
    )
    (net (code "232") (name "unconnected-(U7-15{slash}A1{slash}PC1-Pad23)") (class "Default")
      (node (ref "U7") (pin "23") (pinfunction "15/A1/PC1_23") (pintype "unspecified"))
    )
    (net (code "233") (name "unconnected-(U7-16{slash}A2{slash}PC2-Pad22)") (class "Default")
      (node (ref "U7") (pin "22") (pinfunction "16/A2/PC2_22") (pintype "unspecified"))
    )
    (net (code "234") (name "unconnected-(U7-17{slash}A3{slash}PC3-Pad21)") (class "Default")
      (node (ref "U7") (pin "21") (pinfunction "17/A3/PC3_21") (pintype "unspecified"))
    )
    (net (code "235") (name "unconnected-(U7-18{slash}A4{slash}PC4{slash}SDA-Pad20)") (class "Default")
      (node (ref "U7") (pin "20") (pinfunction "18/A4/PC4/SDA_20") (pintype "unspecified"))
    )
    (net (code "236") (name "unconnected-(U7-19{slash}A5{slash}PC5{slash}SCL-Pad19)") (class "Default")
      (node (ref "U7") (pin "19") (pinfunction "19/A5/PC5/SCL_19") (pintype "unspecified"))
    )
    (net (code "237") (name "unconnected-(U7-AREF-Pad16)") (class "Default")
      (node (ref "U7") (pin "16") (pinfunction "AREF_16") (pintype "unspecified"))
    )
    (net (code "238") (name "unconnected-(U7-GND-Pad15)") (class "Default")
      (node (ref "U7") (pin "15") (pinfunction "GND_15") (pintype "passive"))
    )
    (net (code "239") (name "unconnected-(U7-GND2-Pad27)") (class "Default")
      (node (ref "U7") (pin "27") (pinfunction "GND2_27") (pintype "passive"))
    )
    (net (code "240") (name "unconnected-(U7-INT0{slash}PD2{slash}2-Pad3)") (class "Default")
      (node (ref "U7") (pin "3") (pinfunction "INT0/PD2/2_3") (pintype "unspecified"))
    )
    (net (code "241") (name "unconnected-(U7-INT1{slash}PWR{slash}PD3{slash}3-Pad4)") (class "Default")
      (node (ref "U7") (pin "4") (pinfunction "INT1/PWR/PD3/3_4") (pintype "unspecified"))
    )
    (net (code "242") (name "unconnected-(U7-IOREF-Pad31)") (class "Default")
      (node (ref "U7") (pin "31") (pinfunction "IOREF_31") (pintype "unspecified"))
    )
    (net (code "243") (name "unconnected-(U7-MISO{slash}PB4{slash}12-Pad13)") (class "Default")
      (node (ref "U7") (pin "13") (pinfunction "MISO/PB4/12_13") (pintype "unspecified"))
    )
    (net (code "244") (name "unconnected-(U7-MOSI{slash}PWR{slash}PB3{slash}11-Pad12)") (class "Default")
      (node (ref "U7") (pin "12") (pinfunction "MOSI/PWR/PB3/11_12") (pintype "unspecified"))
    )
    (net (code "245") (name "unconnected-(U7-NC-Pad32)") (class "Default")
      (node (ref "U7") (pin "32") (pinfunction "NC_32") (pintype "unspecified"))
    )
    (net (code "246") (name "unconnected-(U7-PB0{slash}8-Pad9)") (class "Default")
      (node (ref "U7") (pin "9") (pinfunction "PB0/8_9") (pintype "unspecified"))
    )
    (net (code "247") (name "unconnected-(U7-PD4{slash}4-Pad5)") (class "Default")
      (node (ref "U7") (pin "5") (pinfunction "PD4/4_5") (pintype "unspecified"))
    )
    (net (code "248") (name "unconnected-(U7-PD7{slash}7-Pad8)") (class "Default")
      (node (ref "U7") (pin "8") (pinfunction "PD7/7_8") (pintype "unspecified"))
    )
    (net (code "249") (name "unconnected-(U7-PWR{slash}PB1{slash}9-Pad10)") (class "Default")
      (node (ref "U7") (pin "10") (pinfunction "PWR/PB1/9_10") (pintype "unspecified"))
    )
    (net (code "250") (name "unconnected-(U7-PWR{slash}PD5{slash}5-Pad6)") (class "Default")
      (node (ref "U7") (pin "6") (pinfunction "PWR/PD5/5_6") (pintype "unspecified"))
    )
    (net (code "251") (name "unconnected-(U7-PWR{slash}PD6{slash}6-Pad7)") (class "Default")
      (node (ref "U7") (pin "7") (pinfunction "PWR/PD6/6_7") (pintype "unspecified"))
    )
    (net (code "252") (name "unconnected-(U7-RESET-Pad30)") (class "Default")
      (node (ref "U7") (pin "30") (pinfunction "RESET_30") (pintype "unspecified"))
    )
    (net (code "253") (name "unconnected-(U7-RX{slash}PD0{slash}0-Pad1)") (class "Default")
      (node (ref "U7") (pin "1") (pinfunction "RX/PD0/0_1") (pintype "unspecified"))
    )
    (net (code "254") (name "unconnected-(U7-SCK{slash}PB5{slash}13-Pad14)") (class "Default")
      (node (ref "U7") (pin "14") (pinfunction "SCK/PB5/13_14") (pintype "unspecified"))
    )
    (net (code "255") (name "unconnected-(U7-SCL-Pad18)") (class "Default")
      (node (ref "U7") (pin "18") (pinfunction "SCL_18") (pintype "unspecified"))
    )
    (net (code "256") (name "unconnected-(U7-SDA-Pad17)") (class "Default")
      (node (ref "U7") (pin "17") (pinfunction "SDA_17") (pintype "unspecified"))
    )
    (net (code "257") (name "unconnected-(U7-SS{slash}PWR{slash}PB2{slash}10-Pad11)") (class "Default")
      (node (ref "U7") (pin "11") (pinfunction "SS/PWR/PB2/10_11") (pintype "unspecified"))
    )
    (net (code "258") (name "unconnected-(U7-TX{slash}PD1{slash}1-Pad2)") (class "Default")
      (node (ref "U7") (pin "2") (pinfunction "TX/PD1/1_2") (pintype "unspecified"))
    )
    (net (code "259") (name "unconnected-(U7-VIN-Pad25)") (class "Default")
      (node (ref "U7") (pin "25") (pinfunction "VIN_25") (pintype "passive"))
    )
    (net (code "260") (name "unconnected-(U9-3V3-Pad17)") (class "Default")
      (node (ref "U9") (pin "17") (pinfunction "3V3_17") (pintype "unspecified"))
    )
    (net (code "261") (name "unconnected-(U9-A1-Pad20)") (class "Default")
      (node (ref "U9") (pin "20") (pinfunction "A1_20") (pintype "unspecified"))
    )
    (net (code "262") (name "unconnected-(U9-A2-Pad21)") (class "Default")
      (node (ref "U9") (pin "21") (pinfunction "A2_21") (pintype "unspecified"))
    )
    (net (code "263") (name "unconnected-(U9-A3-Pad22)") (class "Default")
      (node (ref "U9") (pin "22") (pinfunction "A3_22") (pintype "unspecified"))
    )
    (net (code "264") (name "unconnected-(U9-A4-Pad23)") (class "Default")
      (node (ref "U9") (pin "23") (pinfunction "A4_23") (pintype "unspecified"))
    )
    (net (code "265") (name "unconnected-(U9-A5-Pad24)") (class "Default")
      (node (ref "U9") (pin "24") (pinfunction "A5_24") (pintype "unspecified"))
    )
    (net (code "266") (name "unconnected-(U9-A6-Pad25)") (class "Default")
      (node (ref "U9") (pin "25") (pinfunction "A6_25") (pintype "unspecified"))
    )
    (net (code "267") (name "unconnected-(U9-A7-Pad26)") (class "Default")
      (node (ref "U9") (pin "26") (pinfunction "A7_26") (pintype "unspecified"))
    )
    (net (code "268") (name "unconnected-(U9-AREF-Pad18)") (class "Default")
      (node (ref "U9") (pin "18") (pinfunction "AREF_18") (pintype "unspecified"))
    )
    (net (code "269") (name "unconnected-(U9-D0{slash}RX-Pad2)") (class "Default")
      (node (ref "U9") (pin "2") (pinfunction "D0/RX_2") (pintype "unspecified"))
    )
    (net (code "270") (name "unconnected-(U9-D1{slash}TX-Pad1)") (class "Default")
      (node (ref "U9") (pin "1") (pinfunction "D1/TX_1") (pintype "unspecified"))
    )
    (net (code "271") (name "unconnected-(U9-D2-Pad5)") (class "Default")
      (node (ref "U9") (pin "5") (pinfunction "D2_5") (pintype "unspecified"))
    )
    (net (code "272") (name "unconnected-(U9-D3-Pad6)") (class "Default")
      (node (ref "U9") (pin "6") (pinfunction "D3_6") (pintype "unspecified"))
    )
    (net (code "273") (name "unconnected-(U9-D4-Pad7)") (class "Default")
      (node (ref "U9") (pin "7") (pinfunction "D4_7") (pintype "unspecified"))
    )
    (net (code "274") (name "unconnected-(U9-D5-Pad8)") (class "Default")
      (node (ref "U9") (pin "8") (pinfunction "D5_8") (pintype "unspecified"))
    )
    (net (code "275") (name "unconnected-(U9-D6-Pad9)") (class "Default")
      (node (ref "U9") (pin "9") (pinfunction "D6_9") (pintype "unspecified"))
    )
    (net (code "276") (name "unconnected-(U9-D7-Pad10)") (class "Default")
      (node (ref "U9") (pin "10") (pinfunction "D7_10") (pintype "unspecified"))
    )
    (net (code "277") (name "unconnected-(U9-D9-Pad12)") (class "Default")
      (node (ref "U9") (pin "12") (pinfunction "D9_12") (pintype "unspecified"))
    )
    (net (code "278") (name "unconnected-(U9-D10-Pad13)") (class "Default")
      (node (ref "U9") (pin "13") (pinfunction "D10_13") (pintype "unspecified"))
    )
    (net (code "279") (name "unconnected-(U9-D11-Pad14)") (class "Default")
      (node (ref "U9") (pin "14") (pinfunction "D11_14") (pintype "unspecified"))
    )
    (net (code "280") (name "unconnected-(U9-D12-Pad15)") (class "Default")
      (node (ref "U9") (pin "15") (pinfunction "D12_15") (pintype "unspecified"))
    )
    (net (code "281") (name "unconnected-(U9-D13-Pad16)") (class "Default")
      (node (ref "U9") (pin "16") (pinfunction "D13_16") (pintype "unspecified"))
    )
    (net (code "282") (name "unconnected-(U9-GND-Pad29)") (class "Default")
      (node (ref "U9") (pin "29") (pinfunction "GND_29") (pintype "unspecified"))
    )
    (net (code "283") (name "unconnected-(U9-RESET-Pad3)") (class "Default")
      (node (ref "U9") (pin "3") (pinfunction "RESET_3") (pintype "unspecified"))
    )
    (net (code "284") (name "unconnected-(U9-RESET-Pad28)") (class "Default")
      (node (ref "U9") (pin "28") (pinfunction "RESET_28") (pintype "unspecified"))
    )
    (net (code "285") (name "unconnected-(U9-VIN-Pad30)") (class "Default")
      (node (ref "U9") (pin "30") (pinfunction "VIN_30") (pintype "unspecified"))
    )
    (net (code "286") (name "unconnected-(U10-3V-Pad29)") (class "Default")
      (node (ref "U10") (pin "29") (pinfunction "3V_29") (pintype "passive"))
    )
    (net (code "287") (name "unconnected-(U10-15{slash}A1{slash}PC1-Pad23)") (class "Default")
      (node (ref "U10") (pin "23") (pinfunction "15/A1/PC1_23") (pintype "unspecified"))
    )
    (net (code "288") (name "unconnected-(U10-16{slash}A2{slash}PC2-Pad22)") (class "Default")
      (node (ref "U10") (pin "22") (pinfunction "16/A2/PC2_22") (pintype "unspecified"))
    )
    (net (code "289") (name "unconnected-(U10-17{slash}A3{slash}PC3-Pad21)") (class "Default")
      (node (ref "U10") (pin "21") (pinfunction "17/A3/PC3_21") (pintype "unspecified"))
    )
    (net (code "290") (name "unconnected-(U10-18{slash}A4{slash}PC4{slash}SDA-Pad20)") (class "Default")
      (node (ref "U10") (pin "20") (pinfunction "18/A4/PC4/SDA_20") (pintype "unspecified"))
    )
    (net (code "291") (name "unconnected-(U10-19{slash}A5{slash}PC5{slash}SCL-Pad19)") (class "Default")
      (node (ref "U10") (pin "19") (pinfunction "19/A5/PC5/SCL_19") (pintype "unspecified"))
    )
    (net (code "292") (name "unconnected-(U10-AREF-Pad16)") (class "Default")
      (node (ref "U10") (pin "16") (pinfunction "AREF_16") (pintype "unspecified"))
    )
    (net (code "293") (name "unconnected-(U10-GND-Pad15)") (class "Default")
      (node (ref "U10") (pin "15") (pinfunction "GND_15") (pintype "passive"))
    )
    (net (code "294") (name "unconnected-(U10-GND2-Pad27)") (class "Default")
      (node (ref "U10") (pin "27") (pinfunction "GND2_27") (pintype "passive"))
    )
    (net (code "295") (name "unconnected-(U10-INT0{slash}PD2{slash}2-Pad3)") (class "Default")
      (node (ref "U10") (pin "3") (pinfunction "INT0/PD2/2_3") (pintype "unspecified"))
    )
    (net (code "296") (name "unconnected-(U10-INT1{slash}PWR{slash}PD3{slash}3-Pad4)") (class "Default")
      (node (ref "U10") (pin "4") (pinfunction "INT1/PWR/PD3/3_4") (pintype "unspecified"))
    )
    (net (code "297") (name "unconnected-(U10-IOREF-Pad31)") (class "Default")
      (node (ref "U10") (pin "31") (pinfunction "IOREF_31") (pintype "unspecified"))
    )
    (net (code "298") (name "unconnected-(U10-MISO{slash}PB4{slash}12-Pad13)") (class "Default")
      (node (ref "U10") (pin "13") (pinfunction "MISO/PB4/12_13") (pintype "unspecified"))
    )
    (net (code "299") (name "unconnected-(U10-MOSI{slash}PWR{slash}PB3{slash}11-Pad12)") (class "Default")
      (node (ref "U10") (pin "12") (pinfunction "MOSI/PWR/PB3/11_12") (pintype "unspecified"))
    )
    (net (code "300") (name "unconnected-(U10-NC-Pad32)") (class "Default")
      (node (ref "U10") (pin "32") (pinfunction "NC_32") (pintype "unspecified"))
    )
    (net (code "301") (name "unconnected-(U10-PD4{slash}4-Pad5)") (class "Default")
      (node (ref "U10") (pin "5") (pinfunction "PD4/4_5") (pintype "unspecified"))
    )
    (net (code "302") (name "unconnected-(U10-PD7{slash}7-Pad8)") (class "Default")
      (node (ref "U10") (pin "8") (pinfunction "PD7/7_8") (pintype "unspecified"))
    )
    (net (code "303") (name "unconnected-(U10-PWR{slash}PB1{slash}9-Pad10)") (class "Default")
      (node (ref "U10") (pin "10") (pinfunction "PWR/PB1/9_10") (pintype "unspecified"))
    )
    (net (code "304") (name "unconnected-(U10-PWR{slash}PD5{slash}5-Pad6)") (class "Default")
      (node (ref "U10") (pin "6") (pinfunction "PWR/PD5/5_6") (pintype "unspecified"))
    )
    (net (code "305") (name "unconnected-(U10-PWR{slash}PD6{slash}6-Pad7)") (class "Default")
      (node (ref "U10") (pin "7") (pinfunction "PWR/PD6/6_7") (pintype "unspecified"))
    )
    (net (code "306") (name "unconnected-(U10-RESET-Pad30)") (class "Default")
      (node (ref "U10") (pin "30") (pinfunction "RESET_30") (pintype "unspecified"))
    )
    (net (code "307") (name "unconnected-(U10-RX{slash}PD0{slash}0-Pad1)") (class "Default")
      (node (ref "U10") (pin "1") (pinfunction "RX/PD0/0_1") (pintype "unspecified"))
    )
    (net (code "308") (name "unconnected-(U10-SCK{slash}PB5{slash}13-Pad14)") (class "Default")
      (node (ref "U10") (pin "14") (pinfunction "SCK/PB5/13_14") (pintype "unspecified"))
    )
    (net (code "309") (name "unconnected-(U10-SCL-Pad18)") (class "Default")
      (node (ref "U10") (pin "18") (pinfunction "SCL_18") (pintype "unspecified"))
    )
    (net (code "310") (name "unconnected-(U10-SDA-Pad17)") (class "Default")
      (node (ref "U10") (pin "17") (pinfunction "SDA_17") (pintype "unspecified"))
    )
    (net (code "311") (name "unconnected-(U10-SS{slash}PWR{slash}PB2{slash}10-Pad11)") (class "Default")
      (node (ref "U10") (pin "11") (pinfunction "SS/PWR/PB2/10_11") (pintype "unspecified"))
    )
    (net (code "312") (name "unconnected-(U10-TX{slash}PD1{slash}1-Pad2)") (class "Default")
      (node (ref "U10") (pin "2") (pinfunction "TX/PD1/1_2") (pintype "unspecified"))
    )
    (net (code "313") (name "unconnected-(U10-VIN-Pad25)") (class "Default")
      (node (ref "U10") (pin "25") (pinfunction "VIN_25") (pintype "passive"))
    )
    (net (code "314") (name "unconnected-(U15-3V3-Pad17)") (class "Default")
      (node (ref "U15") (pin "17") (pinfunction "3V3_17") (pintype "unspecified"))
    )
    (net (code "315") (name "unconnected-(U15-A0-Pad19)") (class "Default")
      (node (ref "U15") (pin "19") (pinfunction "A0_19") (pintype "unspecified"))
    )
    (net (code "316") (name "unconnected-(U15-A1-Pad20)") (class "Default")
      (node (ref "U15") (pin "20") (pinfunction "A1_20") (pintype "unspecified"))
    )
    (net (code "317") (name "unconnected-(U15-A2-Pad21)") (class "Default")
      (node (ref "U15") (pin "21") (pinfunction "A2_21") (pintype "unspecified"))
    )
    (net (code "318") (name "unconnected-(U15-A6-Pad25)") (class "Default")
      (node (ref "U15") (pin "25") (pinfunction "A6_25") (pintype "unspecified"))
    )
    (net (code "319") (name "unconnected-(U15-A7-Pad26)") (class "Default")
      (node (ref "U15") (pin "26") (pinfunction "A7_26") (pintype "unspecified"))
    )
    (net (code "320") (name "unconnected-(U15-AREF-Pad18)") (class "Default")
      (node (ref "U15") (pin "18") (pinfunction "AREF_18") (pintype "unspecified"))
    )
    (net (code "321") (name "unconnected-(U15-D0{slash}RX-Pad2)") (class "Default")
      (node (ref "U15") (pin "2") (pinfunction "D0/RX_2") (pintype "unspecified"))
    )
    (net (code "322") (name "unconnected-(U15-D1{slash}TX-Pad1)") (class "Default")
      (node (ref "U15") (pin "1") (pinfunction "D1/TX_1") (pintype "unspecified"))
    )
    (net (code "323") (name "unconnected-(U15-D2-Pad5)") (class "Default")
      (node (ref "U15") (pin "5") (pinfunction "D2_5") (pintype "unspecified"))
    )
    (net (code "324") (name "unconnected-(U15-D3-Pad6)") (class "Default")
      (node (ref "U15") (pin "6") (pinfunction "D3_6") (pintype "unspecified"))
    )
    (net (code "325") (name "unconnected-(U15-D4-Pad7)") (class "Default")
      (node (ref "U15") (pin "7") (pinfunction "D4_7") (pintype "unspecified"))
    )
    (net (code "326") (name "unconnected-(U15-D5-Pad8)") (class "Default")
      (node (ref "U15") (pin "8") (pinfunction "D5_8") (pintype "unspecified"))
    )
    (net (code "327") (name "unconnected-(U15-D6-Pad9)") (class "Default")
      (node (ref "U15") (pin "9") (pinfunction "D6_9") (pintype "unspecified"))
    )
    (net (code "328") (name "unconnected-(U15-D7-Pad10)") (class "Default")
      (node (ref "U15") (pin "10") (pinfunction "D7_10") (pintype "unspecified"))
    )
    (net (code "329") (name "unconnected-(U15-D8-Pad11)") (class "Default")
      (node (ref "U15") (pin "11") (pinfunction "D8_11") (pintype "unspecified"))
    )
    (net (code "330") (name "unconnected-(U15-D9-Pad12)") (class "Default")
      (node (ref "U15") (pin "12") (pinfunction "D9_12") (pintype "unspecified"))
    )
    (net (code "331") (name "unconnected-(U15-D10-Pad13)") (class "Default")
      (node (ref "U15") (pin "13") (pinfunction "D10_13") (pintype "unspecified"))
    )
    (net (code "332") (name "unconnected-(U15-D11-Pad14)") (class "Default")
      (node (ref "U15") (pin "14") (pinfunction "D11_14") (pintype "unspecified"))
    )
    (net (code "333") (name "unconnected-(U15-D12-Pad15)") (class "Default")
      (node (ref "U15") (pin "15") (pinfunction "D12_15") (pintype "unspecified"))
    )
    (net (code "334") (name "unconnected-(U15-D13-Pad16)") (class "Default")
      (node (ref "U15") (pin "16") (pinfunction "D13_16") (pintype "unspecified"))
    )
    (net (code "335") (name "unconnected-(U15-GND-Pad4)") (class "Default")
      (node (ref "U15") (pin "4") (pinfunction "GND_4") (pintype "unspecified"))
    )
    (net (code "336") (name "unconnected-(U15-RESET-Pad3)") (class "Default")
      (node (ref "U15") (pin "3") (pinfunction "RESET_3") (pintype "unspecified"))
    )
    (net (code "337") (name "unconnected-(U15-RESET-Pad28)") (class "Default")
      (node (ref "U15") (pin "28") (pinfunction "RESET_28") (pintype "unspecified"))
    )
    (net (code "338") (name "unconnected-(U15-VIN-Pad30)") (class "Default")
      (node (ref "U15") (pin "30") (pinfunction "VIN_30") (pintype "unspecified"))
    )
    (net (code "339") (name "unconnected-(U16-3V-Pad29)") (class "Default")
      (node (ref "U16") (pin "29") (pinfunction "3V_29") (pintype "passive"))
    )
    (net (code "340") (name "unconnected-(U16-14{slash}A0{slash}PC0-Pad24)") (class "Default")
      (node (ref "U16") (pin "24") (pinfunction "14/A0/PC0_24") (pintype "unspecified"))
    )
    (net (code "341") (name "unconnected-(U16-15{slash}A1{slash}PC1-Pad23)") (class "Default")
      (node (ref "U16") (pin "23") (pinfunction "15/A1/PC1_23") (pintype "unspecified"))
    )
    (net (code "342") (name "unconnected-(U16-16{slash}A2{slash}PC2-Pad22)") (class "Default")
      (node (ref "U16") (pin "22") (pinfunction "16/A2/PC2_22") (pintype "unspecified"))
    )
    (net (code "343") (name "unconnected-(U16-AREF-Pad16)") (class "Default")
      (node (ref "U16") (pin "16") (pinfunction "AREF_16") (pintype "unspecified"))
    )
    (net (code "344") (name "unconnected-(U16-GND-Pad15)") (class "Default")
      (node (ref "U16") (pin "15") (pinfunction "GND_15") (pintype "passive"))
    )
    (net (code "345") (name "unconnected-(U16-GND2-Pad27)") (class "Default")
      (node (ref "U16") (pin "27") (pinfunction "GND2_27") (pintype "passive"))
    )
    (net (code "346") (name "unconnected-(U16-INT0{slash}PD2{slash}2-Pad3)") (class "Default")
      (node (ref "U16") (pin "3") (pinfunction "INT0/PD2/2_3") (pintype "unspecified"))
    )
    (net (code "347") (name "unconnected-(U16-INT1{slash}PWR{slash}PD3{slash}3-Pad4)") (class "Default")
      (node (ref "U16") (pin "4") (pinfunction "INT1/PWR/PD3/3_4") (pintype "unspecified"))
    )
    (net (code "348") (name "unconnected-(U16-IOREF-Pad31)") (class "Default")
      (node (ref "U16") (pin "31") (pinfunction "IOREF_31") (pintype "unspecified"))
    )
    (net (code "349") (name "unconnected-(U16-MISO{slash}PB4{slash}12-Pad13)") (class "Default")
      (node (ref "U16") (pin "13") (pinfunction "MISO/PB4/12_13") (pintype "unspecified"))
    )
    (net (code "350") (name "unconnected-(U16-MOSI{slash}PWR{slash}PB3{slash}11-Pad12)") (class "Default")
      (node (ref "U16") (pin "12") (pinfunction "MOSI/PWR/PB3/11_12") (pintype "unspecified"))
    )
    (net (code "351") (name "unconnected-(U16-NC-Pad32)") (class "Default")
      (node (ref "U16") (pin "32") (pinfunction "NC_32") (pintype "unspecified"))
    )
    (net (code "352") (name "unconnected-(U16-PB0{slash}8-Pad9)") (class "Default")
      (node (ref "U16") (pin "9") (pinfunction "PB0/8_9") (pintype "unspecified"))
    )
    (net (code "353") (name "unconnected-(U16-PD4{slash}4-Pad5)") (class "Default")
      (node (ref "U16") (pin "5") (pinfunction "PD4/4_5") (pintype "unspecified"))
    )
    (net (code "354") (name "unconnected-(U16-PD7{slash}7-Pad8)") (class "Default")
      (node (ref "U16") (pin "8") (pinfunction "PD7/7_8") (pintype "unspecified"))
    )
    (net (code "355") (name "unconnected-(U16-PWR{slash}PB1{slash}9-Pad10)") (class "Default")
      (node (ref "U16") (pin "10") (pinfunction "PWR/PB1/9_10") (pintype "unspecified"))
    )
    (net (code "356") (name "unconnected-(U16-PWR{slash}PD5{slash}5-Pad6)") (class "Default")
      (node (ref "U16") (pin "6") (pinfunction "PWR/PD5/5_6") (pintype "unspecified"))
    )
    (net (code "357") (name "unconnected-(U16-PWR{slash}PD6{slash}6-Pad7)") (class "Default")
      (node (ref "U16") (pin "7") (pinfunction "PWR/PD6/6_7") (pintype "unspecified"))
    )
    (net (code "358") (name "unconnected-(U16-RESET-Pad30)") (class "Default")
      (node (ref "U16") (pin "30") (pinfunction "RESET_30") (pintype "unspecified"))
    )
    (net (code "359") (name "unconnected-(U16-RX{slash}PD0{slash}0-Pad1)") (class "Default")
      (node (ref "U16") (pin "1") (pinfunction "RX/PD0/0_1") (pintype "unspecified"))
    )
    (net (code "360") (name "unconnected-(U16-SCK{slash}PB5{slash}13-Pad14)") (class "Default")
      (node (ref "U16") (pin "14") (pinfunction "SCK/PB5/13_14") (pintype "unspecified"))
    )
    (net (code "361") (name "unconnected-(U16-SCL-Pad18)") (class "Default")
      (node (ref "U16") (pin "18") (pinfunction "SCL_18") (pintype "unspecified"))
    )
    (net (code "362") (name "unconnected-(U16-SDA-Pad17)") (class "Default")
      (node (ref "U16") (pin "17") (pinfunction "SDA_17") (pintype "unspecified"))
    )
    (net (code "363") (name "unconnected-(U16-SS{slash}PWR{slash}PB2{slash}10-Pad11)") (class "Default")
      (node (ref "U16") (pin "11") (pinfunction "SS/PWR/PB2/10_11") (pintype "unspecified"))
    )
    (net (code "364") (name "unconnected-(U16-TX{slash}PD1{slash}1-Pad2)") (class "Default")
      (node (ref "U16") (pin "2") (pinfunction "TX/PD1/1_2") (pintype "unspecified"))
    )
    (net (code "365") (name "unconnected-(U16-VIN-Pad25)") (class "Default")
      (node (ref "U16") (pin "25") (pinfunction "VIN_25") (pintype "passive"))
    )
    (net (code "366") (name "unconnected-(U17-3V3-Pad17)") (class "Default")
      (node (ref "U17") (pin "17") (pinfunction "3V3_17") (pintype "unspecified"))
    )
    (net (code "367") (name "unconnected-(U17-A0-Pad19)") (class "Default")
      (node (ref "U17") (pin "19") (pinfunction "A0_19") (pintype "unspecified"))
    )
    (net (code "368") (name "unconnected-(U17-A1-Pad20)") (class "Default")
      (node (ref "U17") (pin "20") (pinfunction "A1_20") (pintype "unspecified"))
    )
    (net (code "369") (name "unconnected-(U17-A2-Pad21)") (class "Default")
      (node (ref "U17") (pin "21") (pinfunction "A2_21") (pintype "unspecified"))
    )
    (net (code "370") (name "unconnected-(U17-A3-Pad22)") (class "Default")
      (node (ref "U17") (pin "22") (pinfunction "A3_22") (pintype "unspecified"))
    )
    (net (code "371") (name "unconnected-(U17-A4-Pad23)") (class "Default")
      (node (ref "U17") (pin "23") (pinfunction "A4_23") (pintype "unspecified"))
    )
    (net (code "372") (name "unconnected-(U17-A5-Pad24)") (class "Default")
      (node (ref "U17") (pin "24") (pinfunction "A5_24") (pintype "unspecified"))
    )
    (net (code "373") (name "unconnected-(U17-A6-Pad25)") (class "Default")
      (node (ref "U17") (pin "25") (pinfunction "A6_25") (pintype "unspecified"))
    )
    (net (code "374") (name "unconnected-(U17-A7-Pad26)") (class "Default")
      (node (ref "U17") (pin "26") (pinfunction "A7_26") (pintype "unspecified"))
    )
    (net (code "375") (name "unconnected-(U17-AREF-Pad18)") (class "Default")
      (node (ref "U17") (pin "18") (pinfunction "AREF_18") (pintype "unspecified"))
    )
    (net (code "376") (name "unconnected-(U17-D0{slash}RX-Pad2)") (class "Default")
      (node (ref "U17") (pin "2") (pinfunction "D0/RX_2") (pintype "unspecified"))
    )
    (net (code "377") (name "unconnected-(U17-D1{slash}TX-Pad1)") (class "Default")
      (node (ref "U17") (pin "1") (pinfunction "D1/TX_1") (pintype "unspecified"))
    )
    (net (code "378") (name "unconnected-(U17-D2-Pad5)") (class "Default")
      (node (ref "U17") (pin "5") (pinfunction "D2_5") (pintype "unspecified"))
    )
    (net (code "379") (name "unconnected-(U17-D3-Pad6)") (class "Default")
      (node (ref "U17") (pin "6") (pinfunction "D3_6") (pintype "unspecified"))
    )
    (net (code "380") (name "unconnected-(U17-D4-Pad7)") (class "Default")
      (node (ref "U17") (pin "7") (pinfunction "D4_7") (pintype "unspecified"))
    )
    (net (code "381") (name "unconnected-(U17-D5-Pad8)") (class "Default")
      (node (ref "U17") (pin "8") (pinfunction "D5_8") (pintype "unspecified"))
    )
    (net (code "382") (name "unconnected-(U17-D6-Pad9)") (class "Default")
      (node (ref "U17") (pin "9") (pinfunction "D6_9") (pintype "unspecified"))
    )
    (net (code "383") (name "unconnected-(U17-D7-Pad10)") (class "Default")
      (node (ref "U17") (pin "10") (pinfunction "D7_10") (pintype "unspecified"))
    )
    (net (code "384") (name "unconnected-(U17-D9-Pad12)") (class "Default")
      (node (ref "U17") (pin "12") (pinfunction "D9_12") (pintype "unspecified"))
    )
    (net (code "385") (name "unconnected-(U17-D10-Pad13)") (class "Default")
      (node (ref "U17") (pin "13") (pinfunction "D10_13") (pintype "unspecified"))
    )
    (net (code "386") (name "unconnected-(U17-D11-Pad14)") (class "Default")
      (node (ref "U17") (pin "14") (pinfunction "D11_14") (pintype "unspecified"))
    )
    (net (code "387") (name "unconnected-(U17-D12-Pad15)") (class "Default")
      (node (ref "U17") (pin "15") (pinfunction "D12_15") (pintype "unspecified"))
    )
    (net (code "388") (name "unconnected-(U17-D13-Pad16)") (class "Default")
      (node (ref "U17") (pin "16") (pinfunction "D13_16") (pintype "unspecified"))
    )
    (net (code "389") (name "unconnected-(U17-GND-Pad4)") (class "Default")
      (node (ref "U17") (pin "4") (pinfunction "GND_4") (pintype "unspecified"))
    )
    (net (code "390") (name "unconnected-(U17-RESET-Pad3)") (class "Default")
      (node (ref "U17") (pin "3") (pinfunction "RESET_3") (pintype "unspecified"))
    )
    (net (code "391") (name "unconnected-(U17-RESET-Pad28)") (class "Default")
      (node (ref "U17") (pin "28") (pinfunction "RESET_28") (pintype "unspecified"))
    )
    (net (code "392") (name "unconnected-(U17-VIN-Pad30)") (class "Default")
      (node (ref "U17") (pin "30") (pinfunction "VIN_30") (pintype "unspecified"))
    )
    (net (code "393") (name "unconnected-(U18-3V-Pad29)") (class "Default")
      (node (ref "U18") (pin "29") (pinfunction "3V_29") (pintype "passive"))
    )
    (net (code "394") (name "unconnected-(U18-14{slash}A0{slash}PC0-Pad24)") (class "Default")
      (node (ref "U18") (pin "24") (pinfunction "14/A0/PC0_24") (pintype "unspecified"))
    )
    (net (code "395") (name "unconnected-(U18-15{slash}A1{slash}PC1-Pad23)") (class "Default")
      (node (ref "U18") (pin "23") (pinfunction "15/A1/PC1_23") (pintype "unspecified"))
    )
    (net (code "396") (name "unconnected-(U18-16{slash}A2{slash}PC2-Pad22)") (class "Default")
      (node (ref "U18") (pin "22") (pinfunction "16/A2/PC2_22") (pintype "unspecified"))
    )
    (net (code "397") (name "unconnected-(U18-17{slash}A3{slash}PC3-Pad21)") (class "Default")
      (node (ref "U18") (pin "21") (pinfunction "17/A3/PC3_21") (pintype "unspecified"))
    )
    (net (code "398") (name "unconnected-(U18-18{slash}A4{slash}PC4{slash}SDA-Pad20)") (class "Default")
      (node (ref "U18") (pin "20") (pinfunction "18/A4/PC4/SDA_20") (pintype "unspecified"))
    )
    (net (code "399") (name "unconnected-(U18-19{slash}A5{slash}PC5{slash}SCL-Pad19)") (class "Default")
      (node (ref "U18") (pin "19") (pinfunction "19/A5/PC5/SCL_19") (pintype "unspecified"))
    )
    (net (code "400") (name "unconnected-(U18-AREF-Pad16)") (class "Default")
      (node (ref "U18") (pin "16") (pinfunction "AREF_16") (pintype "unspecified"))
    )
    (net (code "401") (name "unconnected-(U18-GND-Pad15)") (class "Default")
      (node (ref "U18") (pin "15") (pinfunction "GND_15") (pintype "passive"))
    )
    (net (code "402") (name "unconnected-(U18-GND2-Pad27)") (class "Default")
      (node (ref "U18") (pin "27") (pinfunction "GND2_27") (pintype "passive"))
    )
    (net (code "403") (name "unconnected-(U18-INT0{slash}PD2{slash}2-Pad3)") (class "Default")
      (node (ref "U18") (pin "3") (pinfunction "INT0/PD2/2_3") (pintype "unspecified"))
    )
    (net (code "404") (name "unconnected-(U18-INT1{slash}PWR{slash}PD3{slash}3-Pad4)") (class "Default")
      (node (ref "U18") (pin "4") (pinfunction "INT1/PWR/PD3/3_4") (pintype "unspecified"))
    )
    (net (code "405") (name "unconnected-(U18-IOREF-Pad31)") (class "Default")
      (node (ref "U18") (pin "31") (pinfunction "IOREF_31") (pintype "unspecified"))
    )
    (net (code "406") (name "unconnected-(U18-MISO{slash}PB4{slash}12-Pad13)") (class "Default")
      (node (ref "U18") (pin "13") (pinfunction "MISO/PB4/12_13") (pintype "unspecified"))
    )
    (net (code "407") (name "unconnected-(U18-MOSI{slash}PWR{slash}PB3{slash}11-Pad12)") (class "Default")
      (node (ref "U18") (pin "12") (pinfunction "MOSI/PWR/PB3/11_12") (pintype "unspecified"))
    )
    (net (code "408") (name "unconnected-(U18-NC-Pad32)") (class "Default")
      (node (ref "U18") (pin "32") (pinfunction "NC_32") (pintype "unspecified"))
    )
    (net (code "409") (name "unconnected-(U18-PD4{slash}4-Pad5)") (class "Default")
      (node (ref "U18") (pin "5") (pinfunction "PD4/4_5") (pintype "unspecified"))
    )
    (net (code "410") (name "unconnected-(U18-PD7{slash}7-Pad8)") (class "Default")
      (node (ref "U18") (pin "8") (pinfunction "PD7/7_8") (pintype "unspecified"))
    )
    (net (code "411") (name "unconnected-(U18-PWR{slash}PB1{slash}9-Pad10)") (class "Default")
      (node (ref "U18") (pin "10") (pinfunction "PWR/PB1/9_10") (pintype "unspecified"))
    )
    (net (code "412") (name "unconnected-(U18-PWR{slash}PD5{slash}5-Pad6)") (class "Default")
      (node (ref "U18") (pin "6") (pinfunction "PWR/PD5/5_6") (pintype "unspecified"))
    )
    (net (code "413") (name "unconnected-(U18-PWR{slash}PD6{slash}6-Pad7)") (class "Default")
      (node (ref "U18") (pin "7") (pinfunction "PWR/PD6/6_7") (pintype "unspecified"))
    )
    (net (code "414") (name "unconnected-(U18-RESET-Pad30)") (class "Default")
      (node (ref "U18") (pin "30") (pinfunction "RESET_30") (pintype "unspecified"))
    )
    (net (code "415") (name "unconnected-(U18-RX{slash}PD0{slash}0-Pad1)") (class "Default")
      (node (ref "U18") (pin "1") (pinfunction "RX/PD0/0_1") (pintype "unspecified"))
    )
    (net (code "416") (name "unconnected-(U18-SCK{slash}PB5{slash}13-Pad14)") (class "Default")
      (node (ref "U18") (pin "14") (pinfunction "SCK/PB5/13_14") (pintype "unspecified"))
    )
    (net (code "417") (name "unconnected-(U18-SCL-Pad18)") (class "Default")
      (node (ref "U18") (pin "18") (pinfunction "SCL_18") (pintype "unspecified"))
    )
    (net (code "418") (name "unconnected-(U18-SDA-Pad17)") (class "Default")
      (node (ref "U18") (pin "17") (pinfunction "SDA_17") (pintype "unspecified"))
    )
    (net (code "419") (name "unconnected-(U18-SS{slash}PWR{slash}PB2{slash}10-Pad11)") (class "Default")
      (node (ref "U18") (pin "11") (pinfunction "SS/PWR/PB2/10_11") (pintype "unspecified"))
    )
    (net (code "420") (name "unconnected-(U18-TX{slash}PD1{slash}1-Pad2)") (class "Default")
      (node (ref "U18") (pin "2") (pinfunction "TX/PD1/1_2") (pintype "unspecified"))
    )
    (net (code "421") (name "unconnected-(U18-VIN-Pad25)") (class "Default")
      (node (ref "U18") (pin "25") (pinfunction "VIN_25") (pintype "passive"))
    )
    (net (code "422") (name "unconnected-(U19-3V3-Pad17)") (class "Default")
      (node (ref "U19") (pin "17") (pinfunction "3V3_17") (pintype "unspecified"))
    )
    (net (code "423") (name "unconnected-(U19-A0-Pad19)") (class "Default")
      (node (ref "U19") (pin "19") (pinfunction "A0_19") (pintype "unspecified"))
    )
    (net (code "424") (name "unconnected-(U19-A1-Pad20)") (class "Default")
      (node (ref "U19") (pin "20") (pinfunction "A1_20") (pintype "unspecified"))
    )
    (net (code "425") (name "unconnected-(U19-A2-Pad21)") (class "Default")
      (node (ref "U19") (pin "21") (pinfunction "A2_21") (pintype "unspecified"))
    )
    (net (code "426") (name "unconnected-(U19-A3-Pad22)") (class "Default")
      (node (ref "U19") (pin "22") (pinfunction "A3_22") (pintype "unspecified"))
    )
    (net (code "427") (name "unconnected-(U19-A6-Pad25)") (class "Default")
      (node (ref "U19") (pin "25") (pinfunction "A6_25") (pintype "unspecified"))
    )
    (net (code "428") (name "unconnected-(U19-A7-Pad26)") (class "Default")
      (node (ref "U19") (pin "26") (pinfunction "A7_26") (pintype "unspecified"))
    )
    (net (code "429") (name "unconnected-(U19-AREF-Pad18)") (class "Default")
      (node (ref "U19") (pin "18") (pinfunction "AREF_18") (pintype "unspecified"))
    )
    (net (code "430") (name "unconnected-(U19-D0{slash}RX-Pad2)") (class "Default")
      (node (ref "U19") (pin "2") (pinfunction "D0/RX_2") (pintype "unspecified"))
    )
    (net (code "431") (name "unconnected-(U19-D1{slash}TX-Pad1)") (class "Default")
      (node (ref "U19") (pin "1") (pinfunction "D1/TX_1") (pintype "unspecified"))
    )
    (net (code "432") (name "unconnected-(U19-D2-Pad5)") (class "Default")
      (node (ref "U19") (pin "5") (pinfunction "D2_5") (pintype "unspecified"))
    )
    (net (code "433") (name "unconnected-(U19-D3-Pad6)") (class "Default")
      (node (ref "U19") (pin "6") (pinfunction "D3_6") (pintype "unspecified"))
    )
    (net (code "434") (name "unconnected-(U19-D4-Pad7)") (class "Default")
      (node (ref "U19") (pin "7") (pinfunction "D4_7") (pintype "unspecified"))
    )
    (net (code "435") (name "unconnected-(U19-D5-Pad8)") (class "Default")
      (node (ref "U19") (pin "8") (pinfunction "D5_8") (pintype "unspecified"))
    )
    (net (code "436") (name "unconnected-(U19-D6-Pad9)") (class "Default")
      (node (ref "U19") (pin "9") (pinfunction "D6_9") (pintype "unspecified"))
    )
    (net (code "437") (name "unconnected-(U19-D7-Pad10)") (class "Default")
      (node (ref "U19") (pin "10") (pinfunction "D7_10") (pintype "unspecified"))
    )
    (net (code "438") (name "unconnected-(U19-D8-Pad11)") (class "Default")
      (node (ref "U19") (pin "11") (pinfunction "D8_11") (pintype "unspecified"))
    )
    (net (code "439") (name "unconnected-(U19-D9-Pad12)") (class "Default")
      (node (ref "U19") (pin "12") (pinfunction "D9_12") (pintype "unspecified"))
    )
    (net (code "440") (name "unconnected-(U19-D10-Pad13)") (class "Default")
      (node (ref "U19") (pin "13") (pinfunction "D10_13") (pintype "unspecified"))
    )
    (net (code "441") (name "unconnected-(U19-D11-Pad14)") (class "Default")
      (node (ref "U19") (pin "14") (pinfunction "D11_14") (pintype "unspecified"))
    )
    (net (code "442") (name "unconnected-(U19-D12-Pad15)") (class "Default")
      (node (ref "U19") (pin "15") (pinfunction "D12_15") (pintype "unspecified"))
    )
    (net (code "443") (name "unconnected-(U19-D13-Pad16)") (class "Default")
      (node (ref "U19") (pin "16") (pinfunction "D13_16") (pintype "unspecified"))
    )
    (net (code "444") (name "unconnected-(U19-GND-Pad4)") (class "Default")
      (node (ref "U19") (pin "4") (pinfunction "GND_4") (pintype "unspecified"))
    )
    (net (code "445") (name "unconnected-(U19-RESET-Pad3)") (class "Default")
      (node (ref "U19") (pin "3") (pinfunction "RESET_3") (pintype "unspecified"))
    )
    (net (code "446") (name "unconnected-(U19-RESET-Pad28)") (class "Default")
      (node (ref "U19") (pin "28") (pinfunction "RESET_28") (pintype "unspecified"))
    )
    (net (code "447") (name "unconnected-(U19-VIN-Pad30)") (class "Default")
      (node (ref "U19") (pin "30") (pinfunction "VIN_30") (pintype "unspecified"))
    )
    (net (code "448") (name "unconnected-(U20-3V-Pad29)") (class "Default")
      (node (ref "U20") (pin "29") (pinfunction "3V_29") (pintype "passive"))
    )
    (net (code "449") (name "unconnected-(U20-14{slash}A0{slash}PC0-Pad24)") (class "Default")
      (node (ref "U20") (pin "24") (pinfunction "14/A0/PC0_24") (pintype "unspecified"))
    )
    (net (code "450") (name "unconnected-(U20-15{slash}A1{slash}PC1-Pad23)") (class "Default")
      (node (ref "U20") (pin "23") (pinfunction "15/A1/PC1_23") (pintype "unspecified"))
    )
    (net (code "451") (name "unconnected-(U20-16{slash}A2{slash}PC2-Pad22)") (class "Default")
      (node (ref "U20") (pin "22") (pinfunction "16/A2/PC2_22") (pintype "unspecified"))
    )
    (net (code "452") (name "unconnected-(U20-17{slash}A3{slash}PC3-Pad21)") (class "Default")
      (node (ref "U20") (pin "21") (pinfunction "17/A3/PC3_21") (pintype "unspecified"))
    )
    (net (code "453") (name "unconnected-(U20-AREF-Pad16)") (class "Default")
      (node (ref "U20") (pin "16") (pinfunction "AREF_16") (pintype "unspecified"))
    )
    (net (code "454") (name "unconnected-(U20-GND-Pad15)") (class "Default")
      (node (ref "U20") (pin "15") (pinfunction "GND_15") (pintype "passive"))
    )
    (net (code "455") (name "unconnected-(U20-GND2-Pad27)") (class "Default")
      (node (ref "U20") (pin "27") (pinfunction "GND2_27") (pintype "passive"))
    )
    (net (code "456") (name "unconnected-(U20-INT0{slash}PD2{slash}2-Pad3)") (class "Default")
      (node (ref "U20") (pin "3") (pinfunction "INT0/PD2/2_3") (pintype "unspecified"))
    )
    (net (code "457") (name "unconnected-(U20-INT1{slash}PWR{slash}PD3{slash}3-Pad4)") (class "Default")
      (node (ref "U20") (pin "4") (pinfunction "INT1/PWR/PD3/3_4") (pintype "unspecified"))
    )
    (net (code "458") (name "unconnected-(U20-IOREF-Pad31)") (class "Default")
      (node (ref "U20") (pin "31") (pinfunction "IOREF_31") (pintype "unspecified"))
    )
    (net (code "459") (name "unconnected-(U20-MISO{slash}PB4{slash}12-Pad13)") (class "Default")
      (node (ref "U20") (pin "13") (pinfunction "MISO/PB4/12_13") (pintype "unspecified"))
    )
    (net (code "460") (name "unconnected-(U20-MOSI{slash}PWR{slash}PB3{slash}11-Pad12)") (class "Default")
      (node (ref "U20") (pin "12") (pinfunction "MOSI/PWR/PB3/11_12") (pintype "unspecified"))
    )
    (net (code "461") (name "unconnected-(U20-NC-Pad32)") (class "Default")
      (node (ref "U20") (pin "32") (pinfunction "NC_32") (pintype "unspecified"))
    )
    (net (code "462") (name "unconnected-(U20-PB0{slash}8-Pad9)") (class "Default")
      (node (ref "U20") (pin "9") (pinfunction "PB0/8_9") (pintype "unspecified"))
    )
    (net (code "463") (name "unconnected-(U20-PD4{slash}4-Pad5)") (class "Default")
      (node (ref "U20") (pin "5") (pinfunction "PD4/4_5") (pintype "unspecified"))
    )
    (net (code "464") (name "unconnected-(U20-PD7{slash}7-Pad8)") (class "Default")
      (node (ref "U20") (pin "8") (pinfunction "PD7/7_8") (pintype "unspecified"))
    )
    (net (code "465") (name "unconnected-(U20-PWR{slash}PB1{slash}9-Pad10)") (class "Default")
      (node (ref "U20") (pin "10") (pinfunction "PWR/PB1/9_10") (pintype "unspecified"))
    )
    (net (code "466") (name "unconnected-(U20-PWR{slash}PD5{slash}5-Pad6)") (class "Default")
      (node (ref "U20") (pin "6") (pinfunction "PWR/PD5/5_6") (pintype "unspecified"))
    )
    (net (code "467") (name "unconnected-(U20-PWR{slash}PD6{slash}6-Pad7)") (class "Default")
      (node (ref "U20") (pin "7") (pinfunction "PWR/PD6/6_7") (pintype "unspecified"))
    )
    (net (code "468") (name "unconnected-(U20-RESET-Pad30)") (class "Default")
      (node (ref "U20") (pin "30") (pinfunction "RESET_30") (pintype "unspecified"))
    )
    (net (code "469") (name "unconnected-(U20-RX{slash}PD0{slash}0-Pad1)") (class "Default")
      (node (ref "U20") (pin "1") (pinfunction "RX/PD0/0_1") (pintype "unspecified"))
    )
    (net (code "470") (name "unconnected-(U20-SCK{slash}PB5{slash}13-Pad14)") (class "Default")
      (node (ref "U20") (pin "14") (pinfunction "SCK/PB5/13_14") (pintype "unspecified"))
    )
    (net (code "471") (name "unconnected-(U20-SCL-Pad18)") (class "Default")
      (node (ref "U20") (pin "18") (pinfunction "SCL_18") (pintype "unspecified"))
    )
    (net (code "472") (name "unconnected-(U20-SDA-Pad17)") (class "Default")
      (node (ref "U20") (pin "17") (pinfunction "SDA_17") (pintype "unspecified"))
    )
    (net (code "473") (name "unconnected-(U20-SS{slash}PWR{slash}PB2{slash}10-Pad11)") (class "Default")
      (node (ref "U20") (pin "11") (pinfunction "SS/PWR/PB2/10_11") (pintype "unspecified"))
    )
    (net (code "474") (name "unconnected-(U20-TX{slash}PD1{slash}1-Pad2)") (class "Default")
      (node (ref "U20") (pin "2") (pinfunction "TX/PD1/1_2") (pintype "unspecified"))
    )
    (net (code "475") (name "unconnected-(U20-VIN-Pad25)") (class "Default")
      (node (ref "U20") (pin "25") (pinfunction "VIN_25") (pintype "passive"))
    )
    (net (code "476") (name "unconnected-(U24-3V3-Pad17)") (class "Default")
      (node (ref "U24") (pin "17") (pinfunction "3V3_17") (pintype "unspecified"))
    )
    (net (code "477") (name "unconnected-(U24-A6-Pad25)") (class "Default")
      (node (ref "U24") (pin "25") (pinfunction "A6_25") (pintype "unspecified"))
    )
    (net (code "478") (name "unconnected-(U24-A7-Pad26)") (class "Default")
      (node (ref "U24") (pin "26") (pinfunction "A7_26") (pintype "unspecified"))
    )
    (net (code "479") (name "unconnected-(U24-AREF-Pad18)") (class "Default")
      (node (ref "U24") (pin "18") (pinfunction "AREF_18") (pintype "unspecified"))
    )
    (net (code "480") (name "unconnected-(U24-D0{slash}RX-Pad2)") (class "Default")
      (node (ref "U24") (pin "2") (pinfunction "D0/RX_2") (pintype "unspecified"))
    )
    (net (code "481") (name "unconnected-(U24-D1{slash}TX-Pad1)") (class "Default")
      (node (ref "U24") (pin "1") (pinfunction "D1/TX_1") (pintype "unspecified"))
    )
    (net (code "482") (name "unconnected-(U24-D2-Pad5)") (class "Default")
      (node (ref "U24") (pin "5") (pinfunction "D2_5") (pintype "unspecified"))
    )
    (net (code "483") (name "unconnected-(U24-D3-Pad6)") (class "Default")
      (node (ref "U24") (pin "6") (pinfunction "D3_6") (pintype "unspecified"))
    )
    (net (code "484") (name "unconnected-(U24-D4-Pad7)") (class "Default")
      (node (ref "U24") (pin "7") (pinfunction "D4_7") (pintype "unspecified"))
    )
    (net (code "485") (name "unconnected-(U24-D5-Pad8)") (class "Default")
      (node (ref "U24") (pin "8") (pinfunction "D5_8") (pintype "unspecified"))
    )
    (net (code "486") (name "unconnected-(U24-D6-Pad9)") (class "Default")
      (node (ref "U24") (pin "9") (pinfunction "D6_9") (pintype "unspecified"))
    )
    (net (code "487") (name "unconnected-(U24-D7-Pad10)") (class "Default")
      (node (ref "U24") (pin "10") (pinfunction "D7_10") (pintype "unspecified"))
    )
    (net (code "488") (name "unconnected-(U24-D8-Pad11)") (class "Default")
      (node (ref "U24") (pin "11") (pinfunction "D8_11") (pintype "unspecified"))
    )
    (net (code "489") (name "unconnected-(U24-D9-Pad12)") (class "Default")
      (node (ref "U24") (pin "12") (pinfunction "D9_12") (pintype "unspecified"))
    )
    (net (code "490") (name "unconnected-(U24-D10-Pad13)") (class "Default")
      (node (ref "U24") (pin "13") (pinfunction "D10_13") (pintype "unspecified"))
    )
    (net (code "491") (name "unconnected-(U24-D11-Pad14)") (class "Default")
      (node (ref "U24") (pin "14") (pinfunction "D11_14") (pintype "unspecified"))
    )
    (net (code "492") (name "unconnected-(U24-D12-Pad15)") (class "Default")
      (node (ref "U24") (pin "15") (pinfunction "D12_15") (pintype "unspecified"))
    )
    (net (code "493") (name "unconnected-(U24-D13-Pad16)") (class "Default")
      (node (ref "U24") (pin "16") (pinfunction "D13_16") (pintype "unspecified"))
    )
    (net (code "494") (name "unconnected-(U24-GND-Pad4)") (class "Default")
      (node (ref "U24") (pin "4") (pinfunction "GND_4") (pintype "unspecified"))
    )
    (net (code "495") (name "unconnected-(U24-RESET-Pad3)") (class "Default")
      (node (ref "U24") (pin "3") (pinfunction "RESET_3") (pintype "unspecified"))
    )
    (net (code "496") (name "unconnected-(U24-RESET-Pad28)") (class "Default")
      (node (ref "U24") (pin "28") (pinfunction "RESET_28") (pintype "unspecified"))
    )
    (net (code "497") (name "unconnected-(U24-VIN-Pad30)") (class "Default")
      (node (ref "U24") (pin "30") (pinfunction "VIN_30") (pintype "unspecified"))
    )
    (net (code "498") (name "unconnected-(U27-3V-Pad29)") (class "Default")
      (node (ref "U27") (pin "29") (pinfunction "3V_29") (pintype "passive"))
    )
    (net (code "499") (name "unconnected-(U27-14{slash}A0{slash}PC0-Pad24)") (class "Default")
      (node (ref "U27") (pin "24") (pinfunction "14/A0/PC0_24") (pintype "unspecified"))
    )
    (net (code "500") (name "unconnected-(U27-15{slash}A1{slash}PC1-Pad23)") (class "Default")
      (node (ref "U27") (pin "23") (pinfunction "15/A1/PC1_23") (pintype "unspecified"))
    )
    (net (code "501") (name "unconnected-(U27-16{slash}A2{slash}PC2-Pad22)") (class "Default")
      (node (ref "U27") (pin "22") (pinfunction "16/A2/PC2_22") (pintype "unspecified"))
    )
    (net (code "502") (name "unconnected-(U27-17{slash}A3{slash}PC3-Pad21)") (class "Default")
      (node (ref "U27") (pin "21") (pinfunction "17/A3/PC3_21") (pintype "unspecified"))
    )
    (net (code "503") (name "unconnected-(U27-AREF-Pad16)") (class "Default")
      (node (ref "U27") (pin "16") (pinfunction "AREF_16") (pintype "unspecified"))
    )
    (net (code "504") (name "unconnected-(U27-GND-Pad15)") (class "Default")
      (node (ref "U27") (pin "15") (pinfunction "GND_15") (pintype "passive"))
    )
    (net (code "505") (name "unconnected-(U27-GND2-Pad27)") (class "Default")
      (node (ref "U27") (pin "27") (pinfunction "GND2_27") (pintype "passive"))
    )
    (net (code "506") (name "unconnected-(U27-INT0{slash}PD2{slash}2-Pad3)") (class "Default")
      (node (ref "U27") (pin "3") (pinfunction "INT0/PD2/2_3") (pintype "unspecified"))
    )
    (net (code "507") (name "unconnected-(U27-INT1{slash}PWR{slash}PD3{slash}3-Pad4)") (class "Default")
      (node (ref "U27") (pin "4") (pinfunction "INT1/PWR/PD3/3_4") (pintype "unspecified"))
    )
    (net (code "508") (name "unconnected-(U27-IOREF-Pad31)") (class "Default")
      (node (ref "U27") (pin "31") (pinfunction "IOREF_31") (pintype "unspecified"))
    )
    (net (code "509") (name "unconnected-(U27-MISO{slash}PB4{slash}12-Pad13)") (class "Default")
      (node (ref "U27") (pin "13") (pinfunction "MISO/PB4/12_13") (pintype "unspecified"))
    )
    (net (code "510") (name "unconnected-(U27-MOSI{slash}PWR{slash}PB3{slash}11-Pad12)") (class "Default")
      (node (ref "U27") (pin "12") (pinfunction "MOSI/PWR/PB3/11_12") (pintype "unspecified"))
    )
    (net (code "511") (name "unconnected-(U27-NC-Pad32)") (class "Default")
      (node (ref "U27") (pin "32") (pinfunction "NC_32") (pintype "unspecified"))
    )
    (net (code "512") (name "unconnected-(U27-PB0{slash}8-Pad9)") (class "Default")
      (node (ref "U27") (pin "9") (pinfunction "PB0/8_9") (pintype "unspecified"))
    )
    (net (code "513") (name "unconnected-(U27-PD4{slash}4-Pad5)") (class "Default")
      (node (ref "U27") (pin "5") (pinfunction "PD4/4_5") (pintype "unspecified"))
    )
    (net (code "514") (name "unconnected-(U27-PD7{slash}7-Pad8)") (class "Default")
      (node (ref "U27") (pin "8") (pinfunction "PD7/7_8") (pintype "unspecified"))
    )
    (net (code "515") (name "unconnected-(U27-PWR{slash}PB1{slash}9-Pad10)") (class "Default")
      (node (ref "U27") (pin "10") (pinfunction "PWR/PB1/9_10") (pintype "unspecified"))
    )
    (net (code "516") (name "unconnected-(U27-PWR{slash}PD5{slash}5-Pad6)") (class "Default")
      (node (ref "U27") (pin "6") (pinfunction "PWR/PD5/5_6") (pintype "unspecified"))
    )
    (net (code "517") (name "unconnected-(U27-PWR{slash}PD6{slash}6-Pad7)") (class "Default")
      (node (ref "U27") (pin "7") (pinfunction "PWR/PD6/6_7") (pintype "unspecified"))
    )
    (net (code "518") (name "unconnected-(U27-RESET-Pad30)") (class "Default")
      (node (ref "U27") (pin "30") (pinfunction "RESET_30") (pintype "unspecified"))
    )
    (net (code "519") (name "unconnected-(U27-RX{slash}PD0{slash}0-Pad1)") (class "Default")
      (node (ref "U27") (pin "1") (pinfunction "RX/PD0/0_1") (pintype "unspecified"))
    )
    (net (code "520") (name "unconnected-(U27-SCK{slash}PB5{slash}13-Pad14)") (class "Default")
      (node (ref "U27") (pin "14") (pinfunction "SCK/PB5/13_14") (pintype "unspecified"))
    )
    (net (code "521") (name "unconnected-(U27-SCL-Pad18)") (class "Default")
      (node (ref "U27") (pin "18") (pinfunction "SCL_18") (pintype "unspecified"))
    )
    (net (code "522") (name "unconnected-(U27-SDA-Pad17)") (class "Default")
      (node (ref "U27") (pin "17") (pinfunction "SDA_17") (pintype "unspecified"))
    )
    (net (code "523") (name "unconnected-(U27-SS{slash}PWR{slash}PB2{slash}10-Pad11)") (class "Default")
      (node (ref "U27") (pin "11") (pinfunction "SS/PWR/PB2/10_11") (pintype "unspecified"))
    )
    (net (code "524") (name "unconnected-(U27-TX{slash}PD1{slash}1-Pad2)") (class "Default")
      (node (ref "U27") (pin "2") (pinfunction "TX/PD1/1_2") (pintype "unspecified"))
    )
    (net (code "525") (name "unconnected-(U27-VIN-Pad25)") (class "Default")
      (node (ref "U27") (pin "25") (pinfunction "VIN_25") (pintype "passive"))
    )
    (net (code "526") (name "unconnected-(U28-3V3-Pad17)") (class "Default")
      (node (ref "U28") (pin "17") (pinfunction "3V3_17") (pintype "unspecified"))
    )
    (net (code "527") (name "unconnected-(U28-A0-Pad19)") (class "Default")
      (node (ref "U28") (pin "19") (pinfunction "A0_19") (pintype "unspecified"))
    )
    (net (code "528") (name "unconnected-(U28-A1-Pad20)") (class "Default")
      (node (ref "U28") (pin "20") (pinfunction "A1_20") (pintype "unspecified"))
    )
    (net (code "529") (name "unconnected-(U28-A2-Pad21)") (class "Default")
      (node (ref "U28") (pin "21") (pinfunction "A2_21") (pintype "unspecified"))
    )
    (net (code "530") (name "unconnected-(U28-A3-Pad22)") (class "Default")
      (node (ref "U28") (pin "22") (pinfunction "A3_22") (pintype "unspecified"))
    )
    (net (code "531") (name "unconnected-(U28-A6-Pad25)") (class "Default")
      (node (ref "U28") (pin "25") (pinfunction "A6_25") (pintype "unspecified"))
    )
    (net (code "532") (name "unconnected-(U28-A7-Pad26)") (class "Default")
      (node (ref "U28") (pin "26") (pinfunction "A7_26") (pintype "unspecified"))
    )
    (net (code "533") (name "unconnected-(U28-AREF-Pad18)") (class "Default")
      (node (ref "U28") (pin "18") (pinfunction "AREF_18") (pintype "unspecified"))
    )
    (net (code "534") (name "unconnected-(U28-D0{slash}RX-Pad2)") (class "Default")
      (node (ref "U28") (pin "2") (pinfunction "D0/RX_2") (pintype "unspecified"))
    )
    (net (code "535") (name "unconnected-(U28-D1{slash}TX-Pad1)") (class "Default")
      (node (ref "U28") (pin "1") (pinfunction "D1/TX_1") (pintype "unspecified"))
    )
    (net (code "536") (name "unconnected-(U28-D2-Pad5)") (class "Default")
      (node (ref "U28") (pin "5") (pinfunction "D2_5") (pintype "unspecified"))
    )
    (net (code "537") (name "unconnected-(U28-D3-Pad6)") (class "Default")
      (node (ref "U28") (pin "6") (pinfunction "D3_6") (pintype "unspecified"))
    )
    (net (code "538") (name "unconnected-(U28-D4-Pad7)") (class "Default")
      (node (ref "U28") (pin "7") (pinfunction "D4_7") (pintype "unspecified"))
    )
    (net (code "539") (name "unconnected-(U28-D5-Pad8)") (class "Default")
      (node (ref "U28") (pin "8") (pinfunction "D5_8") (pintype "unspecified"))
    )
    (net (code "540") (name "unconnected-(U28-D6-Pad9)") (class "Default")
      (node (ref "U28") (pin "9") (pinfunction "D6_9") (pintype "unspecified"))
    )
    (net (code "541") (name "unconnected-(U28-D7-Pad10)") (class "Default")
      (node (ref "U28") (pin "10") (pinfunction "D7_10") (pintype "unspecified"))
    )
    (net (code "542") (name "unconnected-(U28-D8-Pad11)") (class "Default")
      (node (ref "U28") (pin "11") (pinfunction "D8_11") (pintype "unspecified"))
    )
    (net (code "543") (name "unconnected-(U28-D9-Pad12)") (class "Default")
      (node (ref "U28") (pin "12") (pinfunction "D9_12") (pintype "unspecified"))
    )
    (net (code "544") (name "unconnected-(U28-D10-Pad13)") (class "Default")
      (node (ref "U28") (pin "13") (pinfunction "D10_13") (pintype "unspecified"))
    )
    (net (code "545") (name "unconnected-(U28-D11-Pad14)") (class "Default")
      (node (ref "U28") (pin "14") (pinfunction "D11_14") (pintype "unspecified"))
    )
    (net (code "546") (name "unconnected-(U28-D12-Pad15)") (class "Default")
      (node (ref "U28") (pin "15") (pinfunction "D12_15") (pintype "unspecified"))
    )
    (net (code "547") (name "unconnected-(U28-D13-Pad16)") (class "Default")
      (node (ref "U28") (pin "16") (pinfunction "D13_16") (pintype "unspecified"))
    )
    (net (code "548") (name "unconnected-(U28-GND-Pad29)") (class "Default")
      (node (ref "U28") (pin "29") (pinfunction "GND_29") (pintype "unspecified"))
    )
    (net (code "549") (name "unconnected-(U28-RESET-Pad3)") (class "Default")
      (node (ref "U28") (pin "3") (pinfunction "RESET_3") (pintype "unspecified"))
    )
    (net (code "550") (name "unconnected-(U28-RESET-Pad28)") (class "Default")
      (node (ref "U28") (pin "28") (pinfunction "RESET_28") (pintype "unspecified"))
    )
    (net (code "551") (name "unconnected-(U28-VIN-Pad30)") (class "Default")
      (node (ref "U28") (pin "30") (pinfunction "VIN_30") (pintype "unspecified"))
    )
    (net (code "552") (name "unconnected-(U47-3V-Pad29)") (class "Default")
      (node (ref "U47") (pin "29") (pinfunction "3V_29") (pintype "passive"))
    )
    (net (code "553") (name "unconnected-(U47-5V-Pad28)") (class "Default")
      (node (ref "U47") (pin "28") (pinfunction "5V_28") (pintype "passive"))
    )
    (net (code "554") (name "unconnected-(U47-A0-Pad24)") (class "Default")
      (node (ref "U47") (pin "24") (pinfunction "A0_24") (pintype "unspecified"))
    )
    (net (code "555") (name "unconnected-(U47-A1-Pad23)") (class "Default")
      (node (ref "U47") (pin "23") (pinfunction "A1_23") (pintype "unspecified"))
    )
    (net (code "556") (name "unconnected-(U47-A2-Pad22)") (class "Default")
      (node (ref "U47") (pin "22") (pinfunction "A2_22") (pintype "unspecified"))
    )
    (net (code "557") (name "unconnected-(U47-A3-Pad21)") (class "Default")
      (node (ref "U47") (pin "21") (pinfunction "A3_21") (pintype "unspecified"))
    )
    (net (code "558") (name "unconnected-(U47-A4-Pad20)") (class "Default")
      (node (ref "U47") (pin "20") (pinfunction "A4_20") (pintype "unspecified"))
    )
    (net (code "559") (name "unconnected-(U47-A5-Pad19)") (class "Default")
      (node (ref "U47") (pin "19") (pinfunction "A5_19") (pintype "unspecified"))
    )
    (net (code "560") (name "unconnected-(U47-AREF-Pad16)") (class "Default")
      (node (ref "U47") (pin "16") (pinfunction "AREF_16") (pintype "unspecified"))
    )
    (net (code "561") (name "unconnected-(U47-D0-Pad1)") (class "Default")
      (node (ref "U47") (pin "1") (pinfunction "D0_1") (pintype "unspecified"))
    )
    (net (code "562") (name "unconnected-(U47-D1-Pad2)") (class "Default")
      (node (ref "U47") (pin "2") (pinfunction "D1_2") (pintype "unspecified"))
    )
    (net (code "563") (name "unconnected-(U47-D2-Pad3)") (class "Default")
      (node (ref "U47") (pin "3") (pinfunction "D2_3") (pintype "unspecified"))
    )
    (net (code "564") (name "unconnected-(U47-D3-Pad4)") (class "Default")
      (node (ref "U47") (pin "4") (pinfunction "D3_4") (pintype "unspecified"))
    )
    (net (code "565") (name "unconnected-(U47-D4-Pad5)") (class "Default")
      (node (ref "U47") (pin "5") (pinfunction "D4_5") (pintype "unspecified"))
    )
    (net (code "566") (name "unconnected-(U47-D11-Pad12)") (class "Default")
      (node (ref "U47") (pin "12") (pinfunction "D11_12") (pintype "unspecified"))
    )
    (net (code "567") (name "unconnected-(U47-D12-Pad13)") (class "Default")
      (node (ref "U47") (pin "13") (pinfunction "D12_13") (pintype "unspecified"))
    )
    (net (code "568") (name "unconnected-(U47-D13-Pad14)") (class "Default")
      (node (ref "U47") (pin "14") (pinfunction "D13_14") (pintype "unspecified"))
    )
    (net (code "569") (name "unconnected-(U47-GND-Pad15)") (class "Default")
      (node (ref "U47") (pin "15") (pinfunction "GND_15") (pintype "passive"))
    )
    (net (code "570") (name "unconnected-(U47-GND1-Pad26)") (class "Default")
      (node (ref "U47") (pin "26") (pinfunction "GND1_26") (pintype "passive"))
    )
    (net (code "571") (name "unconnected-(U47-GND2-Pad27)") (class "Default")
      (node (ref "U47") (pin "27") (pinfunction "GND2_27") (pintype "passive"))
    )
    (net (code "572") (name "unconnected-(U47-IOREF-Pad31)") (class "Default")
      (node (ref "U47") (pin "31") (pinfunction "IOREF_31") (pintype "unspecified"))
    )
    (net (code "573") (name "unconnected-(U47-RESET-Pad30)") (class "Default")
      (node (ref "U47") (pin "30") (pinfunction "RESET_30") (pintype "unspecified"))
    )
    (net (code "574") (name "unconnected-(U47-SCL-Pad18)") (class "Default")
      (node (ref "U47") (pin "18") (pinfunction "SCL_18") (pintype "unspecified"))
    )
    (net (code "575") (name "unconnected-(U47-SDA-Pad17)") (class "Default")
      (node (ref "U47") (pin "17") (pinfunction "SDA_17") (pintype "unspecified"))
    )
    (net (code "576") (name "unconnected-(U47-USART1-Pad32)") (class "Default")
      (node (ref "U47") (pin "32") (pinfunction "USART1_32") (pintype "unspecified"))
    )
    (net (code "577") (name "unconnected-(U47-VIN-Pad25)") (class "Default")
      (node (ref "U47") (pin "25") (pinfunction "VIN_25") (pintype "passive"))
    )
    (net (code "578") (name "unconnected-(U51-3V-Pad29)") (class "Default")
      (node (ref "U51") (pin "29") (pinfunction "3V_29") (pintype "passive"))
    )
    (net (code "579") (name "unconnected-(U51-AREF-Pad16)") (class "Default")
      (node (ref "U51") (pin "16") (pinfunction "AREF_16") (pintype "unspecified"))
    )
    (net (code "580") (name "unconnected-(U51-D0-Pad1)") (class "Default")
      (node (ref "U51") (pin "1") (pinfunction "D0_1") (pintype "unspecified"))
    )
    (net (code "581") (name "unconnected-(U51-D1-Pad2)") (class "Default")
      (node (ref "U51") (pin "2") (pinfunction "D1_2") (pintype "unspecified"))
    )
    (net (code "582") (name "unconnected-(U51-D2-Pad3)") (class "Default")
      (node (ref "U51") (pin "3") (pinfunction "D2_3") (pintype "unspecified"))
    )
    (net (code "583") (name "unconnected-(U51-D3-Pad4)") (class "Default")
      (node (ref "U51") (pin "4") (pinfunction "D3_4") (pintype "unspecified"))
    )
    (net (code "584") (name "unconnected-(U51-D4-Pad5)") (class "Default")
      (node (ref "U51") (pin "5") (pinfunction "D4_5") (pintype "unspecified"))
    )
    (net (code "585") (name "unconnected-(U51-D5-Pad6)") (class "Default")
      (node (ref "U51") (pin "6") (pinfunction "D5_6") (pintype "unspecified"))
    )
    (net (code "586") (name "unconnected-(U51-D6-Pad7)") (class "Default")
      (node (ref "U51") (pin "7") (pinfunction "D6_7") (pintype "unspecified"))
    )
    (net (code "587") (name "unconnected-(U51-D7-Pad8)") (class "Default")
      (node (ref "U51") (pin "8") (pinfunction "D7_8") (pintype "unspecified"))
    )
    (net (code "588") (name "unconnected-(U51-D8-Pad9)") (class "Default")
      (node (ref "U51") (pin "9") (pinfunction "D8_9") (pintype "unspecified"))
    )
    (net (code "589") (name "unconnected-(U51-D9-Pad10)") (class "Default")
      (node (ref "U51") (pin "10") (pinfunction "D9_10") (pintype "unspecified"))
    )
    (net (code "590") (name "unconnected-(U51-D10-Pad11)") (class "Default")
      (node (ref "U51") (pin "11") (pinfunction "D10_11") (pintype "unspecified"))
    )
    (net (code "591") (name "unconnected-(U51-D11-Pad12)") (class "Default")
      (node (ref "U51") (pin "12") (pinfunction "D11_12") (pintype "unspecified"))
    )
    (net (code "592") (name "unconnected-(U51-D12-Pad13)") (class "Default")
      (node (ref "U51") (pin "13") (pinfunction "D12_13") (pintype "unspecified"))
    )
    (net (code "593") (name "unconnected-(U51-D13-Pad14)") (class "Default")
      (node (ref "U51") (pin "14") (pinfunction "D13_14") (pintype "unspecified"))
    )
    (net (code "594") (name "unconnected-(U51-GND-Pad15)") (class "Default")
      (node (ref "U51") (pin "15") (pinfunction "GND_15") (pintype "passive"))
    )
    (net (code "595") (name "unconnected-(U51-GND2-Pad27)") (class "Default")
      (node (ref "U51") (pin "27") (pinfunction "GND2_27") (pintype "passive"))
    )
    (net (code "596") (name "unconnected-(U51-IOREF-Pad31)") (class "Default")
      (node (ref "U51") (pin "31") (pinfunction "IOREF_31") (pintype "unspecified"))
    )
    (net (code "597") (name "unconnected-(U51-RESET-Pad30)") (class "Default")
      (node (ref "U51") (pin "30") (pinfunction "RESET_30") (pintype "unspecified"))
    )
    (net (code "598") (name "unconnected-(U51-SCL-Pad18)") (class "Default")
      (node (ref "U51") (pin "18") (pinfunction "SCL_18") (pintype "unspecified"))
    )
    (net (code "599") (name "unconnected-(U51-SDA-Pad17)") (class "Default")
      (node (ref "U51") (pin "17") (pinfunction "SDA_17") (pintype "unspecified"))
    )
    (net (code "600") (name "unconnected-(U51-USART1-Pad32)") (class "Default")
      (node (ref "U51") (pin "32") (pinfunction "USART1_32") (pintype "unspecified"))
    )
    (net (code "601") (name "unconnected-(U51-VIN-Pad25)") (class "Default")
      (node (ref "U51") (pin "25") (pinfunction "VIN_25") (pintype "passive"))
    )
    (net (code "602") (name "unconnected-(U52-3V-Pad29)") (class "Default")
      (node (ref "U52") (pin "29") (pinfunction "3V_29") (pintype "passive"))
    )
    (net (code "603") (name "unconnected-(U52-A0-Pad24)") (class "Default")
      (node (ref "U52") (pin "24") (pinfunction "A0_24") (pintype "unspecified"))
    )
    (net (code "604") (name "unconnected-(U52-A1-Pad23)") (class "Default")
      (node (ref "U52") (pin "23") (pinfunction "A1_23") (pintype "unspecified"))
    )
    (net (code "605") (name "unconnected-(U52-A2-Pad22)") (class "Default")
      (node (ref "U52") (pin "22") (pinfunction "A2_22") (pintype "unspecified"))
    )
    (net (code "606") (name "unconnected-(U52-A3-Pad21)") (class "Default")
      (node (ref "U52") (pin "21") (pinfunction "A3_21") (pintype "unspecified"))
    )
    (net (code "607") (name "unconnected-(U52-A4-Pad20)") (class "Default")
      (node (ref "U52") (pin "20") (pinfunction "A4_20") (pintype "unspecified"))
    )
    (net (code "608") (name "unconnected-(U52-A5-Pad19)") (class "Default")
      (node (ref "U52") (pin "19") (pinfunction "A5_19") (pintype "unspecified"))
    )
    (net (code "609") (name "unconnected-(U52-AREF-Pad16)") (class "Default")
      (node (ref "U52") (pin "16") (pinfunction "AREF_16") (pintype "unspecified"))
    )
    (net (code "610") (name "unconnected-(U52-D1-Pad2)") (class "Default")
      (node (ref "U52") (pin "2") (pinfunction "D1_2") (pintype "unspecified"))
    )
    (net (code "611") (name "unconnected-(U52-D2-Pad3)") (class "Default")
      (node (ref "U52") (pin "3") (pinfunction "D2_3") (pintype "unspecified"))
    )
    (net (code "612") (name "unconnected-(U52-D3-Pad4)") (class "Default")
      (node (ref "U52") (pin "4") (pinfunction "D3_4") (pintype "unspecified"))
    )
    (net (code "613") (name "unconnected-(U52-D4-Pad5)") (class "Default")
      (node (ref "U52") (pin "5") (pinfunction "D4_5") (pintype "unspecified"))
    )
    (net (code "614") (name "unconnected-(U52-D5-Pad6)") (class "Default")
      (node (ref "U52") (pin "6") (pinfunction "D5_6") (pintype "unspecified"))
    )
    (net (code "615") (name "unconnected-(U52-D6-Pad7)") (class "Default")
      (node (ref "U52") (pin "7") (pinfunction "D6_7") (pintype "unspecified"))
    )
    (net (code "616") (name "unconnected-(U52-D7-Pad8)") (class "Default")
      (node (ref "U52") (pin "8") (pinfunction "D7_8") (pintype "unspecified"))
    )
    (net (code "617") (name "unconnected-(U52-D8-Pad9)") (class "Default")
      (node (ref "U52") (pin "9") (pinfunction "D8_9") (pintype "unspecified"))
    )
    (net (code "618") (name "unconnected-(U52-D9-Pad10)") (class "Default")
      (node (ref "U52") (pin "10") (pinfunction "D9_10") (pintype "unspecified"))
    )
    (net (code "619") (name "unconnected-(U52-D10-Pad11)") (class "Default")
      (node (ref "U52") (pin "11") (pinfunction "D10_11") (pintype "unspecified"))
    )
    (net (code "620") (name "unconnected-(U52-D11-Pad12)") (class "Default")
      (node (ref "U52") (pin "12") (pinfunction "D11_12") (pintype "unspecified"))
    )
    (net (code "621") (name "unconnected-(U52-D12-Pad13)") (class "Default")
      (node (ref "U52") (pin "13") (pinfunction "D12_13") (pintype "unspecified"))
    )
    (net (code "622") (name "unconnected-(U52-D13-Pad14)") (class "Default")
      (node (ref "U52") (pin "14") (pinfunction "D13_14") (pintype "unspecified"))
    )
    (net (code "623") (name "unconnected-(U52-GND-Pad15)") (class "Default")
      (node (ref "U52") (pin "15") (pinfunction "GND_15") (pintype "passive"))
    )
    (net (code "624") (name "unconnected-(U52-GND2-Pad27)") (class "Default")
      (node (ref "U52") (pin "27") (pinfunction "GND2_27") (pintype "passive"))
    )
    (net (code "625") (name "unconnected-(U52-IOREF-Pad31)") (class "Default")
      (node (ref "U52") (pin "31") (pinfunction "IOREF_31") (pintype "unspecified"))
    )
    (net (code "626") (name "unconnected-(U52-RESET-Pad30)") (class "Default")
      (node (ref "U52") (pin "30") (pinfunction "RESET_30") (pintype "unspecified"))
    )
    (net (code "627") (name "unconnected-(U52-SCL-Pad18)") (class "Default")
      (node (ref "U52") (pin "18") (pinfunction "SCL_18") (pintype "unspecified"))
    )
    (net (code "628") (name "unconnected-(U52-SDA-Pad17)") (class "Default")
      (node (ref "U52") (pin "17") (pinfunction "SDA_17") (pintype "unspecified"))
    )
    (net (code "629") (name "unconnected-(U52-USART1-Pad32)") (class "Default")
      (node (ref "U52") (pin "32") (pinfunction "USART1_32") (pintype "unspecified"))
    )
    (net (code "630") (name "unconnected-(U52-VIN-Pad25)") (class "Default")
      (node (ref "U52") (pin "25") (pinfunction "VIN_25") (pintype "passive"))
    )
    (net (code "631") (name "unconnected-(U53-D1-Pad9)") (class "Default")
      (node (ref "U53") (pin "9") (pinfunction "D1_9") (pintype "unspecified"))
    )
    (net (code "632") (name "unconnected-(U53-D2-Pad10)") (class "Default")
      (node (ref "U53") (pin "10") (pinfunction "D2_10") (pintype "unspecified"))
    )
    (net (code "633") (name "unconnected-(U53-NC-Pad2)") (class "Default")
      (node (ref "U53") (pin "2") (pinfunction "NC_2") (pintype "unspecified"))
    )
    (net (code "634") (name "unconnected-(U53-NC-Pad5)") (class "Default")
      (node (ref "U53") (pin "5") (pinfunction "NC_5") (pintype "unspecified"))
    )
    (net (code "635") (name "unconnected-(U53-NC-Pad6)") (class "Default")
      (node (ref "U53") (pin "6") (pinfunction "NC_6") (pintype "unspecified"))
    )
    (net (code "636") (name "unconnected-(U54-3V-Pad29)") (class "Default")
      (node (ref "U54") (pin "29") (pinfunction "3V_29") (pintype "passive"))
    )
    (net (code "637") (name "unconnected-(U54-A0-Pad24)") (class "Default")
      (node (ref "U54") (pin "24") (pinfunction "A0_24") (pintype "unspecified"))
    )
    (net (code "638") (name "unconnected-(U54-A1-Pad23)") (class "Default")
      (node (ref "U54") (pin "23") (pinfunction "A1_23") (pintype "unspecified"))
    )
    (net (code "639") (name "unconnected-(U54-A2-Pad22)") (class "Default")
      (node (ref "U54") (pin "22") (pinfunction "A2_22") (pintype "unspecified"))
    )
    (net (code "640") (name "unconnected-(U54-A3-Pad21)") (class "Default")
      (node (ref "U54") (pin "21") (pinfunction "A3_21") (pintype "unspecified"))
    )
    (net (code "641") (name "unconnected-(U54-A4-Pad20)") (class "Default")
      (node (ref "U54") (pin "20") (pinfunction "A4_20") (pintype "unspecified"))
    )
    (net (code "642") (name "unconnected-(U54-A5-Pad19)") (class "Default")
      (node (ref "U54") (pin "19") (pinfunction "A5_19") (pintype "unspecified"))
    )
    (net (code "643") (name "unconnected-(U54-AREF-Pad16)") (class "Default")
      (node (ref "U54") (pin "16") (pinfunction "AREF_16") (pintype "unspecified"))
    )
    (net (code "644") (name "unconnected-(U54-D0-Pad1)") (class "Default")
      (node (ref "U54") (pin "1") (pinfunction "D0_1") (pintype "unspecified"))
    )
    (net (code "645") (name "unconnected-(U54-D1-Pad2)") (class "Default")
      (node (ref "U54") (pin "2") (pinfunction "D1_2") (pintype "unspecified"))
    )
    (net (code "646") (name "unconnected-(U54-D3-Pad4)") (class "Default")
      (node (ref "U54") (pin "4") (pinfunction "D3_4") (pintype "unspecified"))
    )
    (net (code "647") (name "unconnected-(U54-D4-Pad5)") (class "Default")
      (node (ref "U54") (pin "5") (pinfunction "D4_5") (pintype "unspecified"))
    )
    (net (code "648") (name "unconnected-(U54-D5-Pad6)") (class "Default")
      (node (ref "U54") (pin "6") (pinfunction "D5_6") (pintype "unspecified"))
    )
    (net (code "649") (name "unconnected-(U54-D6-Pad7)") (class "Default")
      (node (ref "U54") (pin "7") (pinfunction "D6_7") (pintype "unspecified"))
    )
    (net (code "650") (name "unconnected-(U54-D7-Pad8)") (class "Default")
      (node (ref "U54") (pin "8") (pinfunction "D7_8") (pintype "unspecified"))
    )
    (net (code "651") (name "unconnected-(U54-D8-Pad9)") (class "Default")
      (node (ref "U54") (pin "9") (pinfunction "D8_9") (pintype "unspecified"))
    )
    (net (code "652") (name "unconnected-(U54-D9-Pad10)") (class "Default")
      (node (ref "U54") (pin "10") (pinfunction "D9_10") (pintype "unspecified"))
    )
    (net (code "653") (name "unconnected-(U54-D10-Pad11)") (class "Default")
      (node (ref "U54") (pin "11") (pinfunction "D10_11") (pintype "unspecified"))
    )
    (net (code "654") (name "unconnected-(U54-D11-Pad12)") (class "Default")
      (node (ref "U54") (pin "12") (pinfunction "D11_12") (pintype "unspecified"))
    )
    (net (code "655") (name "unconnected-(U54-D12-Pad13)") (class "Default")
      (node (ref "U54") (pin "13") (pinfunction "D12_13") (pintype "unspecified"))
    )
    (net (code "656") (name "unconnected-(U54-D13-Pad14)") (class "Default")
      (node (ref "U54") (pin "14") (pinfunction "D13_14") (pintype "unspecified"))
    )
    (net (code "657") (name "unconnected-(U54-GND-Pad15)") (class "Default")
      (node (ref "U54") (pin "15") (pinfunction "GND_15") (pintype "passive"))
    )
    (net (code "658") (name "unconnected-(U54-GND2-Pad27)") (class "Default")
      (node (ref "U54") (pin "27") (pinfunction "GND2_27") (pintype "passive"))
    )
    (net (code "659") (name "unconnected-(U54-IOREF-Pad31)") (class "Default")
      (node (ref "U54") (pin "31") (pinfunction "IOREF_31") (pintype "unspecified"))
    )
    (net (code "660") (name "unconnected-(U54-RESET-Pad30)") (class "Default")
      (node (ref "U54") (pin "30") (pinfunction "RESET_30") (pintype "unspecified"))
    )
    (net (code "661") (name "unconnected-(U54-SCL-Pad18)") (class "Default")
      (node (ref "U54") (pin "18") (pinfunction "SCL_18") (pintype "unspecified"))
    )
    (net (code "662") (name "unconnected-(U54-SDA-Pad17)") (class "Default")
      (node (ref "U54") (pin "17") (pinfunction "SDA_17") (pintype "unspecified"))
    )
    (net (code "663") (name "unconnected-(U54-USART1-Pad32)") (class "Default")
      (node (ref "U54") (pin "32") (pinfunction "USART1_32") (pintype "unspecified"))
    )
    (net (code "664") (name "unconnected-(U55-NO-Pad5)") (class "Default")
      (node (ref "U55") (pin "5") (pinfunction "NO_5") (pintype "unspecified"))
    )
  )
)
